# Dashboard_2_1.net
KiCad netlist of a schematic drawn in EAGLE
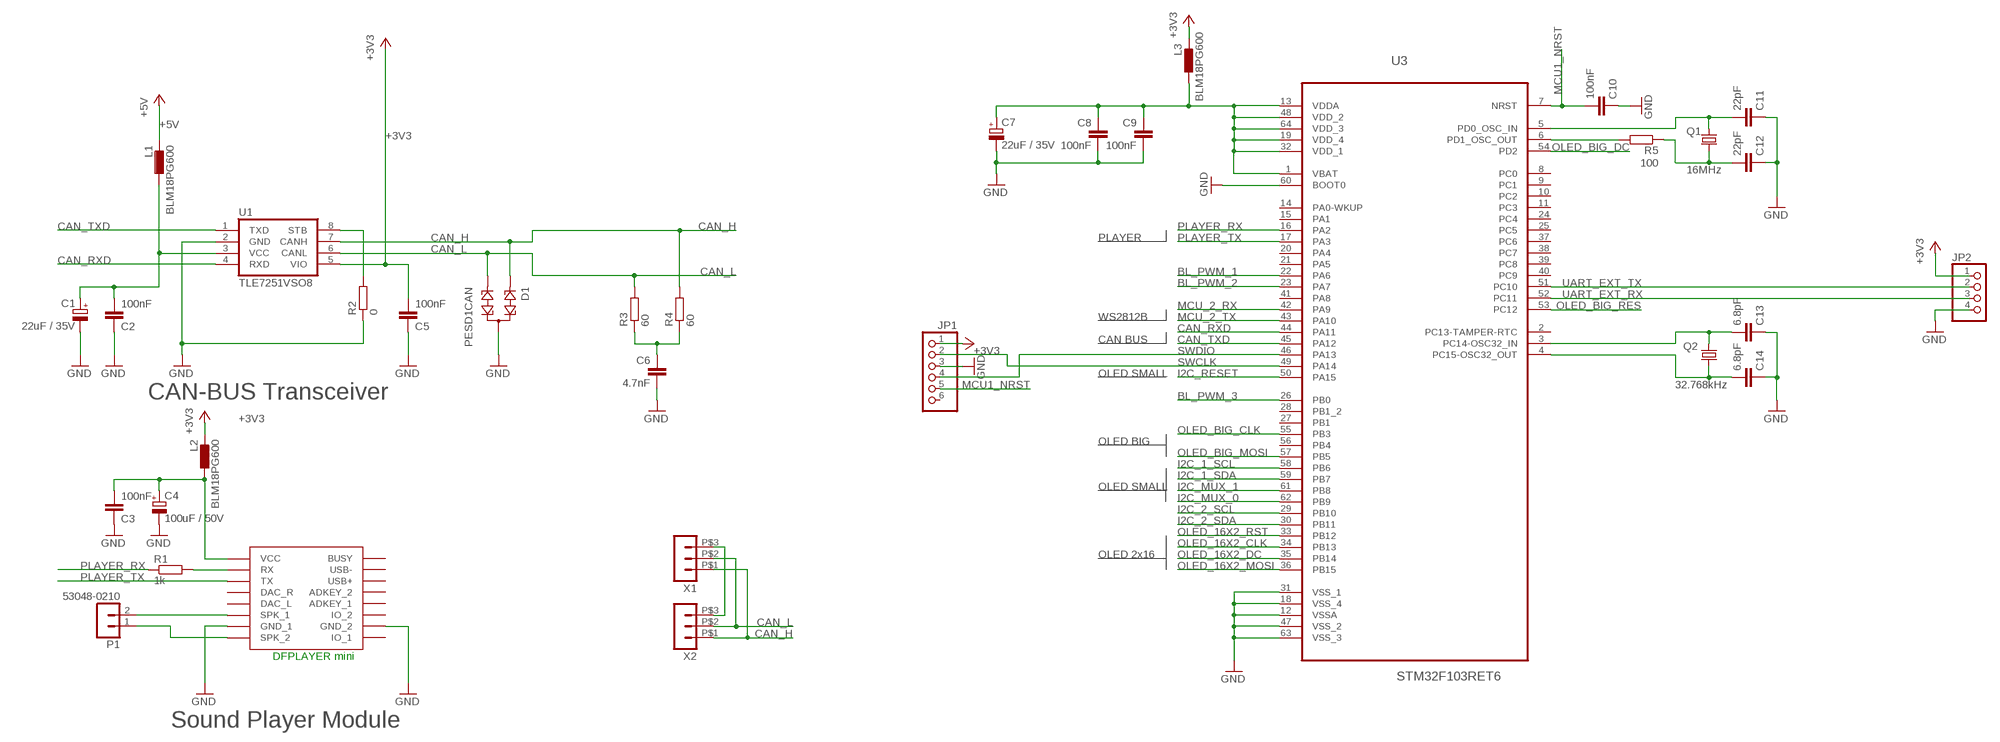
[diagram p0: schematic, sheet 1]
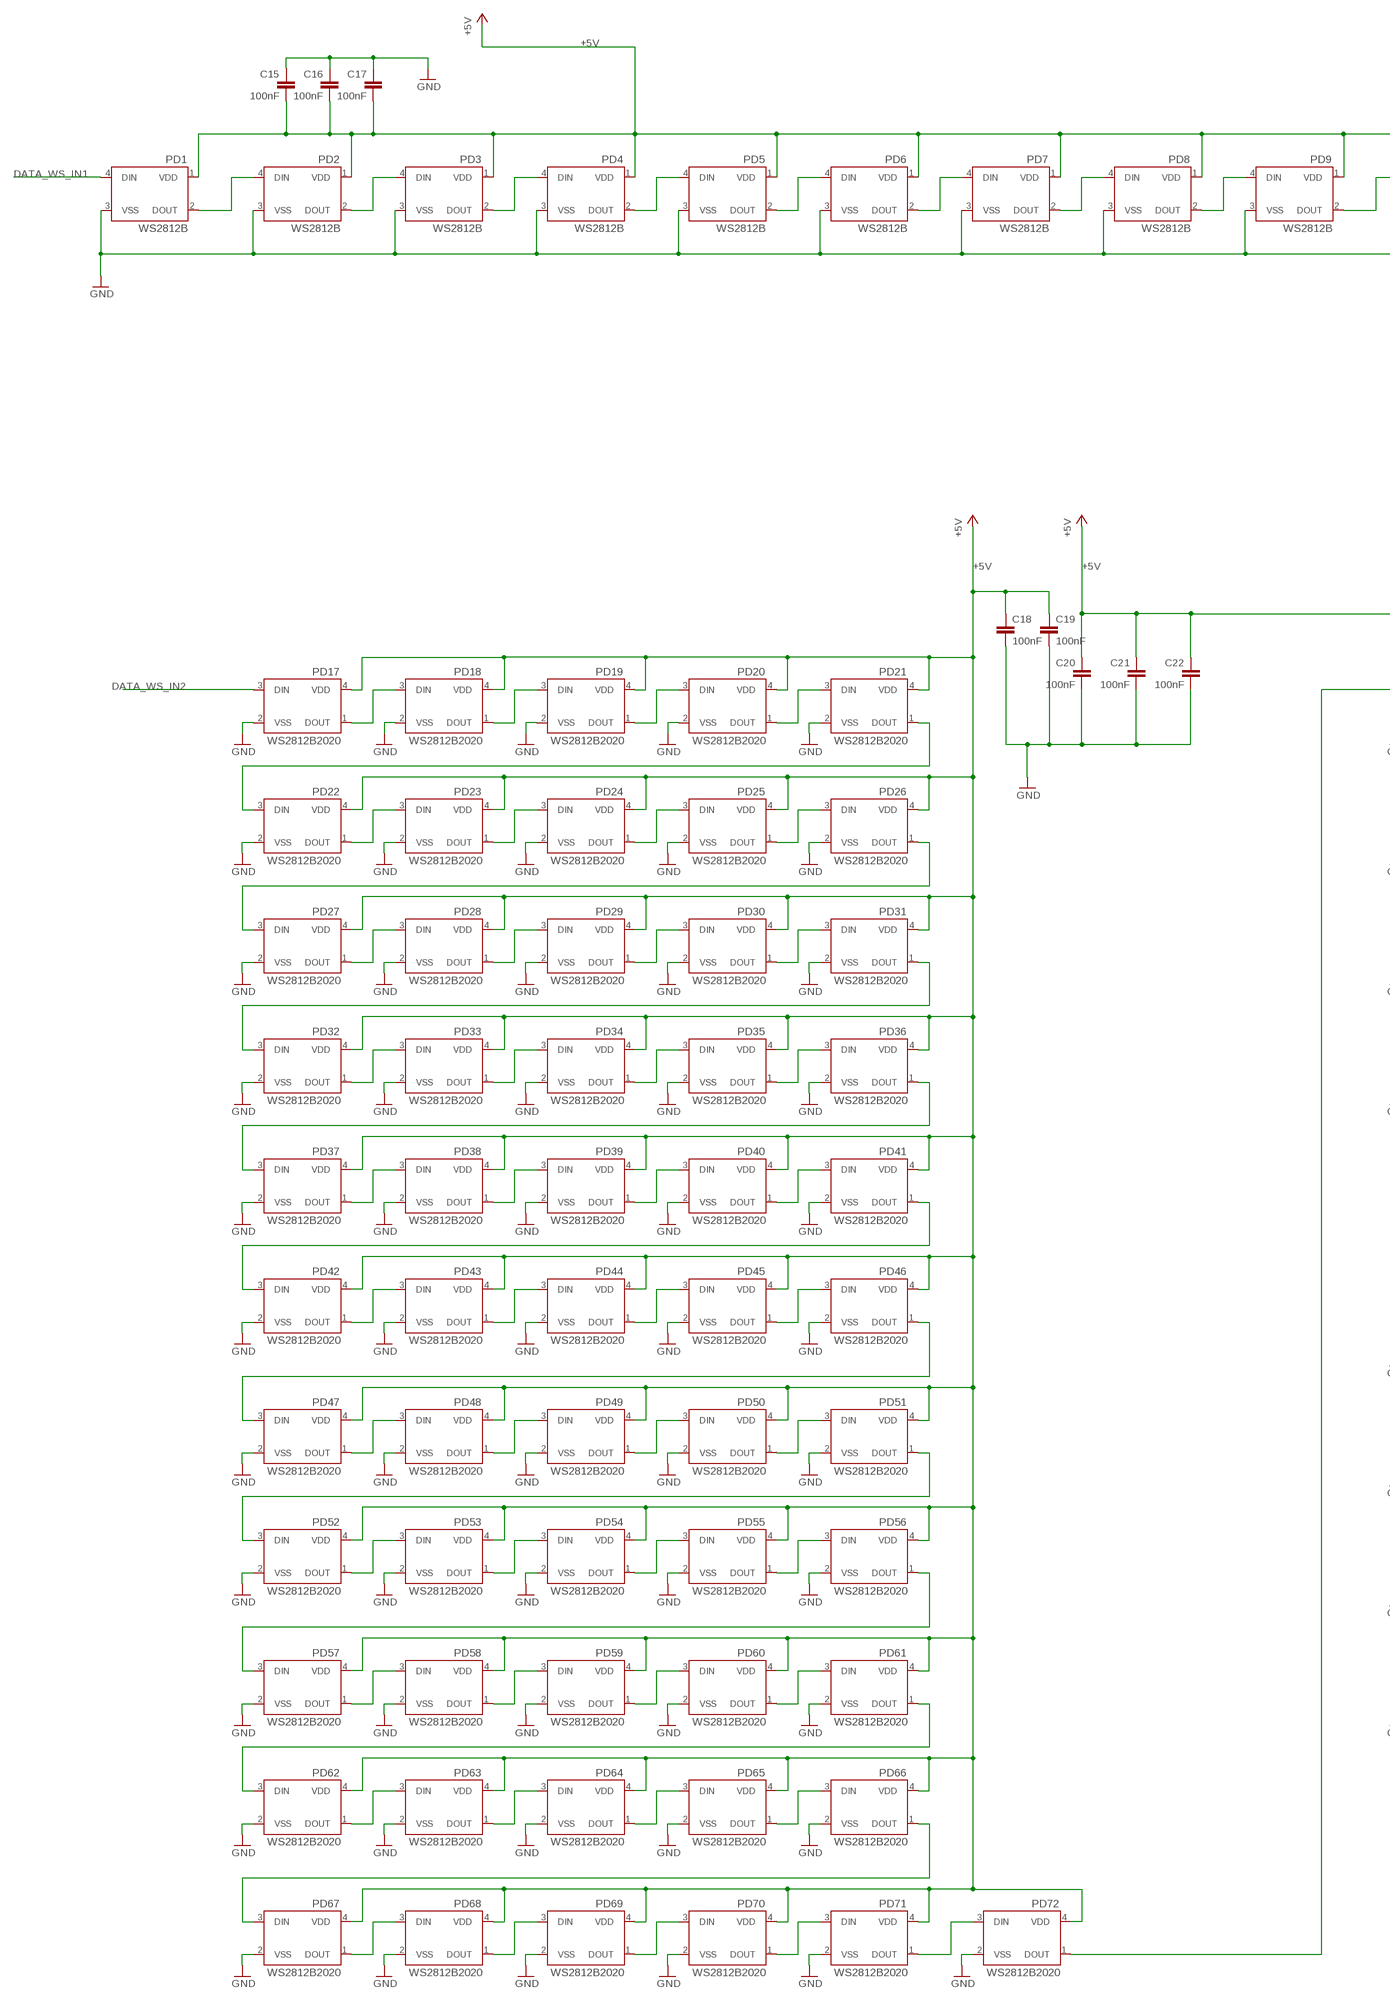
[diagram p1: schematic, sheet 2, part 1 of 2]
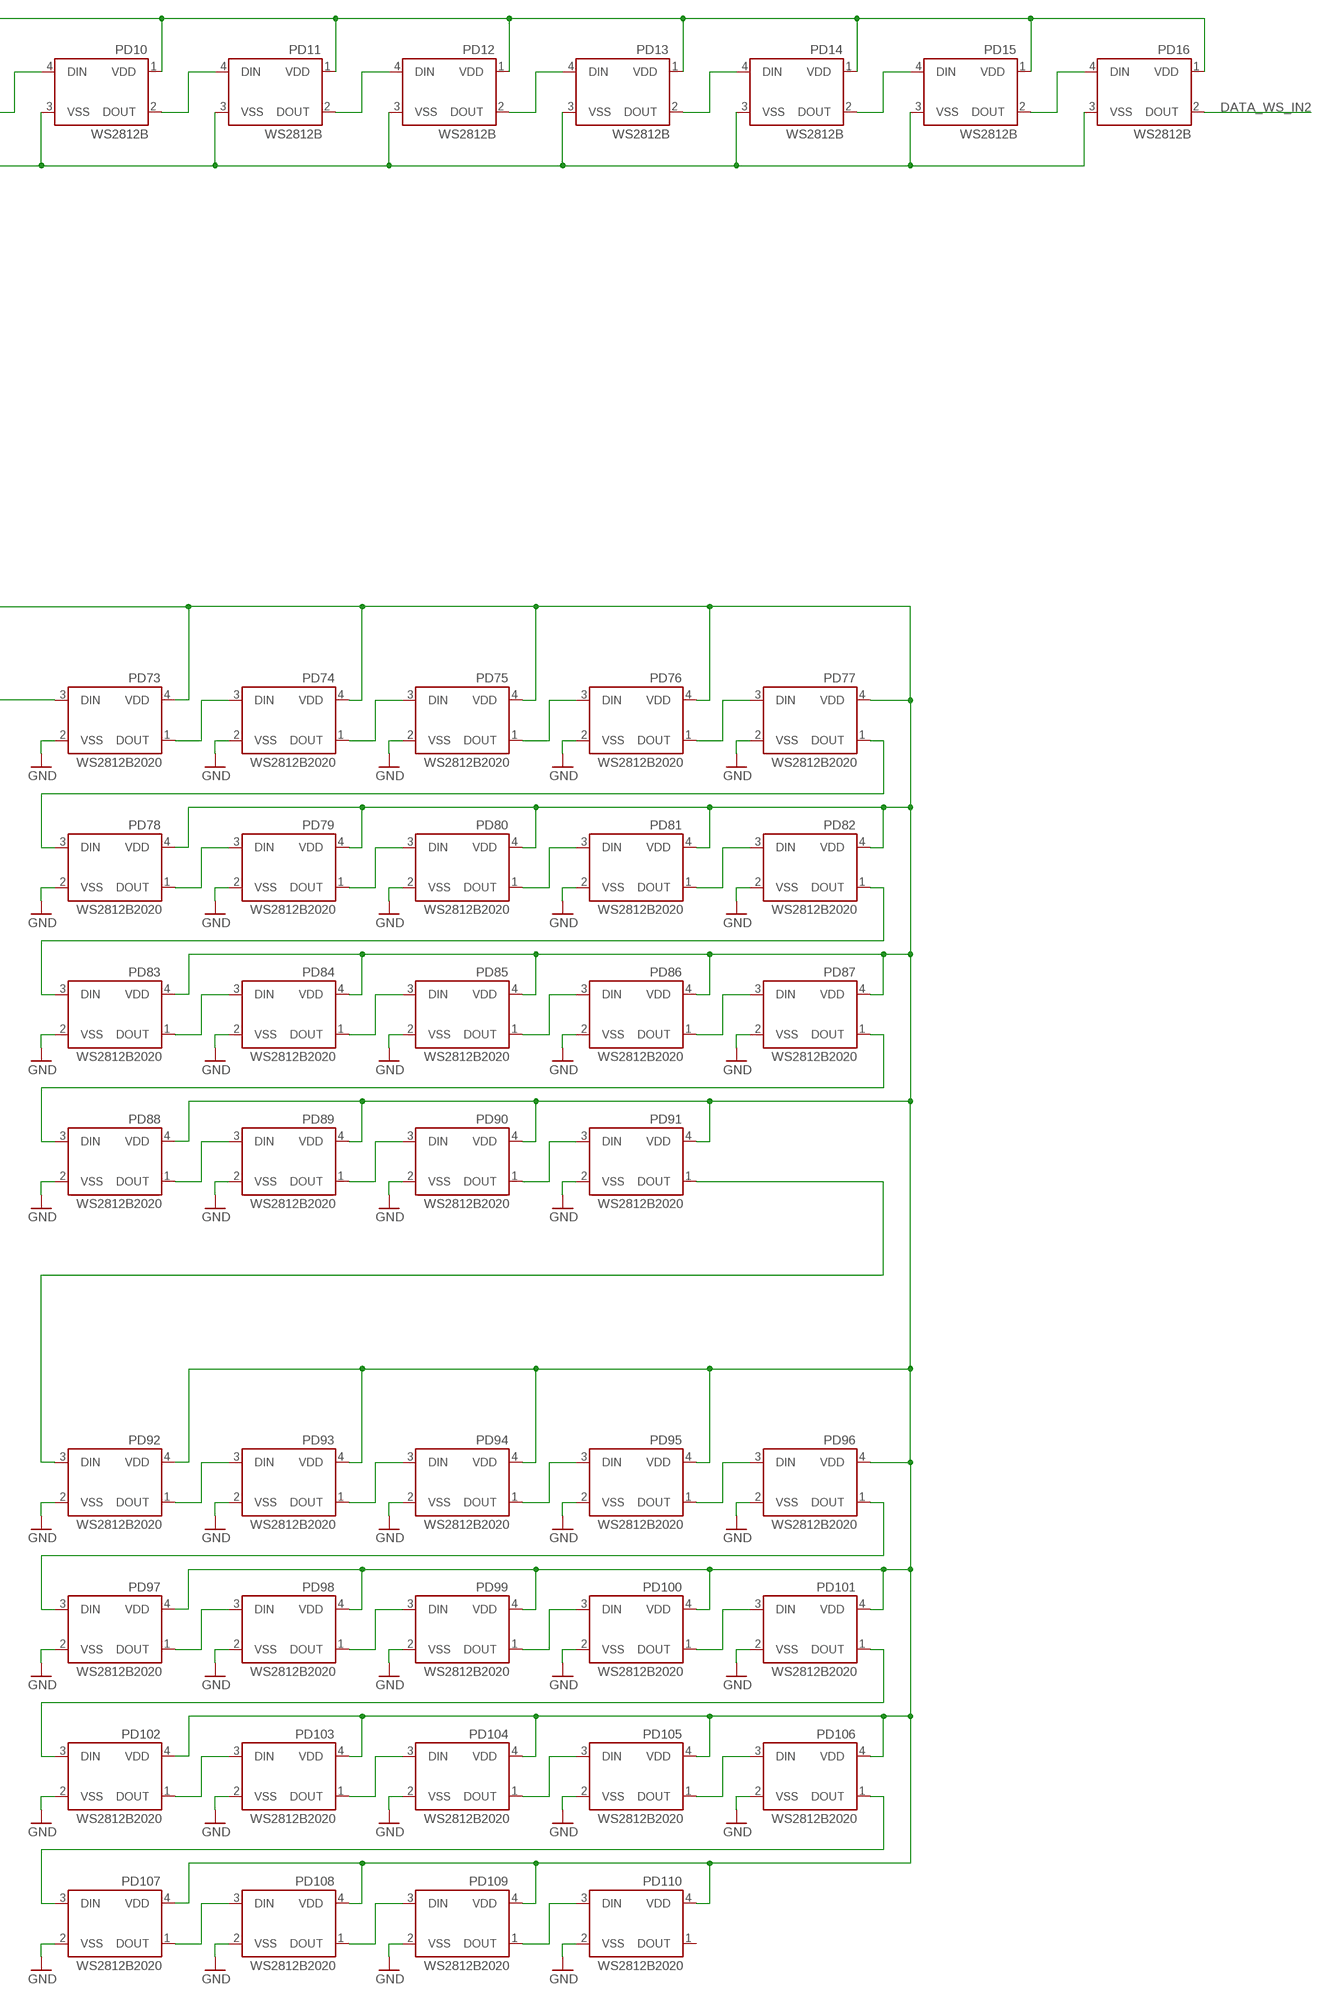
[diagram p2: schematic, sheet 2, part 2 of 2]
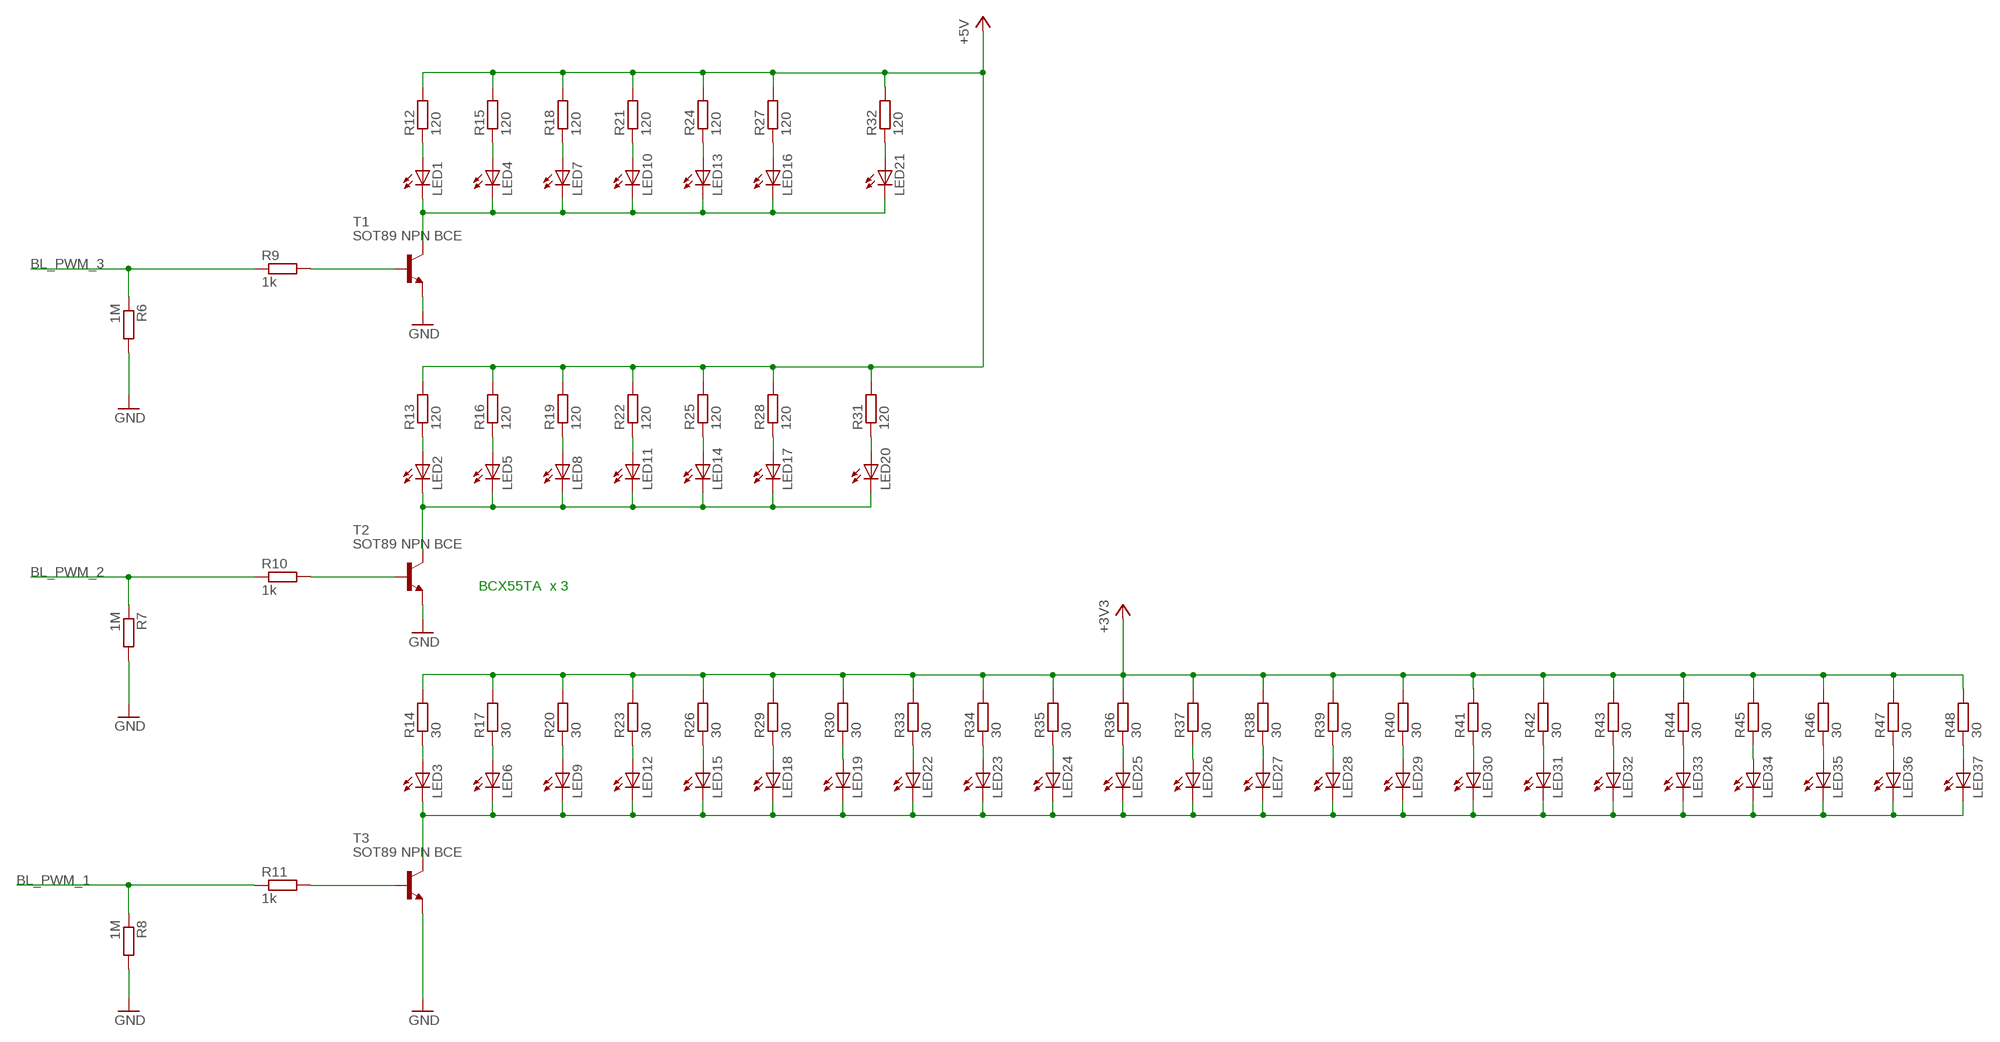
[diagram p3: schematic, sheet 3]
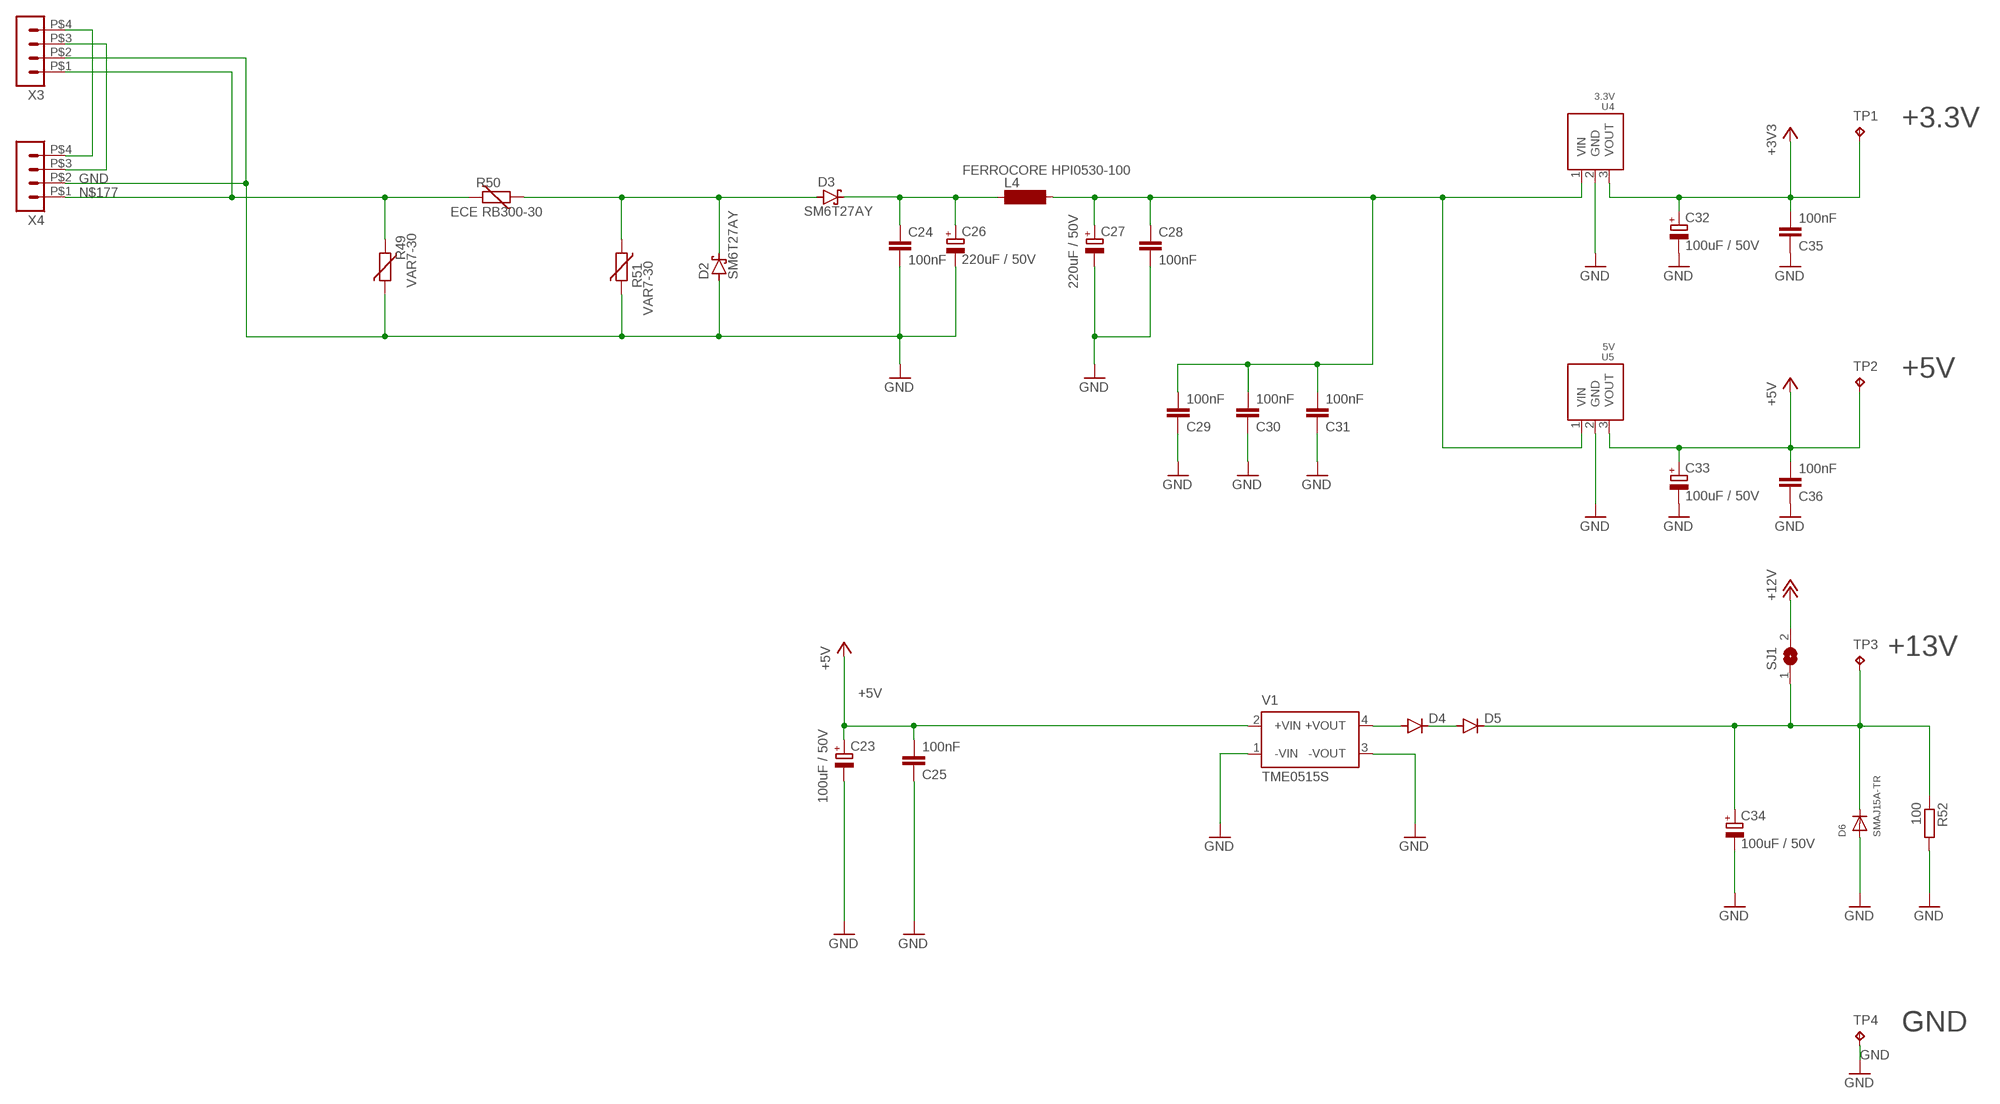
[diagram p4: schematic, sheet 4]
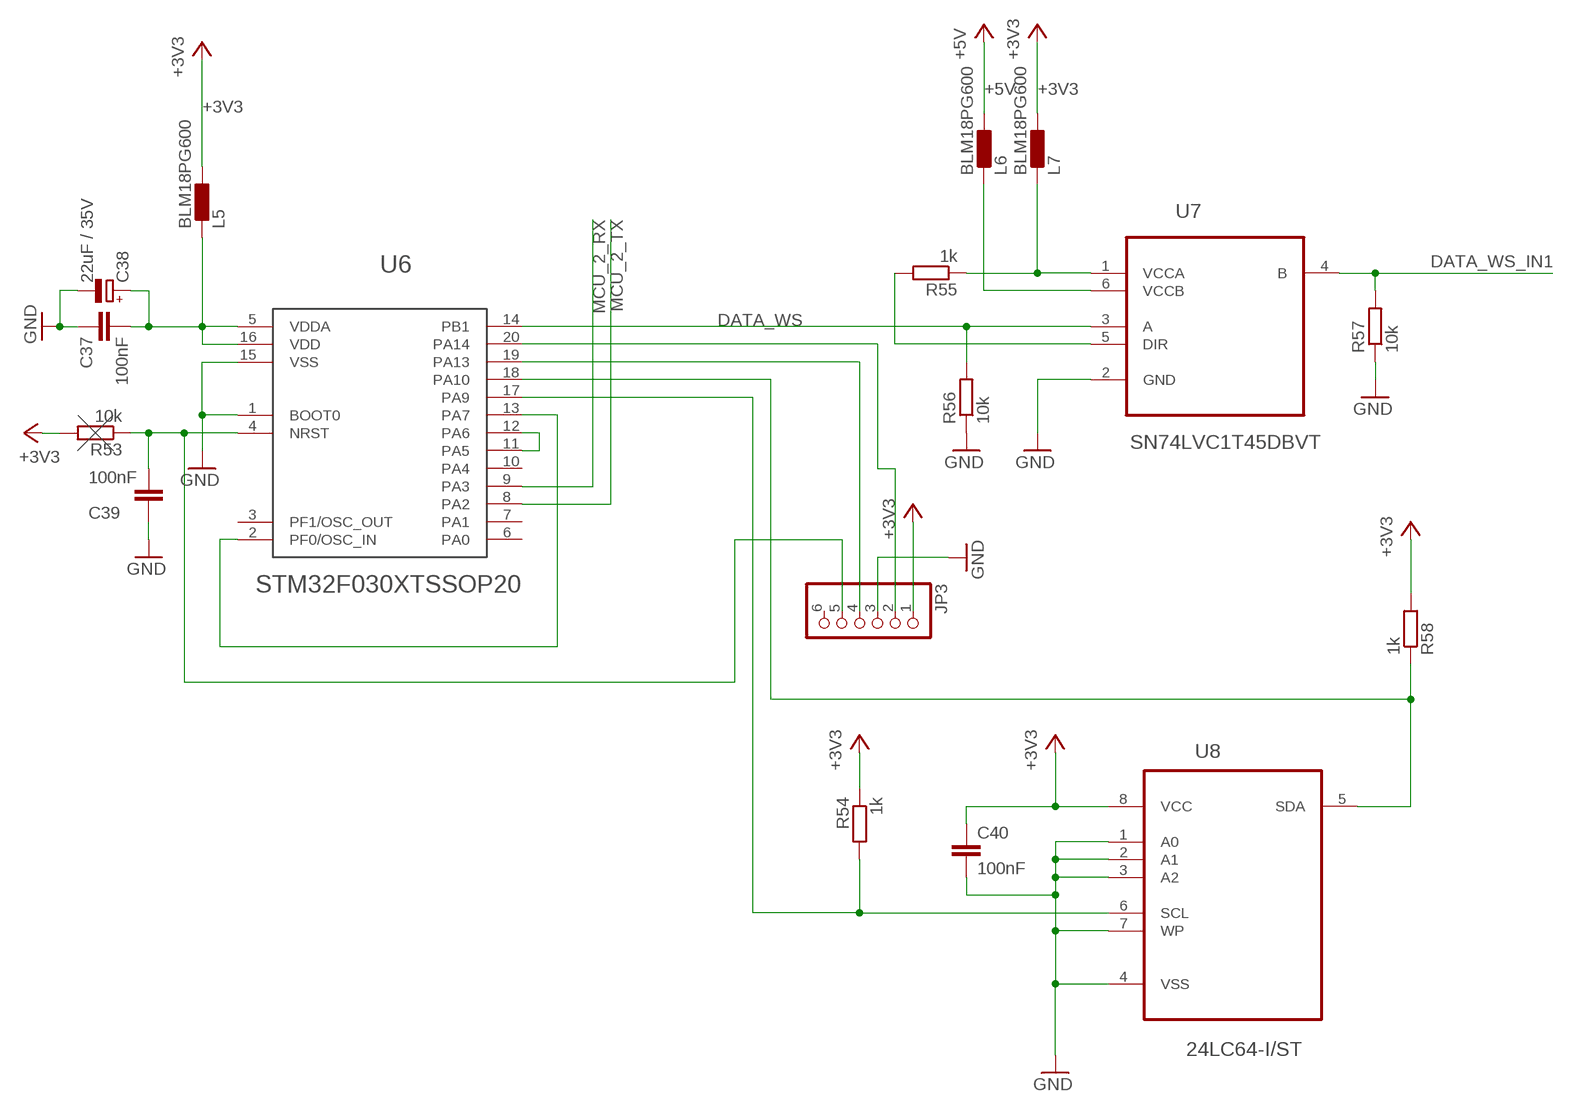
[diagram p5: schematic, sheet 5]
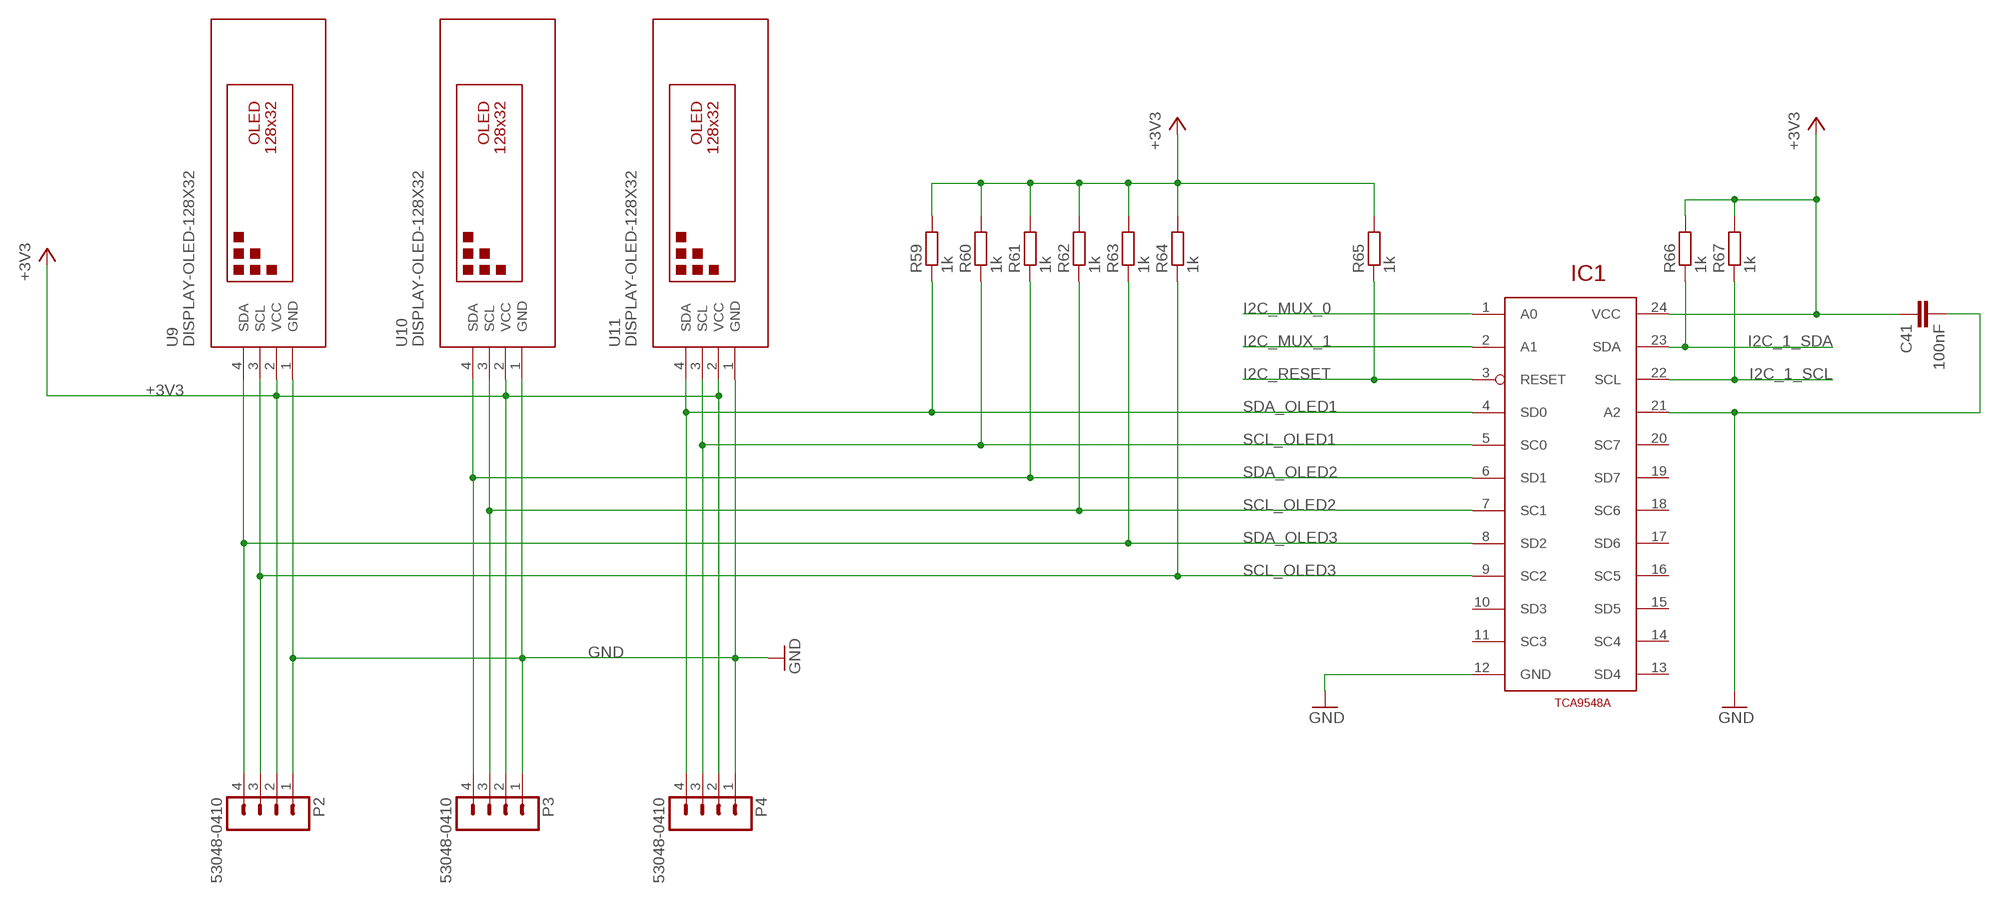
[diagram p6: schematic, sheet 6]
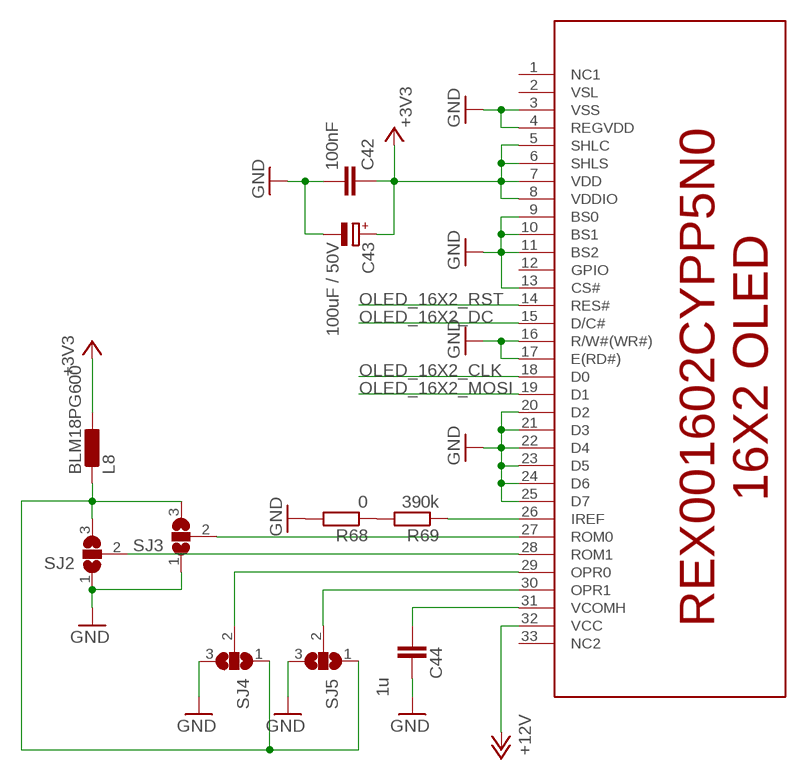
[diagram p7: schematic, sheet 7]
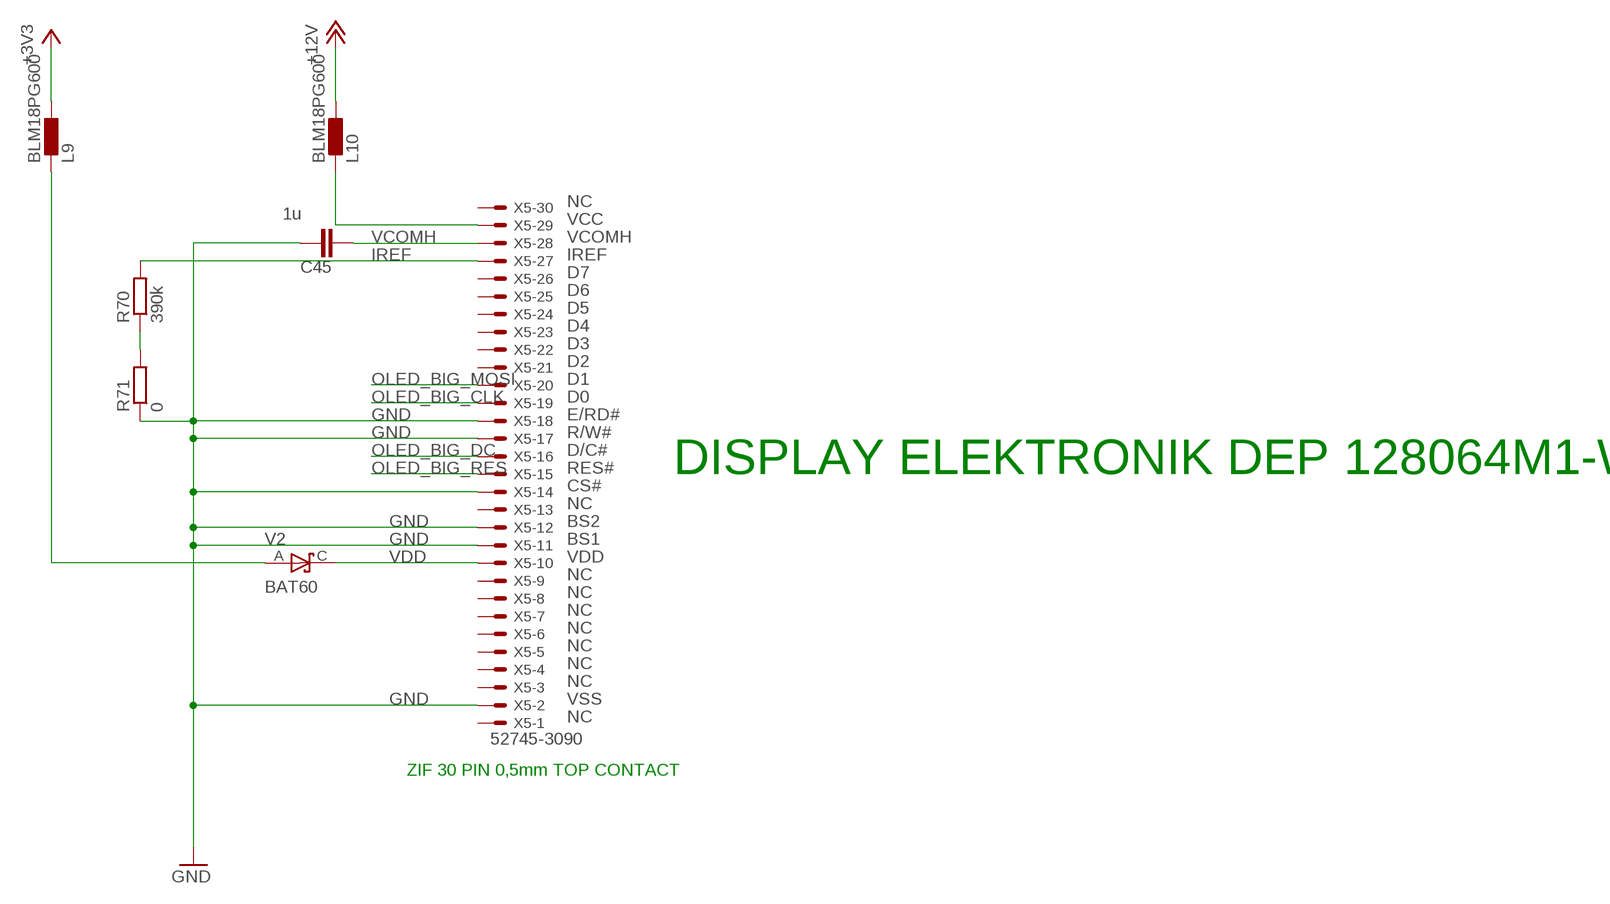
[diagram p8: schematic, sheet 8]

(export (version "E")
  (design (tool "Eeschema 10.0.6"))
  (components
    (comp (ref "C23")
      (value "100uF / 50V")
      (footprint "eagle-import:PANASONIC_F")
      (libsource (lib "eagle-import") (part "CPOL-EUF"))
    )
    (comp (ref "C24")
      (value "100nF")
      (footprint "eagle-import:C1206K")
      (libsource (lib "eagle-import") (part "rcl_334_C-EUC1206K"))
    )
    (comp (ref "C25")
      (value "100nF")
      (footprint "eagle-import:C0805K")
      (libsource (lib "eagle-import") (part "rcl_334_C-EUC0805K"))
    )
    (comp (ref "C26")
      (value "220uF / 50V")
      (footprint "eagle-import:PANASONIC_G")
      (libsource (lib "eagle-import") (part "CPOL-EUG"))
    )
    (comp (ref "C27")
      (value "220uF / 50V")
      (footprint "eagle-import:PANASONIC_G")
      (libsource (lib "eagle-import") (part "CPOL-EUG"))
    )
    (comp (ref "C28")
      (value "100nF")
      (footprint "eagle-import:C1206K")
      (libsource (lib "eagle-import") (part "rcl_334_C-EUC1206K"))
    )
    (comp (ref "C29")
      (value "100nF")
      (footprint "eagle-import:C0805K")
      (libsource (lib "eagle-import") (part "rcl_334_C-EUC0805K"))
    )
    (comp (ref "C30")
      (value "100nF")
      (footprint "eagle-import:C0805K")
      (libsource (lib "eagle-import") (part "rcl_334_C-EUC0805K"))
    )
    (comp (ref "C31")
      (value "100nF")
      (footprint "eagle-import:C0805K")
      (libsource (lib "eagle-import") (part "rcl_334_C-EUC0805K"))
    )
    (comp (ref "C32")
      (value "100uF / 50V")
      (footprint "eagle-import:PANASONIC_F")
      (libsource (lib "eagle-import") (part "CPOL-EUF"))
    )
    (comp (ref "C33")
      (value "100uF / 50V")
      (footprint "eagle-import:PANASONIC_F")
      (libsource (lib "eagle-import") (part "CPOL-EUF"))
    )
    (comp (ref "C34")
      (value "100uF / 50V")
      (footprint "eagle-import:PANASONIC_F")
      (libsource (lib "eagle-import") (part "CPOL-EUF"))
    )
    (comp (ref "C35")
      (value "100nF")
      (footprint "eagle-import:C0805K")
      (libsource (lib "eagle-import") (part "rcl_334_C-EUC0805K"))
    )
    (comp (ref "C36")
      (value "100nF")
      (footprint "eagle-import:C0805K")
      (libsource (lib "eagle-import") (part "rcl_334_C-EUC0805K"))
    )
    (comp (ref "D2")
      (value "SM6T27AY")
      (footprint "eagle-import:SMB")
      (libsource (lib "eagle-import") (part "SCHOTTKY-DIODESMD"))
    )
    (comp (ref "D3")
      (value "SM6T27AY")
      (footprint "eagle-import:SMB")
      (libsource (lib "eagle-import") (part "SCHOTTKY-DIODESMD"))
    )
    (comp (ref "D4")
      (value "DIODE-SOD123")
      (footprint "eagle-import:SOD123")
      (libsource (lib "eagle-import") (part "DIODE-SOD123"))
    )
    (comp (ref "D5")
      (value "DIODE-SOD123")
      (footprint "eagle-import:SOD123")
      (libsource (lib "eagle-import") (part "DIODE-SOD123"))
    )
    (comp (ref "D6")
      (value "SMAJ15A-TR")
      (footprint "eagle-import:SMADIODE")
      (libsource (lib "eagle-import") (part "DIODESMA"))
    )
    (comp (ref "L4")
      (value "FERROCORE HPI0530-100")
      (footprint "eagle-import:MS85")
      (libsource (lib "eagle-import") (part "MS85"))
    )
    (comp (ref "R49")
      (value "VAR7-30")
      (footprint "eagle-import:S07K11")
      (libsource (lib "eagle-import") (part "VARISTORS07K11"))
    )
    (comp (ref "R50")
      (value "ECE RB300-30")
      (footprint "eagle-import:S07K11")
      (libsource (lib "eagle-import") (part "VARISTORS07K11"))
    )
    (comp (ref "R51")
      (value "VAR7-30")
      (footprint "eagle-import:S07K11")
      (libsource (lib "eagle-import") (part "VARISTORS07K11"))
    )
    (comp (ref "R52")
      (value "100")
      (footprint "eagle-import:R0805")
      (libsource (lib "eagle-import") (part "R-EU_R0805"))
    )
    (comp (ref "SJ1") (value "SJ") (footprint "eagle-import:SJ") (libsource (lib "eagle-import") (part "SJ")))
    (comp (ref "TP1")
      (value "3V3")
      (footprint "eagle-import:TP18SQ")
      (libsource (lib "eagle-import") (part "TPTP18SQ"))
    )
    (comp (ref "TP2")
      (value "5V")
      (footprint "eagle-import:TP18SQ")
      (libsource (lib "eagle-import") (part "TPTP18SQ"))
    )
    (comp (ref "TP3")
      (value "12V")
      (footprint "eagle-import:TP18SQ")
      (libsource (lib "eagle-import") (part "TPTP18SQ"))
    )
    (comp (ref "TP4")
      (value "GND")
      (footprint "eagle-import:TP18SQ")
      (libsource (lib "eagle-import") (part "TPTP18SQ"))
    )
    (comp (ref "U4")
      (value "3.3V")
      (footprint "eagle-import:FDSM-173XXXX42")
      (libsource (lib "eagle-import") (part "FDSM_SIP-3_173010542"))
    )
    (comp (ref "U5")
      (value "5V")
      (footprint "eagle-import:FDSM-173XXXX42")
      (libsource (lib "eagle-import") (part "FDSM_SIP-3_173010542"))
    )
    (comp (ref "V1")
      (value "TME0515S")
      (footprint "eagle-import:TME")
      (fields (field (name "MPN") "TME 0515S"))
      (libsource (lib "eagle-import") (part "TME?0515S"))
    )
    (comp (ref "X3")
      (value "HEADER_POS4_43045-0412")
      (footprint "eagle-import:43045-0412")
      (libsource (lib "eagle-import") (part "HEADER_POS4_?43045-0412"))
    )
    (comp (ref "X4")
      (value "HEADER_POS4_43045-0412")
      (footprint "eagle-import:43045-0412")
      (libsource (lib "eagle-import") (part "HEADER_POS4_?43045-0412"))
    )
    (comp (ref "C37")
      (value "100nF")
      (footprint "eagle-import:C0805K")
      (libsource (lib "eagle-import") (part "rcl_334_C-EUC0805K"))
    )
    (comp (ref "C38")
      (value "22uF / 35V")
      (footprint "eagle-import:SMC_D")
      (libsource (lib "eagle-import") (part "CPOL-EUSMCD"))
    )
    (comp (ref "C39")
      (value "100nF")
      (footprint "eagle-import:C0805K")
      (libsource (lib "eagle-import") (part "rcl_334_C-EUC0805K"))
    )
    (comp (ref "C40")
      (value "100nF")
      (footprint "eagle-import:C0805K")
      (libsource (lib "eagle-import") (part "rcl_334_C-EUC0805K"))
    )
    (comp (ref "JP3")
      (value "PINHD-1X6")
      (footprint "eagle-import:1X06")
      (libsource (lib "eagle-import") (part "PINHD-1X6"))
    )
    (comp (ref "L5")
      (value "BLM18PG600")
      (footprint "eagle-import:L1608")
      (libsource (lib "eagle-import") (part "L_EU_L0603"))
    )
    (comp (ref "L6")
      (value "BLM18PG600")
      (footprint "eagle-import:L1608")
      (libsource (lib "eagle-import") (part "L_EU_L0603"))
    )
    (comp (ref "L7")
      (value "BLM18PG600")
      (footprint "eagle-import:L1608")
      (libsource (lib "eagle-import") (part "L_EU_L0603"))
    )
    (comp (ref "R53")
      (value "10k")
      (footprint "eagle-import:R0805")
      (libsource (lib "eagle-import") (part "R-EU_R0805"))
    )
    (comp (ref "R54")
      (value "1k")
      (footprint "eagle-import:R0805")
      (libsource (lib "eagle-import") (part "R-EU_R0805"))
    )
    (comp (ref "R55")
      (value "1k")
      (footprint "eagle-import:R0805")
      (libsource (lib "eagle-import") (part "R-EU_R0805"))
    )
    (comp (ref "R56")
      (value "10k")
      (footprint "eagle-import:R0805")
      (libsource (lib "eagle-import") (part "R-EU_R0805"))
    )
    (comp (ref "R57")
      (value "10k")
      (footprint "eagle-import:R0805")
      (libsource (lib "eagle-import") (part "R-EU_R0805"))
    )
    (comp (ref "R58")
      (value "1k")
      (footprint "eagle-import:R0805")
      (libsource (lib "eagle-import") (part "R-EU_R0805"))
    )
    (comp (ref "U6")
      (value "STM32F030XTSSOP20")
      (footprint "eagle-import:TSSOP-20")
      (libsource (lib "eagle-import") (part "STM32F030XTSSOP20"))
    )
    (comp (ref "U7")
      (value "SN74LVC1T45DBVT")
      (footprint "eagle-import:SOT95P280X145-6N")
      (fields (field (name "MF") "Texas Instruments"))
      (libsource (lib "eagle-import") (part "SN74LVC1T45DBVT"))
    )
    (comp (ref "U8")
      (value "24LC64-I/ST")
      (footprint "eagle-import:SOP65P638X110-8N")
      (fields (field (name "MF") "Microchip"))
      (libsource (lib "eagle-import") (part "24LC64-I/ST"))
    )
    (comp (ref "C1")
      (value "22uF / 35V")
      (footprint "eagle-import:SMC_D")
      (libsource (lib "eagle-import") (part "CPOL-EUSMCD"))
    )
    (comp (ref "C2")
      (value "100nF")
      (footprint "eagle-import:C0805K")
      (libsource (lib "eagle-import") (part "rcl_334_C-EUC0805K"))
    )
    (comp (ref "C3")
      (value "100nF")
      (footprint "eagle-import:C0805K")
      (libsource (lib "eagle-import") (part "rcl_334_C-EUC0805K"))
    )
    (comp (ref "C4")
      (value "100uF / 50V")
      (footprint "eagle-import:PANASONIC_F")
      (libsource (lib "eagle-import") (part "CPOL-EUF"))
    )
    (comp (ref "C5")
      (value "100nF")
      (footprint "eagle-import:C0805K")
      (libsource (lib "eagle-import") (part "rcl_334_C-EUC0805K"))
    )
    (comp (ref "C6")
      (value "4.7nF")
      (footprint "eagle-import:C0805K")
      (libsource (lib "eagle-import") (part "rcl_334_C-EUC0805K"))
    )
    (comp (ref "C7")
      (value "22uF / 35V")
      (footprint "eagle-import:SMC_D")
      (libsource (lib "eagle-import") (part "CPOL-EUSMCD"))
    )
    (comp (ref "C8")
      (value "100nF")
      (footprint "eagle-import:C0805K")
      (libsource (lib "eagle-import") (part "rcl_334_C-EUC0805K"))
    )
    (comp (ref "C9")
      (value "100nF")
      (footprint "eagle-import:C0805K")
      (libsource (lib "eagle-import") (part "rcl_334_C-EUC0805K"))
    )
    (comp (ref "C10")
      (value "100nF")
      (footprint "eagle-import:C0805K")
      (libsource (lib "eagle-import") (part "rcl_334_C-EUC0805K"))
    )
    (comp (ref "C11")
      (value "22pF")
      (footprint "eagle-import:C0805K")
      (libsource (lib "eagle-import") (part "rcl_334_C-EUC0805K"))
    )
    (comp (ref "C12")
      (value "22pF")
      (footprint "eagle-import:C0805K")
      (libsource (lib "eagle-import") (part "rcl_334_C-EUC0805K"))
    )
    (comp (ref "C13")
      (value "6.8pF")
      (footprint "eagle-import:C0805K")
      (libsource (lib "eagle-import") (part "rcl_334_C-EUC0805K"))
    )
    (comp (ref "C14")
      (value "6.8pF")
      (footprint "eagle-import:C0805K")
      (libsource (lib "eagle-import") (part "rcl_334_C-EUC0805K"))
    )
    (comp (ref "D1")
      (value "PESD1CAN")
      (footprint "eagle-import:SOT23")
      (libsource (lib "eagle-import") (part "PESD1CAN"))
    )
    (comp (ref "JP1")
      (value "PINHD-1X6")
      (footprint "eagle-import:1X06")
      (libsource (lib "eagle-import") (part "PINHD-1X6"))
    )
    (comp (ref "JP2")
      (value "PINHD-1X4")
      (footprint "eagle-import:1X04")
      (libsource (lib "eagle-import") (part "PINHD-1X4"))
    )
    (comp (ref "L1")
      (value "BLM18PG600")
      (footprint "eagle-import:L1608")
      (libsource (lib "eagle-import") (part "L_EU_L0603"))
    )
    (comp (ref "L2")
      (value "BLM18PG600")
      (footprint "eagle-import:L1608")
      (libsource (lib "eagle-import") (part "L_EU_L0603"))
    )
    (comp (ref "L3")
      (value "BLM18PG600")
      (footprint "eagle-import:L1608")
      (libsource (lib "eagle-import") (part "L_EU_L0603"))
    )
    (comp (ref "P1")
      (value "53048-0210")
      (footprint "eagle-import:53048-0210")
      (libsource (lib "eagle-import") (part "53048-0210"))
    )
    (comp (ref "Q1")
      (value "16MHz")
      (footprint "eagle-import:SM49")
      (libsource (lib "eagle-import") (part "CRYSTALSM49"))
    )
    (comp (ref "Q2")
      (value "32.768kHz")
      (footprint "eagle-import:SMD4_270")
      (libsource (lib "eagle-import") (part "MC-306"))
    )
    (comp (ref "R1")
      (value "1k")
      (footprint "eagle-import:R0805")
      (libsource (lib "eagle-import") (part "R-EU_R0805"))
    )
    (comp (ref "R2")
      (value "0")
      (footprint "eagle-import:R0805")
      (libsource (lib "eagle-import") (part "R-EU_R0805"))
    )
    (comp (ref "R3")
      (value "60")
      (footprint "eagle-import:R0805")
      (libsource (lib "eagle-import") (part "R-EU_R0805"))
    )
    (comp (ref "R4")
      (value "60")
      (footprint "eagle-import:R0805")
      (libsource (lib "eagle-import") (part "R-EU_R0805"))
    )
    (comp (ref "R5")
      (value "100")
      (footprint "eagle-import:R0805")
      (libsource (lib "eagle-import") (part "R-EU_R0805"))
    )
    (comp (ref "U1")
      (value "TLE7251VSO8")
      (footprint "eagle-import:SO8")
      (libsource (lib "eagle-import") (part "TLE7251VSO8"))
    )
    (comp (ref "U2")
      (value "DFPLAYER")
      (footprint "eagle-import:DFPLAYER")
      (libsource (lib "eagle-import") (part "DFPLAYER"))
    )
    (comp (ref "U3")
      (value "STM32F103RET6")
      (footprint "eagle-import:QFP50P1200X1200X160-64N")
      (libsource (lib "eagle-import") (part "STM32F103RET6"))
    )
    (comp (ref "X1")
      (value "HEADER_POS3_43650-0315")
      (footprint "eagle-import:43650-0315")
      (libsource (lib "eagle-import") (part "HEADER_POS3_?43650-0315"))
    )
    (comp (ref "X2")
      (value "HEADER_POS3_43650-0315")
      (footprint "eagle-import:43650-0315")
      (libsource (lib "eagle-import") (part "HEADER_POS3_?43650-0315"))
    )
    (comp (ref "C41")
      (value "100nF")
      (footprint "eagle-import:C0805K")
      (libsource (lib "eagle-import") (part "rcl_334_C-EUC0805K"))
    )
    (comp (ref "IC1")
      (value "TCA9548A")
      (footprint "eagle-import:TSSOP24")
      (libsource (lib "eagle-import") (part "TCA9548A"))
    )
    (comp (ref "P2")
      (value "53048-0410")
      (footprint "eagle-import:53048-0410")
      (libsource (lib "eagle-import") (part "53048-0410"))
    )
    (comp (ref "P3")
      (value "53048-0410")
      (footprint "eagle-import:53048-0410")
      (libsource (lib "eagle-import") (part "53048-0410"))
    )
    (comp (ref "P4")
      (value "53048-0410")
      (footprint "eagle-import:53048-0410")
      (libsource (lib "eagle-import") (part "53048-0410"))
    )
    (comp (ref "R59")
      (value "1k")
      (footprint "eagle-import:R0805")
      (libsource (lib "eagle-import") (part "R-EU_R0805"))
    )
    (comp (ref "R60")
      (value "1k")
      (footprint "eagle-import:R0805")
      (libsource (lib "eagle-import") (part "R-EU_R0805"))
    )
    (comp (ref "R61")
      (value "1k")
      (footprint "eagle-import:R0805")
      (libsource (lib "eagle-import") (part "R-EU_R0805"))
    )
    (comp (ref "R62")
      (value "1k")
      (footprint "eagle-import:R0805")
      (libsource (lib "eagle-import") (part "R-EU_R0805"))
    )
    (comp (ref "R63")
      (value "1k")
      (footprint "eagle-import:R0805")
      (libsource (lib "eagle-import") (part "R-EU_R0805"))
    )
    (comp (ref "R64")
      (value "1k")
      (footprint "eagle-import:R0805")
      (libsource (lib "eagle-import") (part "R-EU_R0805"))
    )
    (comp (ref "R65")
      (value "1k")
      (footprint "eagle-import:R0805")
      (libsource (lib "eagle-import") (part "R-EU_R0805"))
    )
    (comp (ref "R66")
      (value "1k")
      (footprint "eagle-import:R0805")
      (libsource (lib "eagle-import") (part "R-EU_R0805"))
    )
    (comp (ref "R67")
      (value "1k")
      (footprint "eagle-import:R0805")
      (libsource (lib "eagle-import") (part "R-EU_R0805"))
    )
    (comp (ref "U9")
      (value "DISPLAY-OLED-128X32")
      (footprint "eagle-import:DISPLAY-OLED-128X32")
      (libsource (lib "eagle-import") (part "DISPLAY-OLED-128X32"))
    )
    (comp (ref "U10")
      (value "DISPLAY-OLED-128X32")
      (footprint "eagle-import:DISPLAY-OLED-128X32")
      (libsource (lib "eagle-import") (part "DISPLAY-OLED-128X32"))
    )
    (comp (ref "U11")
      (value "DISPLAY-OLED-128X32")
      (footprint "eagle-import:DISPLAY-OLED-128X32")
      (libsource (lib "eagle-import") (part "DISPLAY-OLED-128X32"))
    )
    (comp (ref "C15")
      (value "100nF")
      (footprint "eagle-import:C0805K")
      (libsource (lib "eagle-import") (part "rcl_334_C-EUC0805K"))
    )
    (comp (ref "C16")
      (value "100nF")
      (footprint "eagle-import:C0805K")
      (libsource (lib "eagle-import") (part "rcl_334_C-EUC0805K"))
    )
    (comp (ref "C17")
      (value "100nF")
      (footprint "eagle-import:C0805K")
      (libsource (lib "eagle-import") (part "rcl_334_C-EUC0805K"))
    )
    (comp (ref "C18")
      (value "100nF")
      (footprint "eagle-import:C0805K")
      (libsource (lib "eagle-import") (part "rcl_334_C-EUC0805K"))
    )
    (comp (ref "C19")
      (value "100nF")
      (footprint "eagle-import:C0805K")
      (libsource (lib "eagle-import") (part "rcl_334_C-EUC0805K"))
    )
    (comp (ref "C20")
      (value "100nF")
      (footprint "eagle-import:C0805K")
      (libsource (lib "eagle-import") (part "rcl_334_C-EUC0805K"))
    )
    (comp (ref "C21")
      (value "100nF")
      (footprint "eagle-import:C0805K")
      (libsource (lib "eagle-import") (part "rcl_334_C-EUC0805K"))
    )
    (comp (ref "C22")
      (value "100nF")
      (footprint "eagle-import:C0805K")
      (libsource (lib "eagle-import") (part "rcl_334_C-EUC0805K"))
    )
    (comp (ref "PD1")
      (value "WS2812B")
      (footprint "eagle-import:5050")
      (fields (field (name "MF") "Adafruit Industries"))
      (libsource (lib "eagle-import") (part "WS2812B"))
    )
    (comp (ref "PD2")
      (value "WS2812B")
      (footprint "eagle-import:5050")
      (fields (field (name "MF") "Adafruit Industries"))
      (libsource (lib "eagle-import") (part "WS2812B"))
    )
    (comp (ref "PD3")
      (value "WS2812B")
      (footprint "eagle-import:5050")
      (fields (field (name "MF") "Adafruit Industries"))
      (libsource (lib "eagle-import") (part "WS2812B"))
    )
    (comp (ref "PD4")
      (value "WS2812B")
      (footprint "eagle-import:5050")
      (fields (field (name "MF") "Adafruit Industries"))
      (libsource (lib "eagle-import") (part "WS2812B"))
    )
    (comp (ref "PD5")
      (value "WS2812B")
      (footprint "eagle-import:5050")
      (fields (field (name "MF") "Adafruit Industries"))
      (libsource (lib "eagle-import") (part "WS2812B"))
    )
    (comp (ref "PD6")
      (value "WS2812B")
      (footprint "eagle-import:5050")
      (fields (field (name "MF") "Adafruit Industries"))
      (libsource (lib "eagle-import") (part "WS2812B"))
    )
    (comp (ref "PD7")
      (value "WS2812B")
      (footprint "eagle-import:5050")
      (fields (field (name "MF") "Adafruit Industries"))
      (libsource (lib "eagle-import") (part "WS2812B"))
    )
    (comp (ref "PD8")
      (value "WS2812B")
      (footprint "eagle-import:5050")
      (fields (field (name "MF") "Adafruit Industries"))
      (libsource (lib "eagle-import") (part "WS2812B"))
    )
    (comp (ref "PD9")
      (value "WS2812B")
      (footprint "eagle-import:5050")
      (fields (field (name "MF") "Adafruit Industries"))
      (libsource (lib "eagle-import") (part "WS2812B"))
    )
    (comp (ref "PD10")
      (value "WS2812B")
      (footprint "eagle-import:5050")
      (fields (field (name "MF") "Adafruit Industries"))
      (libsource (lib "eagle-import") (part "WS2812B"))
    )
    (comp (ref "PD11")
      (value "WS2812B")
      (footprint "eagle-import:5050")
      (fields (field (name "MF") "Adafruit Industries"))
      (libsource (lib "eagle-import") (part "WS2812B"))
    )
    (comp (ref "PD12")
      (value "WS2812B")
      (footprint "eagle-import:5050")
      (fields (field (name "MF") "Adafruit Industries"))
      (libsource (lib "eagle-import") (part "WS2812B"))
    )
    (comp (ref "PD13")
      (value "WS2812B")
      (footprint "eagle-import:5050")
      (fields (field (name "MF") "Adafruit Industries"))
      (libsource (lib "eagle-import") (part "WS2812B"))
    )
    (comp (ref "PD14")
      (value "WS2812B")
      (footprint "eagle-import:5050")
      (fields (field (name "MF") "Adafruit Industries"))
      (libsource (lib "eagle-import") (part "WS2812B"))
    )
    (comp (ref "PD15")
      (value "WS2812B")
      (footprint "eagle-import:5050")
      (fields (field (name "MF") "Adafruit Industries"))
      (libsource (lib "eagle-import") (part "WS2812B"))
    )
    (comp (ref "PD16")
      (value "WS2812B")
      (footprint "eagle-import:5050")
      (fields (field (name "MF") "Adafruit Industries"))
      (libsource (lib "eagle-import") (part "WS2812B"))
    )
    (comp (ref "PD17")
      (value "WS2812B2020")
      (footprint "eagle-import:LED_WS2812-2020")
      (libsource (lib "eagle-import") (part "WS2812B2020"))
    )
    (comp (ref "PD18")
      (value "WS2812B2020")
      (footprint "eagle-import:LED_WS2812-2020")
      (libsource (lib "eagle-import") (part "WS2812B2020"))
    )
    (comp (ref "PD19")
      (value "WS2812B2020")
      (footprint "eagle-import:LED_WS2812-2020")
      (libsource (lib "eagle-import") (part "WS2812B2020"))
    )
    (comp (ref "PD20")
      (value "WS2812B2020")
      (footprint "eagle-import:LED_WS2812-2020")
      (libsource (lib "eagle-import") (part "WS2812B2020"))
    )
    (comp (ref "PD21")
      (value "WS2812B2020")
      (footprint "eagle-import:LED_WS2812-2020")
      (libsource (lib "eagle-import") (part "WS2812B2020"))
    )
    (comp (ref "PD22")
      (value "WS2812B2020")
      (footprint "eagle-import:LED_WS2812-2020")
      (libsource (lib "eagle-import") (part "WS2812B2020"))
    )
    (comp (ref "PD23")
      (value "WS2812B2020")
      (footprint "eagle-import:LED_WS2812-2020")
      (libsource (lib "eagle-import") (part "WS2812B2020"))
    )
    (comp (ref "PD24")
      (value "WS2812B2020")
      (footprint "eagle-import:LED_WS2812-2020")
      (libsource (lib "eagle-import") (part "WS2812B2020"))
    )
    (comp (ref "PD25")
      (value "WS2812B2020")
      (footprint "eagle-import:LED_WS2812-2020")
      (libsource (lib "eagle-import") (part "WS2812B2020"))
    )
    (comp (ref "PD26")
      (value "WS2812B2020")
      (footprint "eagle-import:LED_WS2812-2020")
      (libsource (lib "eagle-import") (part "WS2812B2020"))
    )
    (comp (ref "PD27")
      (value "WS2812B2020")
      (footprint "eagle-import:LED_WS2812-2020")
      (libsource (lib "eagle-import") (part "WS2812B2020"))
    )
    (comp (ref "PD28")
      (value "WS2812B2020")
      (footprint "eagle-import:LED_WS2812-2020")
      (libsource (lib "eagle-import") (part "WS2812B2020"))
    )
    (comp (ref "PD29")
      (value "WS2812B2020")
      (footprint "eagle-import:LED_WS2812-2020")
      (libsource (lib "eagle-import") (part "WS2812B2020"))
    )
    (comp (ref "PD30")
      (value "WS2812B2020")
      (footprint "eagle-import:LED_WS2812-2020")
      (libsource (lib "eagle-import") (part "WS2812B2020"))
    )
    (comp (ref "PD31")
      (value "WS2812B2020")
      (footprint "eagle-import:LED_WS2812-2020")
      (libsource (lib "eagle-import") (part "WS2812B2020"))
    )
    (comp (ref "PD32")
      (value "WS2812B2020")
      (footprint "eagle-import:LED_WS2812-2020")
      (libsource (lib "eagle-import") (part "WS2812B2020"))
    )
    (comp (ref "PD33")
      (value "WS2812B2020")
      (footprint "eagle-import:LED_WS2812-2020")
      (libsource (lib "eagle-import") (part "WS2812B2020"))
    )
    (comp (ref "PD34")
      (value "WS2812B2020")
      (footprint "eagle-import:LED_WS2812-2020")
      (libsource (lib "eagle-import") (part "WS2812B2020"))
    )
    (comp (ref "PD35")
      (value "WS2812B2020")
      (footprint "eagle-import:LED_WS2812-2020")
      (libsource (lib "eagle-import") (part "WS2812B2020"))
    )
    (comp (ref "PD36")
      (value "WS2812B2020")
      (footprint "eagle-import:LED_WS2812-2020")
      (libsource (lib "eagle-import") (part "WS2812B2020"))
    )
    (comp (ref "PD37")
      (value "WS2812B2020")
      (footprint "eagle-import:LED_WS2812-2020")
      (libsource (lib "eagle-import") (part "WS2812B2020"))
    )
    (comp (ref "PD38")
      (value "WS2812B2020")
      (footprint "eagle-import:LED_WS2812-2020")
      (libsource (lib "eagle-import") (part "WS2812B2020"))
    )
    (comp (ref "PD39")
      (value "WS2812B2020")
      (footprint "eagle-import:LED_WS2812-2020")
      (libsource (lib "eagle-import") (part "WS2812B2020"))
    )
    (comp (ref "PD40")
      (value "WS2812B2020")
      (footprint "eagle-import:LED_WS2812-2020")
      (libsource (lib "eagle-import") (part "WS2812B2020"))
    )
    (comp (ref "PD41")
      (value "WS2812B2020")
      (footprint "eagle-import:LED_WS2812-2020")
      (libsource (lib "eagle-import") (part "WS2812B2020"))
    )
    (comp (ref "PD42")
      (value "WS2812B2020")
      (footprint "eagle-import:LED_WS2812-2020")
      (libsource (lib "eagle-import") (part "WS2812B2020"))
    )
    (comp (ref "PD43")
      (value "WS2812B2020")
      (footprint "eagle-import:LED_WS2812-2020")
      (libsource (lib "eagle-import") (part "WS2812B2020"))
    )
    (comp (ref "PD44")
      (value "WS2812B2020")
      (footprint "eagle-import:LED_WS2812-2020")
      (libsource (lib "eagle-import") (part "WS2812B2020"))
    )
    (comp (ref "PD45")
      (value "WS2812B2020")
      (footprint "eagle-import:LED_WS2812-2020")
      (libsource (lib "eagle-import") (part "WS2812B2020"))
    )
    (comp (ref "PD46")
      (value "WS2812B2020")
      (footprint "eagle-import:LED_WS2812-2020")
      (libsource (lib "eagle-import") (part "WS2812B2020"))
    )
    (comp (ref "PD47")
      (value "WS2812B2020")
      (footprint "eagle-import:LED_WS2812-2020")
      (libsource (lib "eagle-import") (part "WS2812B2020"))
    )
    (comp (ref "PD48")
      (value "WS2812B2020")
      (footprint "eagle-import:LED_WS2812-2020")
      (libsource (lib "eagle-import") (part "WS2812B2020"))
    )
    (comp (ref "PD49")
      (value "WS2812B2020")
      (footprint "eagle-import:LED_WS2812-2020")
      (libsource (lib "eagle-import") (part "WS2812B2020"))
    )
    (comp (ref "PD50")
      (value "WS2812B2020")
      (footprint "eagle-import:LED_WS2812-2020")
      (libsource (lib "eagle-import") (part "WS2812B2020"))
    )
    (comp (ref "PD51")
      (value "WS2812B2020")
      (footprint "eagle-import:LED_WS2812-2020")
      (libsource (lib "eagle-import") (part "WS2812B2020"))
    )
    (comp (ref "PD52")
      (value "WS2812B2020")
      (footprint "eagle-import:LED_WS2812-2020")
      (libsource (lib "eagle-import") (part "WS2812B2020"))
    )
    (comp (ref "PD53")
      (value "WS2812B2020")
      (footprint "eagle-import:LED_WS2812-2020")
      (libsource (lib "eagle-import") (part "WS2812B2020"))
    )
    (comp (ref "PD54")
      (value "WS2812B2020")
      (footprint "eagle-import:LED_WS2812-2020")
      (libsource (lib "eagle-import") (part "WS2812B2020"))
    )
    (comp (ref "PD55")
      (value "WS2812B2020")
      (footprint "eagle-import:LED_WS2812-2020")
      (libsource (lib "eagle-import") (part "WS2812B2020"))
    )
    (comp (ref "PD56")
      (value "WS2812B2020")
      (footprint "eagle-import:LED_WS2812-2020")
      (libsource (lib "eagle-import") (part "WS2812B2020"))
    )
    (comp (ref "PD57")
      (value "WS2812B2020")
      (footprint "eagle-import:LED_WS2812-2020")
      (libsource (lib "eagle-import") (part "WS2812B2020"))
    )
    (comp (ref "PD58")
      (value "WS2812B2020")
      (footprint "eagle-import:LED_WS2812-2020")
      (libsource (lib "eagle-import") (part "WS2812B2020"))
    )
    (comp (ref "PD59")
      (value "WS2812B2020")
      (footprint "eagle-import:LED_WS2812-2020")
      (libsource (lib "eagle-import") (part "WS2812B2020"))
    )
    (comp (ref "PD60")
      (value "WS2812B2020")
      (footprint "eagle-import:LED_WS2812-2020")
      (libsource (lib "eagle-import") (part "WS2812B2020"))
    )
    (comp (ref "PD61")
      (value "WS2812B2020")
      (footprint "eagle-import:LED_WS2812-2020")
      (libsource (lib "eagle-import") (part "WS2812B2020"))
    )
    (comp (ref "PD62")
      (value "WS2812B2020")
      (footprint "eagle-import:LED_WS2812-2020")
      (libsource (lib "eagle-import") (part "WS2812B2020"))
    )
    (comp (ref "PD63")
      (value "WS2812B2020")
      (footprint "eagle-import:LED_WS2812-2020")
      (libsource (lib "eagle-import") (part "WS2812B2020"))
    )
    (comp (ref "PD64")
      (value "WS2812B2020")
      (footprint "eagle-import:LED_WS2812-2020")
      (libsource (lib "eagle-import") (part "WS2812B2020"))
    )
    (comp (ref "PD65")
      (value "WS2812B2020")
      (footprint "eagle-import:LED_WS2812-2020")
      (libsource (lib "eagle-import") (part "WS2812B2020"))
    )
    (comp (ref "PD66")
      (value "WS2812B2020")
      (footprint "eagle-import:LED_WS2812-2020")
      (libsource (lib "eagle-import") (part "WS2812B2020"))
    )
    (comp (ref "PD67")
      (value "WS2812B2020")
      (footprint "eagle-import:LED_WS2812-2020")
      (libsource (lib "eagle-import") (part "WS2812B2020"))
    )
    (comp (ref "PD68")
      (value "WS2812B2020")
      (footprint "eagle-import:LED_WS2812-2020")
      (libsource (lib "eagle-import") (part "WS2812B2020"))
    )
    (comp (ref "PD69")
      (value "WS2812B2020")
      (footprint "eagle-import:LED_WS2812-2020")
      (libsource (lib "eagle-import") (part "WS2812B2020"))
    )
    (comp (ref "PD70")
      (value "WS2812B2020")
      (footprint "eagle-import:LED_WS2812-2020")
      (libsource (lib "eagle-import") (part "WS2812B2020"))
    )
    (comp (ref "PD71")
      (value "WS2812B2020")
      (footprint "eagle-import:LED_WS2812-2020")
      (libsource (lib "eagle-import") (part "WS2812B2020"))
    )
    (comp (ref "PD72")
      (value "WS2812B2020")
      (footprint "eagle-import:LED_WS2812-2020")
      (libsource (lib "eagle-import") (part "WS2812B2020"))
    )
    (comp (ref "PD73")
      (value "WS2812B2020")
      (footprint "eagle-import:LED_WS2812-2020")
      (libsource (lib "eagle-import") (part "WS2812B2020"))
    )
    (comp (ref "PD74")
      (value "WS2812B2020")
      (footprint "eagle-import:LED_WS2812-2020")
      (libsource (lib "eagle-import") (part "WS2812B2020"))
    )
    (comp (ref "PD75")
      (value "WS2812B2020")
      (footprint "eagle-import:LED_WS2812-2020")
      (libsource (lib "eagle-import") (part "WS2812B2020"))
    )
    (comp (ref "PD76")
      (value "WS2812B2020")
      (footprint "eagle-import:LED_WS2812-2020")
      (libsource (lib "eagle-import") (part "WS2812B2020"))
    )
    (comp (ref "PD77")
      (value "WS2812B2020")
      (footprint "eagle-import:LED_WS2812-2020")
      (libsource (lib "eagle-import") (part "WS2812B2020"))
    )
    (comp (ref "PD78")
      (value "WS2812B2020")
      (footprint "eagle-import:LED_WS2812-2020")
      (libsource (lib "eagle-import") (part "WS2812B2020"))
    )
    (comp (ref "PD79")
      (value "WS2812B2020")
      (footprint "eagle-import:LED_WS2812-2020")
      (libsource (lib "eagle-import") (part "WS2812B2020"))
    )
    (comp (ref "PD80")
      (value "WS2812B2020")
      (footprint "eagle-import:LED_WS2812-2020")
      (libsource (lib "eagle-import") (part "WS2812B2020"))
    )
    (comp (ref "PD81")
      (value "WS2812B2020")
      (footprint "eagle-import:LED_WS2812-2020")
      (libsource (lib "eagle-import") (part "WS2812B2020"))
    )
    (comp (ref "PD82")
      (value "WS2812B2020")
      (footprint "eagle-import:LED_WS2812-2020")
      (libsource (lib "eagle-import") (part "WS2812B2020"))
    )
    (comp (ref "PD83")
      (value "WS2812B2020")
      (footprint "eagle-import:LED_WS2812-2020")
      (libsource (lib "eagle-import") (part "WS2812B2020"))
    )
    (comp (ref "PD84")
      (value "WS2812B2020")
      (footprint "eagle-import:LED_WS2812-2020")
      (libsource (lib "eagle-import") (part "WS2812B2020"))
    )
    (comp (ref "PD85")
      (value "WS2812B2020")
      (footprint "eagle-import:LED_WS2812-2020")
      (libsource (lib "eagle-import") (part "WS2812B2020"))
    )
    (comp (ref "PD86")
      (value "WS2812B2020")
      (footprint "eagle-import:LED_WS2812-2020")
      (libsource (lib "eagle-import") (part "WS2812B2020"))
    )
    (comp (ref "PD87")
      (value "WS2812B2020")
      (footprint "eagle-import:LED_WS2812-2020")
      (libsource (lib "eagle-import") (part "WS2812B2020"))
    )
    (comp (ref "PD88")
      (value "WS2812B2020")
      (footprint "eagle-import:LED_WS2812-2020")
      (libsource (lib "eagle-import") (part "WS2812B2020"))
    )
    (comp (ref "PD89")
      (value "WS2812B2020")
      (footprint "eagle-import:LED_WS2812-2020")
      (libsource (lib "eagle-import") (part "WS2812B2020"))
    )
    (comp (ref "PD90")
      (value "WS2812B2020")
      (footprint "eagle-import:LED_WS2812-2020")
      (libsource (lib "eagle-import") (part "WS2812B2020"))
    )
    (comp (ref "PD91")
      (value "WS2812B2020")
      (footprint "eagle-import:LED_WS2812-2020")
      (libsource (lib "eagle-import") (part "WS2812B2020"))
    )
    (comp (ref "PD92")
      (value "WS2812B2020")
      (footprint "eagle-import:LED_WS2812-2020")
      (libsource (lib "eagle-import") (part "WS2812B2020"))
    )
    (comp (ref "PD93")
      (value "WS2812B2020")
      (footprint "eagle-import:LED_WS2812-2020")
      (libsource (lib "eagle-import") (part "WS2812B2020"))
    )
    (comp (ref "PD94")
      (value "WS2812B2020")
      (footprint "eagle-import:LED_WS2812-2020")
      (libsource (lib "eagle-import") (part "WS2812B2020"))
    )
    (comp (ref "PD95")
      (value "WS2812B2020")
      (footprint "eagle-import:LED_WS2812-2020")
      (libsource (lib "eagle-import") (part "WS2812B2020"))
    )
    (comp (ref "PD96")
      (value "WS2812B2020")
      (footprint "eagle-import:LED_WS2812-2020")
      (libsource (lib "eagle-import") (part "WS2812B2020"))
    )
    (comp (ref "PD97")
      (value "WS2812B2020")
      (footprint "eagle-import:LED_WS2812-2020")
      (libsource (lib "eagle-import") (part "WS2812B2020"))
    )
    (comp (ref "PD98")
      (value "WS2812B2020")
      (footprint "eagle-import:LED_WS2812-2020")
      (libsource (lib "eagle-import") (part "WS2812B2020"))
    )
    (comp (ref "PD99")
      (value "WS2812B2020")
      (footprint "eagle-import:LED_WS2812-2020")
      (libsource (lib "eagle-import") (part "WS2812B2020"))
    )
    (comp (ref "PD100")
      (value "WS2812B2020")
      (footprint "eagle-import:LED_WS2812-2020")
      (libsource (lib "eagle-import") (part "WS2812B2020"))
    )
    (comp (ref "PD101")
      (value "WS2812B2020")
      (footprint "eagle-import:LED_WS2812-2020")
      (libsource (lib "eagle-import") (part "WS2812B2020"))
    )
    (comp (ref "PD102")
      (value "WS2812B2020")
      (footprint "eagle-import:LED_WS2812-2020")
      (libsource (lib "eagle-import") (part "WS2812B2020"))
    )
    (comp (ref "PD103")
      (value "WS2812B2020")
      (footprint "eagle-import:LED_WS2812-2020")
      (libsource (lib "eagle-import") (part "WS2812B2020"))
    )
    (comp (ref "PD104")
      (value "WS2812B2020")
      (footprint "eagle-import:LED_WS2812-2020")
      (libsource (lib "eagle-import") (part "WS2812B2020"))
    )
    (comp (ref "PD105")
      (value "WS2812B2020")
      (footprint "eagle-import:LED_WS2812-2020")
      (libsource (lib "eagle-import") (part "WS2812B2020"))
    )
    (comp (ref "PD106")
      (value "WS2812B2020")
      (footprint "eagle-import:LED_WS2812-2020")
      (libsource (lib "eagle-import") (part "WS2812B2020"))
    )
    (comp (ref "PD107")
      (value "WS2812B2020")
      (footprint "eagle-import:LED_WS2812-2020")
      (libsource (lib "eagle-import") (part "WS2812B2020"))
    )
    (comp (ref "PD108")
      (value "WS2812B2020")
      (footprint "eagle-import:LED_WS2812-2020")
      (libsource (lib "eagle-import") (part "WS2812B2020"))
    )
    (comp (ref "PD109")
      (value "WS2812B2020")
      (footprint "eagle-import:LED_WS2812-2020")
      (libsource (lib "eagle-import") (part "WS2812B2020"))
    )
    (comp (ref "PD110")
      (value "WS2812B2020")
      (footprint "eagle-import:LED_WS2812-2020")
      (libsource (lib "eagle-import") (part "WS2812B2020"))
    )
    (comp (ref "C45")
      (value "1u")
      (footprint "eagle-import:C0805K")
      (libsource (lib "eagle-import") (part "C-EUC0805K"))
    )
    (comp (ref "L9")
      (value "BLM18PG600")
      (footprint "eagle-import:L1608")
      (libsource (lib "eagle-import") (part "L_EU_L0603"))
    )
    (comp (ref "L10")
      (value "BLM18PG600")
      (footprint "eagle-import:L1608")
      (libsource (lib "eagle-import") (part "L_EU_L0603"))
    )
    (comp (ref "R70")
      (value "390k")
      (footprint "eagle-import:R0805")
      (libsource (lib "eagle-import") (part "R-EU_R0805"))
    )
    (comp (ref "R71")
      (value "0")
      (footprint "eagle-import:R0805")
      (libsource (lib "eagle-import") (part "R-EU_R0805"))
    )
    (comp (ref "V2")
      (value "BAT60")
      (footprint "eagle-import:SOD323-R")
      (libsource (lib "eagle-import") (part "BAT60"))
    )
    (comp (ref "X5")
      (value "52745-3090")
      (footprint "eagle-import:52745-3090")
      (fields (field (name "MF") "MOLEX"))
      (libsource (lib "eagle-import") (part "52745-3090"))
    )
    (comp (ref "C42")
      (value "100nF")
      (footprint "eagle-import:C0805K")
      (libsource (lib "eagle-import") (part "rcl_334_C-EUC0805K"))
    )
    (comp (ref "C43")
      (value "100uF / 50V")
      (footprint "eagle-import:PANASONIC_F")
      (libsource (lib "eagle-import") (part "CPOL-EUF"))
    )
    (comp (ref "C44")
      (value "1u")
      (footprint "eagle-import:C0805K")
      (libsource (lib "eagle-import") (part "C-EUC0805K"))
    )
    (comp (ref "DISPLAY1")
      (value "REX001602CYPP5N0")
      (footprint "eagle-import:33PIN_LCD16X2")
      (libsource (lib "eagle-import") (part "REX001602CYPP5N0"))
    )
    (comp (ref "L8")
      (value "BLM18PG600")
      (footprint "eagle-import:L1608")
      (libsource (lib "eagle-import") (part "L_EU_L0603"))
    )
    (comp (ref "R68")
      (value "0")
      (footprint "eagle-import:R0805")
      (libsource (lib "eagle-import") (part "R-EU_R0805"))
    )
    (comp (ref "R69")
      (value "390k")
      (footprint "eagle-import:R0805")
      (libsource (lib "eagle-import") (part "R-EU_R0805"))
    )
    (comp (ref "SJ2")
      (value "SJ2W")
      (footprint "eagle-import:SJ_2")
      (libsource (lib "eagle-import") (part "SJ2W"))
    )
    (comp (ref "SJ3")
      (value "SJ2W")
      (footprint "eagle-import:SJ_2")
      (libsource (lib "eagle-import") (part "SJ2W"))
    )
    (comp (ref "SJ4")
      (value "SJ2W")
      (footprint "eagle-import:SJ_2")
      (libsource (lib "eagle-import") (part "SJ2W"))
    )
    (comp (ref "SJ5")
      (value "SJ2W")
      (footprint "eagle-import:SJ_2")
      (libsource (lib "eagle-import") (part "SJ2W"))
    )
    (comp (ref "LED1")
      (value "LEDCHIPLED_0603")
      (footprint "eagle-import:CHIPLED_0603")
      (libsource (lib "eagle-import") (part "LEDCHIPLED_0603"))
    )
    (comp (ref "LED2")
      (value "LEDCHIPLED_0603")
      (footprint "eagle-import:CHIPLED_0603")
      (libsource (lib "eagle-import") (part "LEDCHIPLED_0603"))
    )
    (comp (ref "LED3")
      (value "LEDCHIPLED_0603")
      (footprint "eagle-import:CHIPLED_0603")
      (libsource (lib "eagle-import") (part "LEDCHIPLED_0603"))
    )
    (comp (ref "LED4")
      (value "LEDCHIPLED_0603")
      (footprint "eagle-import:CHIPLED_0603")
      (libsource (lib "eagle-import") (part "LEDCHIPLED_0603"))
    )
    (comp (ref "LED5")
      (value "LEDCHIPLED_0603")
      (footprint "eagle-import:CHIPLED_0603")
      (libsource (lib "eagle-import") (part "LEDCHIPLED_0603"))
    )
    (comp (ref "LED6")
      (value "LEDCHIPLED_0603")
      (footprint "eagle-import:CHIPLED_0603")
      (libsource (lib "eagle-import") (part "LEDCHIPLED_0603"))
    )
    (comp (ref "LED7")
      (value "LEDCHIPLED_0603")
      (footprint "eagle-import:CHIPLED_0603")
      (libsource (lib "eagle-import") (part "LEDCHIPLED_0603"))
    )
    (comp (ref "LED8")
      (value "LEDCHIPLED_0603")
      (footprint "eagle-import:CHIPLED_0603")
      (libsource (lib "eagle-import") (part "LEDCHIPLED_0603"))
    )
    (comp (ref "LED9")
      (value "LEDCHIPLED_0603")
      (footprint "eagle-import:CHIPLED_0603")
      (libsource (lib "eagle-import") (part "LEDCHIPLED_0603"))
    )
    (comp (ref "LED10")
      (value "LEDCHIPLED_0603")
      (footprint "eagle-import:CHIPLED_0603")
      (libsource (lib "eagle-import") (part "LEDCHIPLED_0603"))
    )
    (comp (ref "LED11")
      (value "LEDCHIPLED_0603")
      (footprint "eagle-import:CHIPLED_0603")
      (libsource (lib "eagle-import") (part "LEDCHIPLED_0603"))
    )
    (comp (ref "LED12")
      (value "LEDCHIPLED_0603")
      (footprint "eagle-import:CHIPLED_0603")
      (libsource (lib "eagle-import") (part "LEDCHIPLED_0603"))
    )
    (comp (ref "LED13")
      (value "LEDCHIPLED_0603")
      (footprint "eagle-import:CHIPLED_0603")
      (libsource (lib "eagle-import") (part "LEDCHIPLED_0603"))
    )
    (comp (ref "LED14")
      (value "LEDCHIPLED_0603")
      (footprint "eagle-import:CHIPLED_0603")
      (libsource (lib "eagle-import") (part "LEDCHIPLED_0603"))
    )
    (comp (ref "LED15")
      (value "LEDCHIPLED_0603")
      (footprint "eagle-import:CHIPLED_0603")
      (libsource (lib "eagle-import") (part "LEDCHIPLED_0603"))
    )
    (comp (ref "LED16")
      (value "LEDCHIPLED_0603")
      (footprint "eagle-import:CHIPLED_0603")
      (libsource (lib "eagle-import") (part "LEDCHIPLED_0603"))
    )
    (comp (ref "LED17")
      (value "LEDCHIPLED_0603")
      (footprint "eagle-import:CHIPLED_0603")
      (libsource (lib "eagle-import") (part "LEDCHIPLED_0603"))
    )
    (comp (ref "LED18")
      (value "LEDCHIPLED_0603")
      (footprint "eagle-import:CHIPLED_0603")
      (libsource (lib "eagle-import") (part "LEDCHIPLED_0603"))
    )
    (comp (ref "LED19")
      (value "LEDCHIPLED_0603")
      (footprint "eagle-import:CHIPLED_0603")
      (libsource (lib "eagle-import") (part "LEDCHIPLED_0603"))
    )
    (comp (ref "LED20")
      (value "LEDCHIPLED_0603")
      (footprint "eagle-import:CHIPLED_0603")
      (libsource (lib "eagle-import") (part "LEDCHIPLED_0603"))
    )
    (comp (ref "LED21")
      (value "LEDCHIPLED_0603")
      (footprint "eagle-import:CHIPLED_0603")
      (libsource (lib "eagle-import") (part "LEDCHIPLED_0603"))
    )
    (comp (ref "LED22")
      (value "LEDCHIPLED_0603")
      (footprint "eagle-import:CHIPLED_0603")
      (libsource (lib "eagle-import") (part "LEDCHIPLED_0603"))
    )
    (comp (ref "LED23")
      (value "LEDCHIPLED_0603")
      (footprint "eagle-import:CHIPLED_0603")
      (libsource (lib "eagle-import") (part "LEDCHIPLED_0603"))
    )
    (comp (ref "LED24")
      (value "LEDCHIPLED_0603")
      (footprint "eagle-import:CHIPLED_0603")
      (libsource (lib "eagle-import") (part "LEDCHIPLED_0603"))
    )
    (comp (ref "LED25")
      (value "LEDCHIPLED_0603")
      (footprint "eagle-import:CHIPLED_0603")
      (libsource (lib "eagle-import") (part "LEDCHIPLED_0603"))
    )
    (comp (ref "LED26")
      (value "LEDCHIPLED_0603")
      (footprint "eagle-import:CHIPLED_0603")
      (libsource (lib "eagle-import") (part "LEDCHIPLED_0603"))
    )
    (comp (ref "LED27")
      (value "LEDCHIPLED_0603")
      (footprint "eagle-import:CHIPLED_0603")
      (libsource (lib "eagle-import") (part "LEDCHIPLED_0603"))
    )
    (comp (ref "LED28")
      (value "LEDCHIPLED_0603")
      (footprint "eagle-import:CHIPLED_0603")
      (libsource (lib "eagle-import") (part "LEDCHIPLED_0603"))
    )
    (comp (ref "LED29")
      (value "LEDCHIPLED_0603")
      (footprint "eagle-import:CHIPLED_0603")
      (libsource (lib "eagle-import") (part "LEDCHIPLED_0603"))
    )
    (comp (ref "LED30")
      (value "LEDCHIPLED_0603")
      (footprint "eagle-import:CHIPLED_0603")
      (libsource (lib "eagle-import") (part "LEDCHIPLED_0603"))
    )
    (comp (ref "LED31")
      (value "LEDCHIPLED_0603")
      (footprint "eagle-import:CHIPLED_0603")
      (libsource (lib "eagle-import") (part "LEDCHIPLED_0603"))
    )
    (comp (ref "LED32")
      (value "LEDCHIPLED_0603")
      (footprint "eagle-import:CHIPLED_0603")
      (libsource (lib "eagle-import") (part "LEDCHIPLED_0603"))
    )
    (comp (ref "LED33")
      (value "LEDCHIPLED_0603")
      (footprint "eagle-import:CHIPLED_0603")
      (libsource (lib "eagle-import") (part "LEDCHIPLED_0603"))
    )
    (comp (ref "LED34")
      (value "LEDCHIPLED_0603")
      (footprint "eagle-import:CHIPLED_0603")
      (libsource (lib "eagle-import") (part "LEDCHIPLED_0603"))
    )
    (comp (ref "LED35")
      (value "LEDCHIPLED_0603")
      (footprint "eagle-import:CHIPLED_0603")
      (libsource (lib "eagle-import") (part "LEDCHIPLED_0603"))
    )
    (comp (ref "LED36")
      (value "LEDCHIPLED_0603")
      (footprint "eagle-import:CHIPLED_0603")
      (libsource (lib "eagle-import") (part "LEDCHIPLED_0603"))
    )
    (comp (ref "LED37")
      (value "LEDCHIPLED_0603")
      (footprint "eagle-import:CHIPLED_0603")
      (libsource (lib "eagle-import") (part "LEDCHIPLED_0603"))
    )
    (comp (ref "R6")
      (value "1M")
      (footprint "eagle-import:R0805")
      (libsource (lib "eagle-import") (part "R-EU_R0805"))
    )
    (comp (ref "R7")
      (value "1M")
      (footprint "eagle-import:R0805")
      (libsource (lib "eagle-import") (part "R-EU_R0805"))
    )
    (comp (ref "R8")
      (value "1M")
      (footprint "eagle-import:R0805")
      (libsource (lib "eagle-import") (part "R-EU_R0805"))
    )
    (comp (ref "R9")
      (value "1k")
      (footprint "eagle-import:R0805")
      (libsource (lib "eagle-import") (part "R-EU_R0805"))
    )
    (comp (ref "R10")
      (value "1k")
      (footprint "eagle-import:R0805")
      (libsource (lib "eagle-import") (part "R-EU_R0805"))
    )
    (comp (ref "R11")
      (value "1k")
      (footprint "eagle-import:R0805")
      (libsource (lib "eagle-import") (part "R-EU_R0805"))
    )
    (comp (ref "R12")
      (value "120")
      (footprint "eagle-import:R0805")
      (libsource (lib "eagle-import") (part "R-EU_R0805"))
    )
    (comp (ref "R13")
      (value "120")
      (footprint "eagle-import:R0805")
      (libsource (lib "eagle-import") (part "R-EU_R0805"))
    )
    (comp (ref "R14")
      (value "30")
      (footprint "eagle-import:R0805")
      (libsource (lib "eagle-import") (part "R-EU_R0805"))
    )
    (comp (ref "R15")
      (value "120")
      (footprint "eagle-import:R0805")
      (libsource (lib "eagle-import") (part "R-EU_R0805"))
    )
    (comp (ref "R16")
      (value "120")
      (footprint "eagle-import:R0805")
      (libsource (lib "eagle-import") (part "R-EU_R0805"))
    )
    (comp (ref "R17")
      (value "30")
      (footprint "eagle-import:R0805")
      (libsource (lib "eagle-import") (part "R-EU_R0805"))
    )
    (comp (ref "R18")
      (value "120")
      (footprint "eagle-import:R0805")
      (libsource (lib "eagle-import") (part "R-EU_R0805"))
    )
    (comp (ref "R19")
      (value "120")
      (footprint "eagle-import:R0805")
      (libsource (lib "eagle-import") (part "R-EU_R0805"))
    )
    (comp (ref "R20")
      (value "30")
      (footprint "eagle-import:R0805")
      (libsource (lib "eagle-import") (part "R-EU_R0805"))
    )
    (comp (ref "R21")
      (value "120")
      (footprint "eagle-import:R0805")
      (libsource (lib "eagle-import") (part "R-EU_R0805"))
    )
    (comp (ref "R22")
      (value "120")
      (footprint "eagle-import:R0805")
      (libsource (lib "eagle-import") (part "R-EU_R0805"))
    )
    (comp (ref "R23")
      (value "30")
      (footprint "eagle-import:R0805")
      (libsource (lib "eagle-import") (part "R-EU_R0805"))
    )
    (comp (ref "R24")
      (value "120")
      (footprint "eagle-import:R0805")
      (libsource (lib "eagle-import") (part "R-EU_R0805"))
    )
    (comp (ref "R25")
      (value "120")
      (footprint "eagle-import:R0805")
      (libsource (lib "eagle-import") (part "R-EU_R0805"))
    )
    (comp (ref "R26")
      (value "30")
      (footprint "eagle-import:R0805")
      (libsource (lib "eagle-import") (part "R-EU_R0805"))
    )
    (comp (ref "R27")
      (value "120")
      (footprint "eagle-import:R0805")
      (libsource (lib "eagle-import") (part "R-EU_R0805"))
    )
    (comp (ref "R28")
      (value "120")
      (footprint "eagle-import:R0805")
      (libsource (lib "eagle-import") (part "R-EU_R0805"))
    )
    (comp (ref "R29")
      (value "30")
      (footprint "eagle-import:R0805")
      (libsource (lib "eagle-import") (part "R-EU_R0805"))
    )
    (comp (ref "R30")
      (value "30")
      (footprint "eagle-import:R0805")
      (libsource (lib "eagle-import") (part "R-EU_R0805"))
    )
    (comp (ref "R31")
      (value "120")
      (footprint "eagle-import:R0805")
      (libsource (lib "eagle-import") (part "R-EU_R0805"))
    )
    (comp (ref "R32")
      (value "120")
      (footprint "eagle-import:R0805")
      (libsource (lib "eagle-import") (part "R-EU_R0805"))
    )
    (comp (ref "R33")
      (value "30")
      (footprint "eagle-import:R0805")
      (libsource (lib "eagle-import") (part "R-EU_R0805"))
    )
    (comp (ref "R34")
      (value "30")
      (footprint "eagle-import:R0805")
      (libsource (lib "eagle-import") (part "R-EU_R0805"))
    )
    (comp (ref "R35")
      (value "30")
      (footprint "eagle-import:R0805")
      (libsource (lib "eagle-import") (part "R-EU_R0805"))
    )
    (comp (ref "R36")
      (value "30")
      (footprint "eagle-import:R0805")
      (libsource (lib "eagle-import") (part "R-EU_R0805"))
    )
    (comp (ref "R37")
      (value "30")
      (footprint "eagle-import:R0805")
      (libsource (lib "eagle-import") (part "R-EU_R0805"))
    )
    (comp (ref "R38")
      (value "30")
      (footprint "eagle-import:R0805")
      (libsource (lib "eagle-import") (part "R-EU_R0805"))
    )
    (comp (ref "R39")
      (value "30")
      (footprint "eagle-import:R0805")
      (libsource (lib "eagle-import") (part "R-EU_R0805"))
    )
    (comp (ref "R40")
      (value "30")
      (footprint "eagle-import:R0805")
      (libsource (lib "eagle-import") (part "R-EU_R0805"))
    )
    (comp (ref "R41")
      (value "30")
      (footprint "eagle-import:R0805")
      (libsource (lib "eagle-import") (part "R-EU_R0805"))
    )
    (comp (ref "R42")
      (value "30")
      (footprint "eagle-import:R0805")
      (libsource (lib "eagle-import") (part "R-EU_R0805"))
    )
    (comp (ref "R43")
      (value "30")
      (footprint "eagle-import:R0805")
      (libsource (lib "eagle-import") (part "R-EU_R0805"))
    )
    (comp (ref "R44")
      (value "30")
      (footprint "eagle-import:R0805")
      (libsource (lib "eagle-import") (part "R-EU_R0805"))
    )
    (comp (ref "R45")
      (value "30")
      (footprint "eagle-import:R0805")
      (libsource (lib "eagle-import") (part "R-EU_R0805"))
    )
    (comp (ref "R46")
      (value "30")
      (footprint "eagle-import:R0805")
      (libsource (lib "eagle-import") (part "R-EU_R0805"))
    )
    (comp (ref "R47")
      (value "30")
      (footprint "eagle-import:R0805")
      (libsource (lib "eagle-import") (part "R-EU_R0805"))
    )
    (comp (ref "R48")
      (value "30")
      (footprint "eagle-import:R0805")
      (libsource (lib "eagle-import") (part "R-EU_R0805"))
    )
    (comp (ref "T1")
      (value "SOT89 NPN BCE")
      (footprint "eagle-import:SOT89-BCE")
      (libsource (lib "eagle-import") (part "-NPN-SOT89-BCE"))
    )
    (comp (ref "T2")
      (value "SOT89 NPN BCE")
      (footprint "eagle-import:SOT89-BCE")
      (libsource (lib "eagle-import") (part "-NPN-SOT89-BCE"))
    )
    (comp (ref "T3")
      (value "SOT89 NPN BCE")
      (footprint "eagle-import:SOT89-BCE")
      (libsource (lib "eagle-import") (part "-NPN-SOT89-BCE"))
    )
  )
  (nets
    (net (code "1") (name "+3V3") (class "Default")
      (node (ref "C32") (pin "+") (pinfunction "+_+") (pintype "passive"))
      (node (ref "C35") (pin "2") (pinfunction "2_2") (pintype "passive"))
      (node (ref "C40") (pin "1") (pinfunction "1_1") (pintype "passive"))
      (node (ref "C41") (pin "1") (pinfunction "1_1") (pintype "passive"))
      (node (ref "C42") (pin "1") (pinfunction "1_1") (pintype "passive"))
      (node (ref "C43") (pin "+") (pinfunction "+_+") (pintype "passive"))
      (node (ref "C5") (pin "2") (pinfunction "2_2") (pintype "passive"))
      (node (ref "DISPLAY1") (pin "5") (pinfunction "SHLC_5") (pintype "bidirectional"))
      (node (ref "DISPLAY1") (pin "6") (pinfunction "SHLS_6") (pintype "bidirectional"))
      (node (ref "DISPLAY1") (pin "7") (pinfunction "VDD_7") (pintype "bidirectional"))
      (node (ref "DISPLAY1") (pin "8") (pinfunction "VDDIO_8") (pintype "bidirectional"))
      (node (ref "IC1") (pin "24") (pinfunction "VCC_24") (pintype "bidirectional"))
      (node (ref "JP1") (pin "1") (pinfunction "1_1") (pintype "passive"))
      (node (ref "JP2") (pin "1") (pinfunction "1_1") (pintype "passive"))
      (node (ref "JP3") (pin "1") (pinfunction "1_1") (pintype "passive"))
      (node (ref "L2") (pin "2") (pinfunction "2_2") (pintype "passive"))
      (node (ref "L3") (pin "2") (pinfunction "2_2") (pintype "passive"))
      (node (ref "L5") (pin "1") (pinfunction "1_1") (pintype "passive"))
      (node (ref "L7") (pin "1") (pinfunction "1_1") (pintype "passive"))
      (node (ref "L8") (pin "1") (pinfunction "1_1") (pintype "passive"))
      (node (ref "L9") (pin "1") (pinfunction "1_1") (pintype "passive"))
      (node (ref "P2") (pin "2") (pinfunction "2_2") (pintype "passive"))
      (node (ref "P3") (pin "2") (pinfunction "2_2") (pintype "passive"))
      (node (ref "P4") (pin "2") (pinfunction "2_2") (pintype "passive"))
      (node (ref "R14") (pin "2") (pinfunction "2_2") (pintype "passive"))
      (node (ref "R17") (pin "2") (pinfunction "2_2") (pintype "passive"))
      (node (ref "R20") (pin "2") (pinfunction "2_2") (pintype "passive"))
      (node (ref "R23") (pin "2") (pinfunction "2_2") (pintype "passive"))
      (node (ref "R26") (pin "2") (pinfunction "2_2") (pintype "passive"))
      (node (ref "R29") (pin "2") (pinfunction "2_2") (pintype "passive"))
      (node (ref "R30") (pin "2") (pinfunction "2_2") (pintype "passive"))
      (node (ref "R33") (pin "2") (pinfunction "2_2") (pintype "passive"))
      (node (ref "R34") (pin "2") (pinfunction "2_2") (pintype "passive"))
      (node (ref "R35") (pin "2") (pinfunction "2_2") (pintype "passive"))
      (node (ref "R36") (pin "2") (pinfunction "2_2") (pintype "passive"))
      (node (ref "R37") (pin "2") (pinfunction "2_2") (pintype "passive"))
      (node (ref "R38") (pin "2") (pinfunction "2_2") (pintype "passive"))
      (node (ref "R39") (pin "2") (pinfunction "2_2") (pintype "passive"))
      (node (ref "R40") (pin "2") (pinfunction "2_2") (pintype "passive"))
      (node (ref "R41") (pin "2") (pinfunction "2_2") (pintype "passive"))
      (node (ref "R42") (pin "2") (pinfunction "2_2") (pintype "passive"))
      (node (ref "R43") (pin "2") (pinfunction "2_2") (pintype "passive"))
      (node (ref "R44") (pin "2") (pinfunction "2_2") (pintype "passive"))
      (node (ref "R45") (pin "2") (pinfunction "2_2") (pintype "passive"))
      (node (ref "R46") (pin "2") (pinfunction "2_2") (pintype "passive"))
      (node (ref "R47") (pin "2") (pinfunction "2_2") (pintype "passive"))
      (node (ref "R48") (pin "2") (pinfunction "2_2") (pintype "passive"))
      (node (ref "R53") (pin "2") (pinfunction "2_2") (pintype "passive"))
      (node (ref "R54") (pin "1") (pinfunction "1_1") (pintype "passive"))
      (node (ref "R58") (pin "2") (pinfunction "2_2") (pintype "passive"))
      (node (ref "R59") (pin "2") (pinfunction "2_2") (pintype "passive"))
      (node (ref "R60") (pin "2") (pinfunction "2_2") (pintype "passive"))
      (node (ref "R61") (pin "2") (pinfunction "2_2") (pintype "passive"))
      (node (ref "R62") (pin "2") (pinfunction "2_2") (pintype "passive"))
      (node (ref "R63") (pin "2") (pinfunction "2_2") (pintype "passive"))
      (node (ref "R64") (pin "2") (pinfunction "2_2") (pintype "passive"))
      (node (ref "R65") (pin "2") (pinfunction "2_2") (pintype "passive"))
      (node (ref "R66") (pin "2") (pinfunction "2_2") (pintype "passive"))
      (node (ref "R67") (pin "2") (pinfunction "2_2") (pintype "passive"))
      (node (ref "TP1") (pin "TP") (pinfunction "TP_TP") (pintype "input"))
      (node (ref "U1") (pin "5") (pinfunction "VIO_5") (pintype "bidirectional"))
      (node (ref "U10") (pin "2") (pinfunction "VCC_2") (pintype "power_in"))
      (node (ref "U11") (pin "2") (pinfunction "VCC_2") (pintype "power_in"))
      (node (ref "U4") (pin "3") (pinfunction "VOUT_3") (pintype "output"))
      (node (ref "U8") (pin "8") (pinfunction "VCC_8") (pintype "power_in"))
      (node (ref "U9") (pin "2") (pinfunction "VCC_2") (pintype "power_in"))
    )
    (net (code "2") (name "+5V") (class "Default")
      (node (ref "C15") (pin "2") (pinfunction "2_2") (pintype "passive"))
      (node (ref "C16") (pin "2") (pinfunction "2_2") (pintype "passive"))
      (node (ref "C17") (pin "2") (pinfunction "2_2") (pintype "passive"))
      (node (ref "C18") (pin "1") (pinfunction "1_1") (pintype "passive"))
      (node (ref "C19") (pin "1") (pinfunction "1_1") (pintype "passive"))
      (node (ref "C20") (pin "1") (pinfunction "1_1") (pintype "passive"))
      (node (ref "C21") (pin "1") (pinfunction "1_1") (pintype "passive"))
      (node (ref "C22") (pin "1") (pinfunction "1_1") (pintype "passive"))
      (node (ref "C23") (pin "+") (pinfunction "+_+") (pintype "passive"))
      (node (ref "C25") (pin "2") (pinfunction "2_2") (pintype "passive"))
      (node (ref "C33") (pin "+") (pinfunction "+_+") (pintype "passive"))
      (node (ref "C36") (pin "2") (pinfunction "2_2") (pintype "passive"))
      (node (ref "L1") (pin "2") (pinfunction "2_2") (pintype "passive"))
      (node (ref "L6") (pin "1") (pinfunction "1_1") (pintype "passive"))
      (node (ref "PD1") (pin "1") (pinfunction "VDD_1") (pintype "power_in"))
      (node (ref "PD10") (pin "1") (pinfunction "VDD_1") (pintype "power_in"))
      (node (ref "PD100") (pin "4") (pinfunction "VDD_4") (pintype "power_in"))
      (node (ref "PD101") (pin "4") (pinfunction "VDD_4") (pintype "power_in"))
      (node (ref "PD102") (pin "4") (pinfunction "VDD_4") (pintype "power_in"))
      (node (ref "PD103") (pin "4") (pinfunction "VDD_4") (pintype "power_in"))
      (node (ref "PD104") (pin "4") (pinfunction "VDD_4") (pintype "power_in"))
      (node (ref "PD105") (pin "4") (pinfunction "VDD_4") (pintype "power_in"))
      (node (ref "PD106") (pin "4") (pinfunction "VDD_4") (pintype "power_in"))
      (node (ref "PD107") (pin "4") (pinfunction "VDD_4") (pintype "power_in"))
      (node (ref "PD108") (pin "4") (pinfunction "VDD_4") (pintype "power_in"))
      (node (ref "PD109") (pin "4") (pinfunction "VDD_4") (pintype "power_in"))
      (node (ref "PD11") (pin "1") (pinfunction "VDD_1") (pintype "power_in"))
      (node (ref "PD110") (pin "4") (pinfunction "VDD_4") (pintype "power_in"))
      (node (ref "PD12") (pin "1") (pinfunction "VDD_1") (pintype "power_in"))
      (node (ref "PD13") (pin "1") (pinfunction "VDD_1") (pintype "power_in"))
      (node (ref "PD14") (pin "1") (pinfunction "VDD_1") (pintype "power_in"))
      (node (ref "PD15") (pin "1") (pinfunction "VDD_1") (pintype "power_in"))
      (node (ref "PD16") (pin "1") (pinfunction "VDD_1") (pintype "power_in"))
      (node (ref "PD17") (pin "4") (pinfunction "VDD_4") (pintype "power_in"))
      (node (ref "PD18") (pin "4") (pinfunction "VDD_4") (pintype "power_in"))
      (node (ref "PD19") (pin "4") (pinfunction "VDD_4") (pintype "power_in"))
      (node (ref "PD2") (pin "1") (pinfunction "VDD_1") (pintype "power_in"))
      (node (ref "PD20") (pin "4") (pinfunction "VDD_4") (pintype "power_in"))
      (node (ref "PD21") (pin "4") (pinfunction "VDD_4") (pintype "power_in"))
      (node (ref "PD22") (pin "4") (pinfunction "VDD_4") (pintype "power_in"))
      (node (ref "PD23") (pin "4") (pinfunction "VDD_4") (pintype "power_in"))
      (node (ref "PD24") (pin "4") (pinfunction "VDD_4") (pintype "power_in"))
      (node (ref "PD25") (pin "4") (pinfunction "VDD_4") (pintype "power_in"))
      (node (ref "PD26") (pin "4") (pinfunction "VDD_4") (pintype "power_in"))
      (node (ref "PD27") (pin "4") (pinfunction "VDD_4") (pintype "power_in"))
      (node (ref "PD28") (pin "4") (pinfunction "VDD_4") (pintype "power_in"))
      (node (ref "PD29") (pin "4") (pinfunction "VDD_4") (pintype "power_in"))
      (node (ref "PD3") (pin "1") (pinfunction "VDD_1") (pintype "power_in"))
      (node (ref "PD30") (pin "4") (pinfunction "VDD_4") (pintype "power_in"))
      (node (ref "PD31") (pin "4") (pinfunction "VDD_4") (pintype "power_in"))
      (node (ref "PD32") (pin "4") (pinfunction "VDD_4") (pintype "power_in"))
      (node (ref "PD33") (pin "4") (pinfunction "VDD_4") (pintype "power_in"))
      (node (ref "PD34") (pin "4") (pinfunction "VDD_4") (pintype "power_in"))
      (node (ref "PD35") (pin "4") (pinfunction "VDD_4") (pintype "power_in"))
      (node (ref "PD36") (pin "4") (pinfunction "VDD_4") (pintype "power_in"))
      (node (ref "PD37") (pin "4") (pinfunction "VDD_4") (pintype "power_in"))
      (node (ref "PD38") (pin "4") (pinfunction "VDD_4") (pintype "power_in"))
      (node (ref "PD39") (pin "4") (pinfunction "VDD_4") (pintype "power_in"))
      (node (ref "PD4") (pin "1") (pinfunction "VDD_1") (pintype "power_in"))
      (node (ref "PD40") (pin "4") (pinfunction "VDD_4") (pintype "power_in"))
      (node (ref "PD41") (pin "4") (pinfunction "VDD_4") (pintype "power_in"))
      (node (ref "PD42") (pin "4") (pinfunction "VDD_4") (pintype "power_in"))
      (node (ref "PD43") (pin "4") (pinfunction "VDD_4") (pintype "power_in"))
      (node (ref "PD44") (pin "4") (pinfunction "VDD_4") (pintype "power_in"))
      (node (ref "PD45") (pin "4") (pinfunction "VDD_4") (pintype "power_in"))
      (node (ref "PD46") (pin "4") (pinfunction "VDD_4") (pintype "power_in"))
      (node (ref "PD47") (pin "4") (pinfunction "VDD_4") (pintype "power_in"))
      (node (ref "PD48") (pin "4") (pinfunction "VDD_4") (pintype "power_in"))
      (node (ref "PD49") (pin "4") (pinfunction "VDD_4") (pintype "power_in"))
      (node (ref "PD5") (pin "1") (pinfunction "VDD_1") (pintype "power_in"))
      (node (ref "PD50") (pin "4") (pinfunction "VDD_4") (pintype "power_in"))
      (node (ref "PD51") (pin "4") (pinfunction "VDD_4") (pintype "power_in"))
      (node (ref "PD52") (pin "4") (pinfunction "VDD_4") (pintype "power_in"))
      (node (ref "PD53") (pin "4") (pinfunction "VDD_4") (pintype "power_in"))
      (node (ref "PD54") (pin "4") (pinfunction "VDD_4") (pintype "power_in"))
      (node (ref "PD55") (pin "4") (pinfunction "VDD_4") (pintype "power_in"))
      (node (ref "PD56") (pin "4") (pinfunction "VDD_4") (pintype "power_in"))
      (node (ref "PD57") (pin "4") (pinfunction "VDD_4") (pintype "power_in"))
      (node (ref "PD58") (pin "4") (pinfunction "VDD_4") (pintype "power_in"))
      (node (ref "PD59") (pin "4") (pinfunction "VDD_4") (pintype "power_in"))
      (node (ref "PD6") (pin "1") (pinfunction "VDD_1") (pintype "power_in"))
      (node (ref "PD60") (pin "4") (pinfunction "VDD_4") (pintype "power_in"))
      (node (ref "PD61") (pin "4") (pinfunction "VDD_4") (pintype "power_in"))
      (node (ref "PD62") (pin "4") (pinfunction "VDD_4") (pintype "power_in"))
      (node (ref "PD63") (pin "4") (pinfunction "VDD_4") (pintype "power_in"))
      (node (ref "PD64") (pin "4") (pinfunction "VDD_4") (pintype "power_in"))
      (node (ref "PD65") (pin "4") (pinfunction "VDD_4") (pintype "power_in"))
      (node (ref "PD66") (pin "4") (pinfunction "VDD_4") (pintype "power_in"))
      (node (ref "PD67") (pin "4") (pinfunction "VDD_4") (pintype "power_in"))
      (node (ref "PD68") (pin "4") (pinfunction "VDD_4") (pintype "power_in"))
      (node (ref "PD69") (pin "4") (pinfunction "VDD_4") (pintype "power_in"))
      (node (ref "PD7") (pin "1") (pinfunction "VDD_1") (pintype "power_in"))
      (node (ref "PD70") (pin "4") (pinfunction "VDD_4") (pintype "power_in"))
      (node (ref "PD71") (pin "4") (pinfunction "VDD_4") (pintype "power_in"))
      (node (ref "PD72") (pin "4") (pinfunction "VDD_4") (pintype "power_in"))
      (node (ref "PD73") (pin "4") (pinfunction "VDD_4") (pintype "power_in"))
      (node (ref "PD74") (pin "4") (pinfunction "VDD_4") (pintype "power_in"))
      (node (ref "PD75") (pin "4") (pinfunction "VDD_4") (pintype "power_in"))
      (node (ref "PD76") (pin "4") (pinfunction "VDD_4") (pintype "power_in"))
      (node (ref "PD77") (pin "4") (pinfunction "VDD_4") (pintype "power_in"))
      (node (ref "PD78") (pin "4") (pinfunction "VDD_4") (pintype "power_in"))
      (node (ref "PD79") (pin "4") (pinfunction "VDD_4") (pintype "power_in"))
      (node (ref "PD8") (pin "1") (pinfunction "VDD_1") (pintype "power_in"))
      (node (ref "PD80") (pin "4") (pinfunction "VDD_4") (pintype "power_in"))
      (node (ref "PD81") (pin "4") (pinfunction "VDD_4") (pintype "power_in"))
      (node (ref "PD82") (pin "4") (pinfunction "VDD_4") (pintype "power_in"))
      (node (ref "PD83") (pin "4") (pinfunction "VDD_4") (pintype "power_in"))
      (node (ref "PD84") (pin "4") (pinfunction "VDD_4") (pintype "power_in"))
      (node (ref "PD85") (pin "4") (pinfunction "VDD_4") (pintype "power_in"))
      (node (ref "PD86") (pin "4") (pinfunction "VDD_4") (pintype "power_in"))
      (node (ref "PD87") (pin "4") (pinfunction "VDD_4") (pintype "power_in"))
      (node (ref "PD88") (pin "4") (pinfunction "VDD_4") (pintype "power_in"))
      (node (ref "PD89") (pin "4") (pinfunction "VDD_4") (pintype "power_in"))
      (node (ref "PD9") (pin "1") (pinfunction "VDD_1") (pintype "power_in"))
      (node (ref "PD90") (pin "4") (pinfunction "VDD_4") (pintype "power_in"))
      (node (ref "PD91") (pin "4") (pinfunction "VDD_4") (pintype "power_in"))
      (node (ref "PD92") (pin "4") (pinfunction "VDD_4") (pintype "power_in"))
      (node (ref "PD93") (pin "4") (pinfunction "VDD_4") (pintype "power_in"))
      (node (ref "PD94") (pin "4") (pinfunction "VDD_4") (pintype "power_in"))
      (node (ref "PD95") (pin "4") (pinfunction "VDD_4") (pintype "power_in"))
      (node (ref "PD96") (pin "4") (pinfunction "VDD_4") (pintype "power_in"))
      (node (ref "PD97") (pin "4") (pinfunction "VDD_4") (pintype "power_in"))
      (node (ref "PD98") (pin "4") (pinfunction "VDD_4") (pintype "power_in"))
      (node (ref "PD99") (pin "4") (pinfunction "VDD_4") (pintype "power_in"))
      (node (ref "R12") (pin "2") (pinfunction "2_2") (pintype "passive"))
      (node (ref "R13") (pin "2") (pinfunction "2_2") (pintype "passive"))
      (node (ref "R15") (pin "2") (pinfunction "2_2") (pintype "passive"))
      (node (ref "R16") (pin "2") (pinfunction "2_2") (pintype "passive"))
      (node (ref "R18") (pin "2") (pinfunction "2_2") (pintype "passive"))
      (node (ref "R19") (pin "2") (pinfunction "2_2") (pintype "passive"))
      (node (ref "R21") (pin "2") (pinfunction "2_2") (pintype "passive"))
      (node (ref "R22") (pin "2") (pinfunction "2_2") (pintype "passive"))
      (node (ref "R24") (pin "2") (pinfunction "2_2") (pintype "passive"))
      (node (ref "R25") (pin "2") (pinfunction "2_2") (pintype "passive"))
      (node (ref "R27") (pin "2") (pinfunction "2_2") (pintype "passive"))
      (node (ref "R28") (pin "2") (pinfunction "2_2") (pintype "passive"))
      (node (ref "R31") (pin "2") (pinfunction "2_2") (pintype "passive"))
      (node (ref "R32") (pin "2") (pinfunction "2_2") (pintype "passive"))
      (node (ref "TP2") (pin "TP") (pinfunction "TP_TP") (pintype "input"))
      (node (ref "U5") (pin "3") (pinfunction "VOUT_3") (pintype "output"))
      (node (ref "V1") (pin "2") (pinfunction "+VIN_2") (pintype "passive"))
    )
    (net (code "3") (name "+12V") (class "Default")
      (node (ref "DISPLAY1") (pin "32") (pinfunction "VCC_32") (pintype "bidirectional"))
      (node (ref "L10") (pin "1") (pinfunction "1_1") (pintype "passive"))
      (node (ref "SJ1") (pin "2") (pinfunction "2_2") (pintype "passive"))
    )
    (net (code "4") (name "BL_PWM_1") (class "Default")
      (node (ref "R11") (pin "1") (pinfunction "1_1") (pintype "passive"))
      (node (ref "R8") (pin "1") (pinfunction "1_1") (pintype "passive"))
      (node (ref "U3") (pin "22") (pinfunction "PA6_22") (pintype "bidirectional"))
    )
    (net (code "5") (name "BL_PWM_2") (class "Default")
      (node (ref "R10") (pin "1") (pinfunction "1_1") (pintype "passive"))
      (node (ref "R7") (pin "1") (pinfunction "1_1") (pintype "passive"))
      (node (ref "U3") (pin "23") (pinfunction "PA7_23") (pintype "power_in"))
    )
    (net (code "6") (name "BL_PWM_3") (class "Default")
      (node (ref "R6") (pin "1") (pinfunction "1_1") (pintype "passive"))
      (node (ref "R9") (pin "1") (pinfunction "1_1") (pintype "passive"))
      (node (ref "U3") (pin "26") (pinfunction "PB0_26") (pintype "bidirectional"))
    )
    (net (code "7") (name "CAN_H") (class "Default")
      (node (ref "D1") (pin "1") (pinfunction "1_1") (pintype "passive"))
      (node (ref "R4") (pin "2") (pinfunction "2_2") (pintype "passive"))
      (node (ref "U1") (pin "7") (pinfunction "CANH_7") (pintype "bidirectional"))
      (node (ref "X1") (pin "P$1") (pinfunction "1_P$1") (pintype "passive"))
      (node (ref "X2") (pin "P$1") (pinfunction "1_P$1") (pintype "passive"))
    )
    (net (code "8") (name "CAN_L") (class "Default")
      (node (ref "D1") (pin "2") (pinfunction "2_2") (pintype "passive"))
      (node (ref "R3") (pin "2") (pinfunction "2_2") (pintype "passive"))
      (node (ref "U1") (pin "6") (pinfunction "CANL_6") (pintype "bidirectional"))
      (node (ref "X1") (pin "P$2") (pinfunction "2_P$2") (pintype "passive"))
      (node (ref "X2") (pin "P$2") (pinfunction "2_P$2") (pintype "passive"))
    )
    (net (code "9") (name "CAN_RXD") (class "Default")
      (node (ref "U1") (pin "4") (pinfunction "RXD_4") (pintype "bidirectional"))
      (node (ref "U3") (pin "44") (pinfunction "PA11_44") (pintype "bidirectional"))
    )
    (net (code "10") (name "CAN_TXD") (class "Default")
      (node (ref "U1") (pin "1") (pinfunction "TXD_1") (pintype "bidirectional"))
      (node (ref "U3") (pin "45") (pinfunction "PA12_45") (pintype "bidirectional"))
    )
    (net (code "11") (name "DATA_WS") (class "Default")
      (node (ref "R56") (pin "2") (pinfunction "2_2") (pintype "passive"))
      (node (ref "U6") (pin "14") (pinfunction "PB1_14") (pintype "bidirectional"))
      (node (ref "U7") (pin "3") (pinfunction "A_3") (pintype "input"))
    )
    (net (code "12") (name "DATA_WS_IN1") (class "Default")
      (node (ref "PD1") (pin "4") (pinfunction "DIN_4") (pintype "input"))
      (node (ref "R57") (pin "2") (pinfunction "2_2") (pintype "passive"))
      (node (ref "U7") (pin "4") (pinfunction "B_4") (pintype "output"))
    )
    (net (code "13") (name "DATA_WS_IN2") (class "Default")
      (node (ref "PD16") (pin "2") (pinfunction "DOUT_2") (pintype "output"))
      (node (ref "PD17") (pin "3") (pinfunction "DIN_3") (pintype "input"))
    )
    (net (code "14") (name "GND") (class "Default")
      (node (ref "C1") (pin "-") (pinfunction "-_-") (pintype "passive"))
      (node (ref "C10") (pin "1") (pinfunction "1_1") (pintype "passive"))
      (node (ref "C11") (pin "1") (pinfunction "1_1") (pintype "passive"))
      (node (ref "C12") (pin "1") (pinfunction "1_1") (pintype "passive"))
      (node (ref "C13") (pin "1") (pinfunction "1_1") (pintype "passive"))
      (node (ref "C14") (pin "1") (pinfunction "1_1") (pintype "passive"))
      (node (ref "C15") (pin "1") (pinfunction "1_1") (pintype "passive"))
      (node (ref "C16") (pin "1") (pinfunction "1_1") (pintype "passive"))
      (node (ref "C17") (pin "1") (pinfunction "1_1") (pintype "passive"))
      (node (ref "C18") (pin "2") (pinfunction "2_2") (pintype "passive"))
      (node (ref "C19") (pin "2") (pinfunction "2_2") (pintype "passive"))
      (node (ref "C2") (pin "1") (pinfunction "1_1") (pintype "passive"))
      (node (ref "C20") (pin "2") (pinfunction "2_2") (pintype "passive"))
      (node (ref "C21") (pin "2") (pinfunction "2_2") (pintype "passive"))
      (node (ref "C22") (pin "2") (pinfunction "2_2") (pintype "passive"))
      (node (ref "C23") (pin "-") (pinfunction "-_-") (pintype "passive"))
      (node (ref "C24") (pin "2") (pinfunction "2_2") (pintype "passive"))
      (node (ref "C25") (pin "1") (pinfunction "1_1") (pintype "passive"))
      (node (ref "C26") (pin "-") (pinfunction "-_-") (pintype "passive"))
      (node (ref "C27") (pin "-") (pinfunction "-_-") (pintype "passive"))
      (node (ref "C28") (pin "2") (pinfunction "2_2") (pintype "passive"))
      (node (ref "C29") (pin "1") (pinfunction "1_1") (pintype "passive"))
      (node (ref "C3") (pin "1") (pinfunction "1_1") (pintype "passive"))
      (node (ref "C30") (pin "1") (pinfunction "1_1") (pintype "passive"))
      (node (ref "C31") (pin "1") (pinfunction "1_1") (pintype "passive"))
      (node (ref "C32") (pin "-") (pinfunction "-_-") (pintype "passive"))
      (node (ref "C33") (pin "-") (pinfunction "-_-") (pintype "passive"))
      (node (ref "C34") (pin "-") (pinfunction "-_-") (pintype "passive"))
      (node (ref "C35") (pin "1") (pinfunction "1_1") (pintype "passive"))
      (node (ref "C36") (pin "1") (pinfunction "1_1") (pintype "passive"))
      (node (ref "C37") (pin "1") (pinfunction "1_1") (pintype "passive"))
      (node (ref "C38") (pin "-") (pinfunction "-_-") (pintype "passive"))
      (node (ref "C39") (pin "1") (pinfunction "1_1") (pintype "passive"))
      (node (ref "C4") (pin "-") (pinfunction "-_-") (pintype "passive"))
      (node (ref "C40") (pin "2") (pinfunction "2_2") (pintype "passive"))
      (node (ref "C41") (pin "2") (pinfunction "2_2") (pintype "passive"))
      (node (ref "C42") (pin "2") (pinfunction "2_2") (pintype "passive"))
      (node (ref "C43") (pin "-") (pinfunction "-_-") (pintype "passive"))
      (node (ref "C44") (pin "1") (pinfunction "1_1") (pintype "passive"))
      (node (ref "C45") (pin "1") (pinfunction "1_1") (pintype "passive"))
      (node (ref "C5") (pin "1") (pinfunction "1_1") (pintype "passive"))
      (node (ref "C6") (pin "2") (pinfunction "2_2") (pintype "passive"))
      (node (ref "C7") (pin "-") (pinfunction "-_-") (pintype "passive"))
      (node (ref "C8") (pin "2") (pinfunction "2_2") (pintype "passive"))
      (node (ref "C9") (pin "2") (pinfunction "2_2") (pintype "passive"))
      (node (ref "D1") (pin "3") (pinfunction "3_3") (pintype "passive"))
      (node (ref "D2") (pin "A") (pinfunction "A_A") (pintype "passive"))
      (node (ref "D6") (pin "A") (pinfunction "A_A") (pintype "passive"))
      (node (ref "DISPLAY1") (pin "10") (pinfunction "BS1_10") (pintype "bidirectional"))
      (node (ref "DISPLAY1") (pin "11") (pinfunction "BS2_11") (pintype "bidirectional"))
      (node (ref "DISPLAY1") (pin "13") (pinfunction "CS#_13") (pintype "bidirectional"))
      (node (ref "DISPLAY1") (pin "16") (pinfunction "R/W#(WR#)_16") (pintype "bidirectional"))
      (node (ref "DISPLAY1") (pin "17") (pinfunction "E(RD#)_17") (pintype "bidirectional"))
      (node (ref "DISPLAY1") (pin "20") (pinfunction "D2_20") (pintype "bidirectional"))
      (node (ref "DISPLAY1") (pin "21") (pinfunction "D3_21") (pintype "bidirectional"))
      (node (ref "DISPLAY1") (pin "22") (pinfunction "D4_22") (pintype "bidirectional"))
      (node (ref "DISPLAY1") (pin "23") (pinfunction "D5_23") (pintype "bidirectional"))
      (node (ref "DISPLAY1") (pin "24") (pinfunction "D6_24") (pintype "bidirectional"))
      (node (ref "DISPLAY1") (pin "25") (pinfunction "D7_25") (pintype "bidirectional"))
      (node (ref "DISPLAY1") (pin "3") (pinfunction "VSS_3") (pintype "bidirectional"))
      (node (ref "DISPLAY1") (pin "4") (pinfunction "REGVDD_4") (pintype "bidirectional"))
      (node (ref "DISPLAY1") (pin "9") (pinfunction "BS0_9") (pintype "bidirectional"))
      (node (ref "IC1") (pin "12") (pinfunction "GND_12") (pintype "bidirectional"))
      (node (ref "IC1") (pin "21") (pinfunction "A2_21") (pintype "bidirectional"))
      (node (ref "JP1") (pin "3") (pinfunction "3_3") (pintype "passive"))
      (node (ref "JP2") (pin "4") (pinfunction "4_4") (pintype "passive"))
      (node (ref "JP3") (pin "3") (pinfunction "3_3") (pintype "passive"))
      (node (ref "P2") (pin "1") (pinfunction "1_1") (pintype "passive"))
      (node (ref "P3") (pin "1") (pinfunction "1_1") (pintype "passive"))
      (node (ref "P4") (pin "1") (pinfunction "1_1") (pintype "passive"))
      (node (ref "PD1") (pin "3") (pinfunction "VSS_3") (pintype "power_in"))
      (node (ref "PD10") (pin "3") (pinfunction "VSS_3") (pintype "power_in"))
      (node (ref "PD100") (pin "2") (pinfunction "VSS_2") (pintype "power_in"))
      (node (ref "PD101") (pin "2") (pinfunction "VSS_2") (pintype "power_in"))
      (node (ref "PD102") (pin "2") (pinfunction "VSS_2") (pintype "power_in"))
      (node (ref "PD103") (pin "2") (pinfunction "VSS_2") (pintype "power_in"))
      (node (ref "PD104") (pin "2") (pinfunction "VSS_2") (pintype "power_in"))
      (node (ref "PD105") (pin "2") (pinfunction "VSS_2") (pintype "power_in"))
      (node (ref "PD106") (pin "2") (pinfunction "VSS_2") (pintype "power_in"))
      (node (ref "PD107") (pin "2") (pinfunction "VSS_2") (pintype "power_in"))
      (node (ref "PD108") (pin "2") (pinfunction "VSS_2") (pintype "power_in"))
      (node (ref "PD109") (pin "2") (pinfunction "VSS_2") (pintype "power_in"))
      (node (ref "PD11") (pin "3") (pinfunction "VSS_3") (pintype "power_in"))
      (node (ref "PD110") (pin "2") (pinfunction "VSS_2") (pintype "power_in"))
      (node (ref "PD12") (pin "3") (pinfunction "VSS_3") (pintype "power_in"))
      (node (ref "PD13") (pin "3") (pinfunction "VSS_3") (pintype "power_in"))
      (node (ref "PD14") (pin "3") (pinfunction "VSS_3") (pintype "power_in"))
      (node (ref "PD15") (pin "3") (pinfunction "VSS_3") (pintype "power_in"))
      (node (ref "PD16") (pin "3") (pinfunction "VSS_3") (pintype "power_in"))
      (node (ref "PD17") (pin "2") (pinfunction "VSS_2") (pintype "power_in"))
      (node (ref "PD18") (pin "2") (pinfunction "VSS_2") (pintype "power_in"))
      (node (ref "PD19") (pin "2") (pinfunction "VSS_2") (pintype "power_in"))
      (node (ref "PD2") (pin "3") (pinfunction "VSS_3") (pintype "power_in"))
      (node (ref "PD20") (pin "2") (pinfunction "VSS_2") (pintype "power_in"))
      (node (ref "PD21") (pin "2") (pinfunction "VSS_2") (pintype "power_in"))
      (node (ref "PD22") (pin "2") (pinfunction "VSS_2") (pintype "power_in"))
      (node (ref "PD23") (pin "2") (pinfunction "VSS_2") (pintype "power_in"))
      (node (ref "PD24") (pin "2") (pinfunction "VSS_2") (pintype "power_in"))
      (node (ref "PD25") (pin "2") (pinfunction "VSS_2") (pintype "power_in"))
      (node (ref "PD26") (pin "2") (pinfunction "VSS_2") (pintype "power_in"))
      (node (ref "PD27") (pin "2") (pinfunction "VSS_2") (pintype "power_in"))
      (node (ref "PD28") (pin "2") (pinfunction "VSS_2") (pintype "power_in"))
      (node (ref "PD29") (pin "2") (pinfunction "VSS_2") (pintype "power_in"))
      (node (ref "PD3") (pin "3") (pinfunction "VSS_3") (pintype "power_in"))
      (node (ref "PD30") (pin "2") (pinfunction "VSS_2") (pintype "power_in"))
      (node (ref "PD31") (pin "2") (pinfunction "VSS_2") (pintype "power_in"))
      (node (ref "PD32") (pin "2") (pinfunction "VSS_2") (pintype "power_in"))
      (node (ref "PD33") (pin "2") (pinfunction "VSS_2") (pintype "power_in"))
      (node (ref "PD34") (pin "2") (pinfunction "VSS_2") (pintype "power_in"))
      (node (ref "PD35") (pin "2") (pinfunction "VSS_2") (pintype "power_in"))
      (node (ref "PD36") (pin "2") (pinfunction "VSS_2") (pintype "power_in"))
      (node (ref "PD37") (pin "2") (pinfunction "VSS_2") (pintype "power_in"))
      (node (ref "PD38") (pin "2") (pinfunction "VSS_2") (pintype "power_in"))
      (node (ref "PD39") (pin "2") (pinfunction "VSS_2") (pintype "power_in"))
      (node (ref "PD4") (pin "3") (pinfunction "VSS_3") (pintype "power_in"))
      (node (ref "PD40") (pin "2") (pinfunction "VSS_2") (pintype "power_in"))
      (node (ref "PD41") (pin "2") (pinfunction "VSS_2") (pintype "power_in"))
      (node (ref "PD42") (pin "2") (pinfunction "VSS_2") (pintype "power_in"))
      (node (ref "PD43") (pin "2") (pinfunction "VSS_2") (pintype "power_in"))
      (node (ref "PD44") (pin "2") (pinfunction "VSS_2") (pintype "power_in"))
      (node (ref "PD45") (pin "2") (pinfunction "VSS_2") (pintype "power_in"))
      (node (ref "PD46") (pin "2") (pinfunction "VSS_2") (pintype "power_in"))
      (node (ref "PD47") (pin "2") (pinfunction "VSS_2") (pintype "power_in"))
      (node (ref "PD48") (pin "2") (pinfunction "VSS_2") (pintype "power_in"))
      (node (ref "PD49") (pin "2") (pinfunction "VSS_2") (pintype "power_in"))
      (node (ref "PD5") (pin "3") (pinfunction "VSS_3") (pintype "power_in"))
      (node (ref "PD50") (pin "2") (pinfunction "VSS_2") (pintype "power_in"))
      (node (ref "PD51") (pin "2") (pinfunction "VSS_2") (pintype "power_in"))
      (node (ref "PD52") (pin "2") (pinfunction "VSS_2") (pintype "power_in"))
      (node (ref "PD53") (pin "2") (pinfunction "VSS_2") (pintype "power_in"))
      (node (ref "PD54") (pin "2") (pinfunction "VSS_2") (pintype "power_in"))
      (node (ref "PD55") (pin "2") (pinfunction "VSS_2") (pintype "power_in"))
      (node (ref "PD56") (pin "2") (pinfunction "VSS_2") (pintype "power_in"))
      (node (ref "PD57") (pin "2") (pinfunction "VSS_2") (pintype "power_in"))
      (node (ref "PD58") (pin "2") (pinfunction "VSS_2") (pintype "power_in"))
      (node (ref "PD59") (pin "2") (pinfunction "VSS_2") (pintype "power_in"))
      (node (ref "PD6") (pin "3") (pinfunction "VSS_3") (pintype "power_in"))
      (node (ref "PD60") (pin "2") (pinfunction "VSS_2") (pintype "power_in"))
      (node (ref "PD61") (pin "2") (pinfunction "VSS_2") (pintype "power_in"))
      (node (ref "PD62") (pin "2") (pinfunction "VSS_2") (pintype "power_in"))
      (node (ref "PD63") (pin "2") (pinfunction "VSS_2") (pintype "power_in"))
      (node (ref "PD64") (pin "2") (pinfunction "VSS_2") (pintype "power_in"))
      (node (ref "PD65") (pin "2") (pinfunction "VSS_2") (pintype "power_in"))
      (node (ref "PD66") (pin "2") (pinfunction "VSS_2") (pintype "power_in"))
      (node (ref "PD67") (pin "2") (pinfunction "VSS_2") (pintype "power_in"))
      (node (ref "PD68") (pin "2") (pinfunction "VSS_2") (pintype "power_in"))
      (node (ref "PD69") (pin "2") (pinfunction "VSS_2") (pintype "power_in"))
      (node (ref "PD7") (pin "3") (pinfunction "VSS_3") (pintype "power_in"))
      (node (ref "PD70") (pin "2") (pinfunction "VSS_2") (pintype "power_in"))
      (node (ref "PD71") (pin "2") (pinfunction "VSS_2") (pintype "power_in"))
      (node (ref "PD72") (pin "2") (pinfunction "VSS_2") (pintype "power_in"))
      (node (ref "PD73") (pin "2") (pinfunction "VSS_2") (pintype "power_in"))
      (node (ref "PD74") (pin "2") (pinfunction "VSS_2") (pintype "power_in"))
      (node (ref "PD75") (pin "2") (pinfunction "VSS_2") (pintype "power_in"))
      (node (ref "PD76") (pin "2") (pinfunction "VSS_2") (pintype "power_in"))
      (node (ref "PD77") (pin "2") (pinfunction "VSS_2") (pintype "power_in"))
      (node (ref "PD78") (pin "2") (pinfunction "VSS_2") (pintype "power_in"))
      (node (ref "PD79") (pin "2") (pinfunction "VSS_2") (pintype "power_in"))
      (node (ref "PD8") (pin "3") (pinfunction "VSS_3") (pintype "power_in"))
      (node (ref "PD80") (pin "2") (pinfunction "VSS_2") (pintype "power_in"))
      (node (ref "PD81") (pin "2") (pinfunction "VSS_2") (pintype "power_in"))
      (node (ref "PD82") (pin "2") (pinfunction "VSS_2") (pintype "power_in"))
      (node (ref "PD83") (pin "2") (pinfunction "VSS_2") (pintype "power_in"))
      (node (ref "PD84") (pin "2") (pinfunction "VSS_2") (pintype "power_in"))
      (node (ref "PD85") (pin "2") (pinfunction "VSS_2") (pintype "power_in"))
      (node (ref "PD86") (pin "2") (pinfunction "VSS_2") (pintype "power_in"))
      (node (ref "PD87") (pin "2") (pinfunction "VSS_2") (pintype "power_in"))
      (node (ref "PD88") (pin "2") (pinfunction "VSS_2") (pintype "power_in"))
      (node (ref "PD89") (pin "2") (pinfunction "VSS_2") (pintype "power_in"))
      (node (ref "PD9") (pin "3") (pinfunction "VSS_3") (pintype "power_in"))
      (node (ref "PD90") (pin "2") (pinfunction "VSS_2") (pintype "power_in"))
      (node (ref "PD91") (pin "2") (pinfunction "VSS_2") (pintype "power_in"))
      (node (ref "PD92") (pin "2") (pinfunction "VSS_2") (pintype "power_in"))
      (node (ref "PD93") (pin "2") (pinfunction "VSS_2") (pintype "power_in"))
      (node (ref "PD94") (pin "2") (pinfunction "VSS_2") (pintype "power_in"))
      (node (ref "PD95") (pin "2") (pinfunction "VSS_2") (pintype "power_in"))
      (node (ref "PD96") (pin "2") (pinfunction "VSS_2") (pintype "power_in"))
      (node (ref "PD97") (pin "2") (pinfunction "VSS_2") (pintype "power_in"))
      (node (ref "PD98") (pin "2") (pinfunction "VSS_2") (pintype "power_in"))
      (node (ref "PD99") (pin "2") (pinfunction "VSS_2") (pintype "power_in"))
      (node (ref "R2") (pin "1") (pinfunction "1_1") (pintype "passive"))
      (node (ref "R49") (pin "2") (pinfunction "2_2") (pintype "passive"))
      (node (ref "R51") (pin "2") (pinfunction "2_2") (pintype "passive"))
      (node (ref "R52") (pin "2") (pinfunction "2_2") (pintype "passive"))
      (node (ref "R56") (pin "1") (pinfunction "1_1") (pintype "passive"))
      (node (ref "R57") (pin "1") (pinfunction "1_1") (pintype "passive"))
      (node (ref "R6") (pin "2") (pinfunction "2_2") (pintype "passive"))
      (node (ref "R68") (pin "2") (pinfunction "2_2") (pintype "passive"))
      (node (ref "R7") (pin "2") (pinfunction "2_2") (pintype "passive"))
      (node (ref "R71") (pin "1") (pinfunction "1_1") (pintype "passive"))
      (node (ref "R8") (pin "2") (pinfunction "2_2") (pintype "passive"))
      (node (ref "SJ2") (pin "1") (pinfunction "1_1") (pintype "passive"))
      (node (ref "SJ3") (pin "1") (pinfunction "1_1") (pintype "passive"))
      (node (ref "SJ4") (pin "3") (pinfunction "3_3") (pintype "passive"))
      (node (ref "SJ5") (pin "3") (pinfunction "3_3") (pintype "passive"))
      (node (ref "T1") (pin "E") (pinfunction "E_E") (pintype "passive"))
      (node (ref "T2") (pin "E") (pinfunction "E_E") (pintype "passive"))
      (node (ref "T3") (pin "E") (pinfunction "E_E") (pintype "passive"))
      (node (ref "TP4") (pin "TP") (pinfunction "TP_TP") (pintype "input"))
      (node (ref "U1") (pin "2") (pinfunction "GND_2") (pintype "bidirectional"))
      (node (ref "U10") (pin "1") (pinfunction "GND_1") (pintype "power_in"))
      (node (ref "U11") (pin "1") (pinfunction "GND_1") (pintype "power_in"))
      (node (ref "U2") (pin "GND_1") (pinfunction "GND_1_GND_1") (pintype "bidirectional"))
      (node (ref "U2") (pin "GND_2") (pinfunction "GND_2_GND_2") (pintype "bidirectional"))
      (node (ref "U3") (pin "12") (pinfunction "VSSA_12") (pintype "passive"))
      (node (ref "U3") (pin "18") (pinfunction "VSS_4_18") (pintype "passive"))
      (node (ref "U3") (pin "31") (pinfunction "VSS_1_31") (pintype "passive"))
      (node (ref "U3") (pin "47") (pinfunction "VSS_2_47") (pintype "passive"))
      (node (ref "U3") (pin "60") (pinfunction "BOOT0_60") (pintype "passive"))
      (node (ref "U3") (pin "63") (pinfunction "VSS_3_63") (pintype "passive"))
      (node (ref "U4") (pin "2") (pinfunction "GND_2") (pintype "power_in"))
      (node (ref "U5") (pin "2") (pinfunction "GND_2") (pintype "power_in"))
      (node (ref "U6") (pin "1") (pinfunction "BOOT0_1") (pintype "bidirectional"))
      (node (ref "U6") (pin "15") (pinfunction "VSS_15") (pintype "bidirectional"))
      (node (ref "U7") (pin "2") (pinfunction "GND_2") (pintype "passive"))
      (node (ref "U8") (pin "1") (pinfunction "A0_1") (pintype "input"))
      (node (ref "U8") (pin "2") (pinfunction "A1_2") (pintype "input"))
      (node (ref "U8") (pin "3") (pinfunction "A2_3") (pintype "input"))
      (node (ref "U8") (pin "4") (pinfunction "VSS_4") (pintype "passive"))
      (node (ref "U8") (pin "7") (pinfunction "WP_7") (pintype "input"))
      (node (ref "U9") (pin "1") (pinfunction "GND_1") (pintype "power_in"))
      (node (ref "V1") (pin "1") (pinfunction "-VIN_1") (pintype "passive"))
      (node (ref "V1") (pin "3") (pinfunction "-VOUT_3") (pintype "passive"))
      (node (ref "X3") (pin "P$2") (pinfunction "2_P$2") (pintype "passive"))
      (node (ref "X4") (pin "P$2") (pinfunction "2_P$2") (pintype "passive"))
      (node (ref "X5") (pin "11") (pinfunction "S_11") (pintype "passive"))
      (node (ref "X5") (pin "12") (pinfunction "S_12") (pintype "passive"))
      (node (ref "X5") (pin "14") (pinfunction "S_14") (pintype "passive"))
      (node (ref "X5") (pin "17") (pinfunction "S_17") (pintype "passive"))
      (node (ref "X5") (pin "18") (pinfunction "S_18") (pintype "passive"))
      (node (ref "X5") (pin "2") (pinfunction "S_2") (pintype "passive"))
    )
    (net (code "15") (name "I2C_1_SCL") (class "Default")
      (node (ref "IC1") (pin "22") (pinfunction "SCL_22") (pintype "bidirectional"))
      (node (ref "R67") (pin "1") (pinfunction "1_1") (pintype "passive"))
      (node (ref "U3") (pin "58") (pinfunction "PB6_58") (pintype "bidirectional"))
    )
    (net (code "16") (name "I2C_1_SDA") (class "Default")
      (node (ref "IC1") (pin "23") (pinfunction "SDA_23") (pintype "bidirectional"))
      (node (ref "R66") (pin "1") (pinfunction "1_1") (pintype "passive"))
      (node (ref "U3") (pin "59") (pinfunction "PB7_59") (pintype "power_in"))
    )
    (net (code "17") (name "I2C_2_SCL") (class "Default")
      (node (ref "U3") (pin "29") (pinfunction "PB10_29") (pintype "bidirectional"))
    )
    (net (code "18") (name "I2C_2_SDA") (class "Default")
      (node (ref "U3") (pin "30") (pinfunction "PB11_30") (pintype "bidirectional"))
    )
    (net (code "19") (name "I2C_MUX_0") (class "Default")
      (node (ref "IC1") (pin "1") (pinfunction "A0_1") (pintype "bidirectional"))
      (node (ref "U3") (pin "62") (pinfunction "PB9_62") (pintype "bidirectional"))
    )
    (net (code "20") (name "I2C_MUX_1") (class "Default")
      (node (ref "IC1") (pin "2") (pinfunction "A1_2") (pintype "bidirectional"))
      (node (ref "U3") (pin "61") (pinfunction "PB8_61") (pintype "bidirectional"))
    )
    (net (code "21") (name "I2C_RESET") (class "Default")
      (node (ref "IC1") (pin "3") (pinfunction "RESET_3") (pintype "bidirectional"))
      (node (ref "R65") (pin "1") (pinfunction "1_1") (pintype "passive"))
      (node (ref "U3") (pin "50") (pinfunction "PA15_50") (pintype "bidirectional"))
    )
    (net (code "22") (name "IREF") (class "Default")
      (node (ref "R70") (pin "2") (pinfunction "2_2") (pintype "passive"))
      (node (ref "X5") (pin "27") (pinfunction "S_27") (pintype "passive"))
    )
    (net (code "23") (name "MCU1_NRST") (class "Default")
      (node (ref "C10") (pin "2") (pinfunction "2_2") (pintype "passive"))
      (node (ref "JP1") (pin "5") (pinfunction "5_5") (pintype "passive"))
      (node (ref "U3") (pin "7") (pinfunction "NRST_7") (pintype "output"))
    )
    (net (code "24") (name "MCU_2_RX") (class "Default")
      (node (ref "U3") (pin "42") (pinfunction "PA9_42") (pintype "bidirectional"))
      (node (ref "U6") (pin "9") (pinfunction "PA3_9") (pintype "bidirectional"))
    )
    (net (code "25") (name "MCU_2_TX") (class "Default")
      (node (ref "U3") (pin "43") (pinfunction "PA10_43") (pintype "bidirectional"))
      (node (ref "U6") (pin "8") (pinfunction "PA2_8") (pintype "bidirectional"))
    )
    (net (code "26") (name "N$177") (class "Default")
      (node (ref "R49") (pin "1") (pinfunction "1_1") (pintype "passive"))
      (node (ref "R50") (pin "2") (pinfunction "2_2") (pintype "passive"))
      (node (ref "X3") (pin "P$1") (pinfunction "1_P$1") (pintype "passive"))
      (node (ref "X4") (pin "P$1") (pinfunction "1_P$1") (pintype "passive"))
    )
    (net (code "27") (name "Net-(C3-Pad2)") (class "Default")
      (node (ref "C3") (pin "2") (pinfunction "2_2") (pintype "passive"))
      (node (ref "C4") (pin "+") (pinfunction "+_+") (pintype "passive"))
      (node (ref "L2") (pin "1") (pinfunction "1_1") (pintype "passive"))
      (node (ref "U2") (pin "VCC") (pinfunction "VCC_VCC") (pintype "bidirectional"))
    )
    (net (code "28") (name "Net-(C6-Pad1)") (class "Default")
      (node (ref "C6") (pin "1") (pinfunction "1_1") (pintype "passive"))
      (node (ref "R3") (pin "1") (pinfunction "1_1") (pintype "passive"))
      (node (ref "R4") (pin "1") (pinfunction "1_1") (pintype "passive"))
    )
    (net (code "29") (name "Net-(C12-Pad2)") (class "Default")
      (node (ref "C12") (pin "2") (pinfunction "2_2") (pintype "passive"))
      (node (ref "Q1") (pin "2") (pinfunction "2_2") (pintype "passive"))
      (node (ref "R5") (pin "1") (pinfunction "1_1") (pintype "passive"))
    )
    (net (code "30") (name "Net-(C24-Pad1)") (class "Default")
      (node (ref "C24") (pin "1") (pinfunction "1_1") (pintype "passive"))
      (node (ref "C26") (pin "+") (pinfunction "+_+") (pintype "passive"))
      (node (ref "D3") (pin "C") (pinfunction "C_C") (pintype "passive"))
      (node (ref "L4") (pin "1") (pinfunction "1_1") (pintype "passive"))
    )
    (net (code "31") (name "Net-(C34-Pad+)") (class "Default")
      (node (ref "C34") (pin "+") (pinfunction "+_+") (pintype "passive"))
      (node (ref "D5") (pin "C") (pinfunction "C_C") (pintype "passive"))
      (node (ref "D6") (pin "C") (pinfunction "C_C") (pintype "passive"))
      (node (ref "R52") (pin "1") (pinfunction "1_1") (pintype "passive"))
      (node (ref "SJ1") (pin "1") (pinfunction "1_1") (pintype "passive"))
      (node (ref "TP3") (pin "TP") (pinfunction "TP_TP") (pintype "input"))
    )
    (net (code "32") (name "Net-(D2-PadC)") (class "Default")
      (node (ref "D2") (pin "C") (pinfunction "C_C") (pintype "passive"))
      (node (ref "D3") (pin "A") (pinfunction "A_A") (pintype "passive"))
      (node (ref "R50") (pin "1") (pinfunction "1_1") (pintype "passive"))
      (node (ref "R51") (pin "1") (pinfunction "1_1") (pintype "passive"))
    )
    (net (code "33") (name "Net-(D4-PadC)") (class "Default")
      (node (ref "D4") (pin "C") (pinfunction "C_C") (pintype "passive"))
      (node (ref "D5") (pin "A") (pinfunction "A_A") (pintype "passive"))
    )
    (net (code "34") (name "Net-(DISPLAY1-IREF)") (class "Default")
      (node (ref "DISPLAY1") (pin "26") (pinfunction "IREF_26") (pintype "bidirectional"))
      (node (ref "R69") (pin "1") (pinfunction "1_1") (pintype "passive"))
    )
    (net (code "35") (name "Net-(DISPLAY1-OPR0)") (class "Default")
      (node (ref "DISPLAY1") (pin "29") (pinfunction "OPR0_29") (pintype "bidirectional"))
      (node (ref "SJ4") (pin "2") (pinfunction "2_2") (pintype "passive"))
    )
    (net (code "36") (name "Net-(DISPLAY1-OPR1)") (class "Default")
      (node (ref "DISPLAY1") (pin "30") (pinfunction "OPR1_30") (pintype "bidirectional"))
      (node (ref "SJ5") (pin "2") (pinfunction "2_2") (pintype "passive"))
    )
    (net (code "37") (name "Net-(DISPLAY1-ROM0)") (class "Default")
      (node (ref "DISPLAY1") (pin "27") (pinfunction "ROM0_27") (pintype "bidirectional"))
      (node (ref "SJ3") (pin "2") (pinfunction "2_2") (pintype "passive"))
    )
    (net (code "38") (name "Net-(DISPLAY1-ROM1)") (class "Default")
      (node (ref "DISPLAY1") (pin "28") (pinfunction "ROM1_28") (pintype "bidirectional"))
      (node (ref "SJ2") (pin "2") (pinfunction "2_2") (pintype "passive"))
    )
    (net (code "39") (name "Net-(DISPLAY1-VCOMH)") (class "Default")
      (node (ref "C44") (pin "2") (pinfunction "2_2") (pintype "passive"))
      (node (ref "DISPLAY1") (pin "31") (pinfunction "VCOMH_31") (pintype "bidirectional"))
    )
    (net (code "40") (name "Net-(L8-Pad2)") (class "Default")
      (node (ref "L8") (pin "2") (pinfunction "2_2") (pintype "passive"))
      (node (ref "SJ2") (pin "3") (pinfunction "3_3") (pintype "passive"))
      (node (ref "SJ3") (pin "3") (pinfunction "3_3") (pintype "passive"))
      (node (ref "SJ4") (pin "1") (pinfunction "1_1") (pintype "passive"))
      (node (ref "SJ5") (pin "1") (pinfunction "1_1") (pintype "passive"))
    )
    (net (code "41") (name "Net-(L9-Pad2)") (class "Default")
      (node (ref "L9") (pin "2") (pinfunction "2_2") (pintype "passive"))
      (node (ref "V2") (pin "A") (pinfunction "A_A") (pintype "passive"))
    )
    (net (code "42") (name "Net-(LED1-PadA)") (class "Default")
      (node (ref "LED1") (pin "A") (pinfunction "A_A") (pintype "passive"))
      (node (ref "R12") (pin "1") (pinfunction "1_1") (pintype "passive"))
    )
    (net (code "43") (name "Net-(LED1-PadC)") (class "Default")
      (node (ref "LED1") (pin "C") (pinfunction "C_C") (pintype "passive"))
      (node (ref "LED10") (pin "C") (pinfunction "C_C") (pintype "passive"))
      (node (ref "LED13") (pin "C") (pinfunction "C_C") (pintype "passive"))
      (node (ref "LED16") (pin "C") (pinfunction "C_C") (pintype "passive"))
      (node (ref "LED21") (pin "C") (pinfunction "C_C") (pintype "passive"))
      (node (ref "LED4") (pin "C") (pinfunction "C_C") (pintype "passive"))
      (node (ref "LED7") (pin "C") (pinfunction "C_C") (pintype "passive"))
      (node (ref "T1") (pin "C") (pinfunction "C_C") (pintype "passive"))
    )
    (net (code "44") (name "Net-(LED2-PadA)") (class "Default")
      (node (ref "LED2") (pin "A") (pinfunction "A_A") (pintype "passive"))
      (node (ref "R13") (pin "1") (pinfunction "1_1") (pintype "passive"))
    )
    (net (code "45") (name "Net-(LED3-PadA)") (class "Default")
      (node (ref "LED3") (pin "A") (pinfunction "A_A") (pintype "passive"))
      (node (ref "R14") (pin "1") (pinfunction "1_1") (pintype "passive"))
    )
    (net (code "46") (name "Net-(LED4-PadA)") (class "Default")
      (node (ref "LED4") (pin "A") (pinfunction "A_A") (pintype "passive"))
      (node (ref "R15") (pin "1") (pinfunction "1_1") (pintype "passive"))
    )
    (net (code "47") (name "Net-(LED5-PadA)") (class "Default")
      (node (ref "LED5") (pin "A") (pinfunction "A_A") (pintype "passive"))
      (node (ref "R16") (pin "1") (pinfunction "1_1") (pintype "passive"))
    )
    (net (code "48") (name "Net-(LED6-PadA)") (class "Default")
      (node (ref "LED6") (pin "A") (pinfunction "A_A") (pintype "passive"))
      (node (ref "R17") (pin "1") (pinfunction "1_1") (pintype "passive"))
    )
    (net (code "49") (name "Net-(LED7-PadA)") (class "Default")
      (node (ref "LED7") (pin "A") (pinfunction "A_A") (pintype "passive"))
      (node (ref "R18") (pin "1") (pinfunction "1_1") (pintype "passive"))
    )
    (net (code "50") (name "Net-(LED8-PadA)") (class "Default")
      (node (ref "LED8") (pin "A") (pinfunction "A_A") (pintype "passive"))
      (node (ref "R19") (pin "1") (pinfunction "1_1") (pintype "passive"))
    )
    (net (code "51") (name "Net-(LED9-PadA)") (class "Default")
      (node (ref "LED9") (pin "A") (pinfunction "A_A") (pintype "passive"))
      (node (ref "R20") (pin "1") (pinfunction "1_1") (pintype "passive"))
    )
    (net (code "52") (name "Net-(LED10-PadA)") (class "Default")
      (node (ref "LED10") (pin "A") (pinfunction "A_A") (pintype "passive"))
      (node (ref "R21") (pin "1") (pinfunction "1_1") (pintype "passive"))
    )
    (net (code "53") (name "Net-(LED11-PadA)") (class "Default")
      (node (ref "LED11") (pin "A") (pinfunction "A_A") (pintype "passive"))
      (node (ref "R22") (pin "1") (pinfunction "1_1") (pintype "passive"))
    )
    (net (code "54") (name "Net-(LED11-PadC)") (class "Default")
      (node (ref "LED11") (pin "C") (pinfunction "C_C") (pintype "passive"))
      (node (ref "LED14") (pin "C") (pinfunction "C_C") (pintype "passive"))
      (node (ref "LED17") (pin "C") (pinfunction "C_C") (pintype "passive"))
      (node (ref "LED2") (pin "C") (pinfunction "C_C") (pintype "passive"))
      (node (ref "LED20") (pin "C") (pinfunction "C_C") (pintype "passive"))
      (node (ref "LED5") (pin "C") (pinfunction "C_C") (pintype "passive"))
      (node (ref "LED8") (pin "C") (pinfunction "C_C") (pintype "passive"))
      (node (ref "T2") (pin "C") (pinfunction "C_C") (pintype "passive"))
    )
    (net (code "55") (name "Net-(LED12-PadA)") (class "Default")
      (node (ref "LED12") (pin "A") (pinfunction "A_A") (pintype "passive"))
      (node (ref "R23") (pin "1") (pinfunction "1_1") (pintype "passive"))
    )
    (net (code "56") (name "Net-(LED12-PadC)") (class "Default")
      (node (ref "LED12") (pin "C") (pinfunction "C_C") (pintype "passive"))
      (node (ref "LED15") (pin "C") (pinfunction "C_C") (pintype "passive"))
      (node (ref "LED18") (pin "C") (pinfunction "C_C") (pintype "passive"))
      (node (ref "LED19") (pin "C") (pinfunction "C_C") (pintype "passive"))
      (node (ref "LED22") (pin "C") (pinfunction "C_C") (pintype "passive"))
      (node (ref "LED23") (pin "C") (pinfunction "C_C") (pintype "passive"))
      (node (ref "LED24") (pin "C") (pinfunction "C_C") (pintype "passive"))
      (node (ref "LED25") (pin "C") (pinfunction "C_C") (pintype "passive"))
      (node (ref "LED26") (pin "C") (pinfunction "C_C") (pintype "passive"))
      (node (ref "LED27") (pin "C") (pinfunction "C_C") (pintype "passive"))
      (node (ref "LED28") (pin "C") (pinfunction "C_C") (pintype "passive"))
      (node (ref "LED29") (pin "C") (pinfunction "C_C") (pintype "passive"))
      (node (ref "LED3") (pin "C") (pinfunction "C_C") (pintype "passive"))
      (node (ref "LED30") (pin "C") (pinfunction "C_C") (pintype "passive"))
      (node (ref "LED31") (pin "C") (pinfunction "C_C") (pintype "passive"))
      (node (ref "LED32") (pin "C") (pinfunction "C_C") (pintype "passive"))
      (node (ref "LED33") (pin "C") (pinfunction "C_C") (pintype "passive"))
      (node (ref "LED34") (pin "C") (pinfunction "C_C") (pintype "passive"))
      (node (ref "LED35") (pin "C") (pinfunction "C_C") (pintype "passive"))
      (node (ref "LED36") (pin "C") (pinfunction "C_C") (pintype "passive"))
      (node (ref "LED37") (pin "C") (pinfunction "C_C") (pintype "passive"))
      (node (ref "LED6") (pin "C") (pinfunction "C_C") (pintype "passive"))
      (node (ref "LED9") (pin "C") (pinfunction "C_C") (pintype "passive"))
      (node (ref "T3") (pin "C") (pinfunction "C_C") (pintype "passive"))
    )
    (net (code "57") (name "Net-(LED13-PadA)") (class "Default")
      (node (ref "LED13") (pin "A") (pinfunction "A_A") (pintype "passive"))
      (node (ref "R24") (pin "1") (pinfunction "1_1") (pintype "passive"))
    )
    (net (code "58") (name "Net-(LED14-PadA)") (class "Default")
      (node (ref "LED14") (pin "A") (pinfunction "A_A") (pintype "passive"))
      (node (ref "R25") (pin "1") (pinfunction "1_1") (pintype "passive"))
    )
    (net (code "59") (name "Net-(LED15-PadA)") (class "Default")
      (node (ref "LED15") (pin "A") (pinfunction "A_A") (pintype "passive"))
      (node (ref "R26") (pin "1") (pinfunction "1_1") (pintype "passive"))
    )
    (net (code "60") (name "Net-(LED16-PadA)") (class "Default")
      (node (ref "LED16") (pin "A") (pinfunction "A_A") (pintype "passive"))
      (node (ref "R27") (pin "1") (pinfunction "1_1") (pintype "passive"))
    )
    (net (code "61") (name "Net-(LED17-PadA)") (class "Default")
      (node (ref "LED17") (pin "A") (pinfunction "A_A") (pintype "passive"))
      (node (ref "R28") (pin "1") (pinfunction "1_1") (pintype "passive"))
    )
    (net (code "62") (name "Net-(LED18-PadA)") (class "Default")
      (node (ref "LED18") (pin "A") (pinfunction "A_A") (pintype "passive"))
      (node (ref "R29") (pin "1") (pinfunction "1_1") (pintype "passive"))
    )
    (net (code "63") (name "Net-(LED19-PadA)") (class "Default")
      (node (ref "LED19") (pin "A") (pinfunction "A_A") (pintype "passive"))
      (node (ref "R30") (pin "1") (pinfunction "1_1") (pintype "passive"))
    )
    (net (code "64") (name "Net-(LED20-PadA)") (class "Default")
      (node (ref "LED20") (pin "A") (pinfunction "A_A") (pintype "passive"))
      (node (ref "R31") (pin "1") (pinfunction "1_1") (pintype "passive"))
    )
    (net (code "65") (name "Net-(LED21-PadA)") (class "Default")
      (node (ref "LED21") (pin "A") (pinfunction "A_A") (pintype "passive"))
      (node (ref "R32") (pin "1") (pinfunction "1_1") (pintype "passive"))
    )
    (net (code "66") (name "Net-(LED22-PadA)") (class "Default")
      (node (ref "LED22") (pin "A") (pinfunction "A_A") (pintype "passive"))
      (node (ref "R33") (pin "1") (pinfunction "1_1") (pintype "passive"))
    )
    (net (code "67") (name "Net-(LED23-PadA)") (class "Default")
      (node (ref "LED23") (pin "A") (pinfunction "A_A") (pintype "passive"))
      (node (ref "R34") (pin "1") (pinfunction "1_1") (pintype "passive"))
    )
    (net (code "68") (name "Net-(LED24-PadA)") (class "Default")
      (node (ref "LED24") (pin "A") (pinfunction "A_A") (pintype "passive"))
      (node (ref "R35") (pin "1") (pinfunction "1_1") (pintype "passive"))
    )
    (net (code "69") (name "Net-(LED25-PadA)") (class "Default")
      (node (ref "LED25") (pin "A") (pinfunction "A_A") (pintype "passive"))
      (node (ref "R36") (pin "1") (pinfunction "1_1") (pintype "passive"))
    )
    (net (code "70") (name "Net-(LED26-PadA)") (class "Default")
      (node (ref "LED26") (pin "A") (pinfunction "A_A") (pintype "passive"))
      (node (ref "R37") (pin "1") (pinfunction "1_1") (pintype "passive"))
    )
    (net (code "71") (name "Net-(LED27-PadA)") (class "Default")
      (node (ref "LED27") (pin "A") (pinfunction "A_A") (pintype "passive"))
      (node (ref "R38") (pin "1") (pinfunction "1_1") (pintype "passive"))
    )
    (net (code "72") (name "Net-(LED28-PadA)") (class "Default")
      (node (ref "LED28") (pin "A") (pinfunction "A_A") (pintype "passive"))
      (node (ref "R39") (pin "1") (pinfunction "1_1") (pintype "passive"))
    )
    (net (code "73") (name "Net-(LED29-PadA)") (class "Default")
      (node (ref "LED29") (pin "A") (pinfunction "A_A") (pintype "passive"))
      (node (ref "R40") (pin "1") (pinfunction "1_1") (pintype "passive"))
    )
    (net (code "74") (name "Net-(LED30-PadA)") (class "Default")
      (node (ref "LED30") (pin "A") (pinfunction "A_A") (pintype "passive"))
      (node (ref "R41") (pin "1") (pinfunction "1_1") (pintype "passive"))
    )
    (net (code "75") (name "Net-(LED31-PadA)") (class "Default")
      (node (ref "LED31") (pin "A") (pinfunction "A_A") (pintype "passive"))
      (node (ref "R42") (pin "1") (pinfunction "1_1") (pintype "passive"))
    )
    (net (code "76") (name "Net-(LED32-PadA)") (class "Default")
      (node (ref "LED32") (pin "A") (pinfunction "A_A") (pintype "passive"))
      (node (ref "R43") (pin "1") (pinfunction "1_1") (pintype "passive"))
    )
    (net (code "77") (name "Net-(LED33-PadA)") (class "Default")
      (node (ref "LED33") (pin "A") (pinfunction "A_A") (pintype "passive"))
      (node (ref "R44") (pin "1") (pinfunction "1_1") (pintype "passive"))
    )
    (net (code "78") (name "Net-(LED34-PadA)") (class "Default")
      (node (ref "LED34") (pin "A") (pinfunction "A_A") (pintype "passive"))
      (node (ref "R45") (pin "1") (pinfunction "1_1") (pintype "passive"))
    )
    (net (code "79") (name "Net-(LED35-PadA)") (class "Default")
      (node (ref "LED35") (pin "A") (pinfunction "A_A") (pintype "passive"))
      (node (ref "R46") (pin "1") (pinfunction "1_1") (pintype "passive"))
    )
    (net (code "80") (name "Net-(LED36-PadA)") (class "Default")
      (node (ref "LED36") (pin "A") (pinfunction "A_A") (pintype "passive"))
      (node (ref "R47") (pin "1") (pinfunction "1_1") (pintype "passive"))
    )
    (net (code "81") (name "Net-(LED37-PadA)") (class "Default")
      (node (ref "LED37") (pin "A") (pinfunction "A_A") (pintype "passive"))
      (node (ref "R48") (pin "1") (pinfunction "1_1") (pintype "passive"))
    )
    (net (code "82") (name "Net-(PD1-DOUT)") (class "Default")
      (node (ref "PD1") (pin "2") (pinfunction "DOUT_2") (pintype "output"))
      (node (ref "PD2") (pin "4") (pinfunction "DIN_4") (pintype "input"))
    )
    (net (code "83") (name "Net-(PD2-DOUT)") (class "Default")
      (node (ref "PD2") (pin "2") (pinfunction "DOUT_2") (pintype "output"))
      (node (ref "PD3") (pin "4") (pinfunction "DIN_4") (pintype "input"))
    )
    (net (code "84") (name "Net-(PD3-DOUT)") (class "Default")
      (node (ref "PD3") (pin "2") (pinfunction "DOUT_2") (pintype "output"))
      (node (ref "PD4") (pin "4") (pinfunction "DIN_4") (pintype "input"))
    )
    (net (code "85") (name "Net-(PD4-DOUT)") (class "Default")
      (node (ref "PD4") (pin "2") (pinfunction "DOUT_2") (pintype "output"))
      (node (ref "PD5") (pin "4") (pinfunction "DIN_4") (pintype "input"))
    )
    (net (code "86") (name "Net-(PD5-DOUT)") (class "Default")
      (node (ref "PD5") (pin "2") (pinfunction "DOUT_2") (pintype "output"))
      (node (ref "PD6") (pin "4") (pinfunction "DIN_4") (pintype "input"))
    )
    (net (code "87") (name "Net-(PD6-DOUT)") (class "Default")
      (node (ref "PD6") (pin "2") (pinfunction "DOUT_2") (pintype "output"))
      (node (ref "PD7") (pin "4") (pinfunction "DIN_4") (pintype "input"))
    )
    (net (code "88") (name "Net-(PD7-DOUT)") (class "Default")
      (node (ref "PD7") (pin "2") (pinfunction "DOUT_2") (pintype "output"))
      (node (ref "PD8") (pin "4") (pinfunction "DIN_4") (pintype "input"))
    )
    (net (code "89") (name "Net-(PD8-DOUT)") (class "Default")
      (node (ref "PD8") (pin "2") (pinfunction "DOUT_2") (pintype "output"))
      (node (ref "PD9") (pin "4") (pinfunction "DIN_4") (pintype "input"))
    )
    (net (code "90") (name "Net-(PD10-DIN)") (class "Default")
      (node (ref "PD10") (pin "4") (pinfunction "DIN_4") (pintype "input"))
      (node (ref "PD9") (pin "2") (pinfunction "DOUT_2") (pintype "output"))
    )
    (net (code "91") (name "Net-(PD10-DOUT)") (class "Default")
      (node (ref "PD10") (pin "2") (pinfunction "DOUT_2") (pintype "output"))
      (node (ref "PD11") (pin "4") (pinfunction "DIN_4") (pintype "input"))
    )
    (net (code "92") (name "Net-(PD11-DOUT)") (class "Default")
      (node (ref "PD11") (pin "2") (pinfunction "DOUT_2") (pintype "output"))
      (node (ref "PD12") (pin "4") (pinfunction "DIN_4") (pintype "input"))
    )
    (net (code "93") (name "Net-(PD12-DOUT)") (class "Default")
      (node (ref "PD12") (pin "2") (pinfunction "DOUT_2") (pintype "output"))
      (node (ref "PD13") (pin "4") (pinfunction "DIN_4") (pintype "input"))
    )
    (net (code "94") (name "Net-(PD13-DOUT)") (class "Default")
      (node (ref "PD13") (pin "2") (pinfunction "DOUT_2") (pintype "output"))
      (node (ref "PD14") (pin "4") (pinfunction "DIN_4") (pintype "input"))
    )
    (net (code "95") (name "Net-(PD14-DOUT)") (class "Default")
      (node (ref "PD14") (pin "2") (pinfunction "DOUT_2") (pintype "output"))
      (node (ref "PD15") (pin "4") (pinfunction "DIN_4") (pintype "input"))
    )
    (net (code "96") (name "Net-(PD15-DOUT)") (class "Default")
      (node (ref "PD15") (pin "2") (pinfunction "DOUT_2") (pintype "output"))
      (node (ref "PD16") (pin "4") (pinfunction "DIN_4") (pintype "input"))
    )
    (net (code "97") (name "Net-(PD17-DOUT)") (class "Default")
      (node (ref "PD17") (pin "1") (pinfunction "DOUT_1") (pintype "output"))
      (node (ref "PD18") (pin "3") (pinfunction "DIN_3") (pintype "input"))
    )
    (net (code "98") (name "Net-(PD18-DOUT)") (class "Default")
      (node (ref "PD18") (pin "1") (pinfunction "DOUT_1") (pintype "output"))
      (node (ref "PD19") (pin "3") (pinfunction "DIN_3") (pintype "input"))
    )
    (net (code "99") (name "Net-(PD19-DOUT)") (class "Default")
      (node (ref "PD19") (pin "1") (pinfunction "DOUT_1") (pintype "output"))
      (node (ref "PD20") (pin "3") (pinfunction "DIN_3") (pintype "input"))
    )
    (net (code "100") (name "Net-(PD20-DOUT)") (class "Default")
      (node (ref "PD20") (pin "1") (pinfunction "DOUT_1") (pintype "output"))
      (node (ref "PD21") (pin "3") (pinfunction "DIN_3") (pintype "input"))
    )
    (net (code "101") (name "Net-(PD21-DOUT)") (class "Default")
      (node (ref "PD21") (pin "1") (pinfunction "DOUT_1") (pintype "output"))
      (node (ref "PD22") (pin "3") (pinfunction "DIN_3") (pintype "input"))
    )
    (net (code "102") (name "Net-(PD22-DOUT)") (class "Default")
      (node (ref "PD22") (pin "1") (pinfunction "DOUT_1") (pintype "output"))
      (node (ref "PD23") (pin "3") (pinfunction "DIN_3") (pintype "input"))
    )
    (net (code "103") (name "Net-(PD23-DOUT)") (class "Default")
      (node (ref "PD23") (pin "1") (pinfunction "DOUT_1") (pintype "output"))
      (node (ref "PD24") (pin "3") (pinfunction "DIN_3") (pintype "input"))
    )
    (net (code "104") (name "Net-(PD24-DOUT)") (class "Default")
      (node (ref "PD24") (pin "1") (pinfunction "DOUT_1") (pintype "output"))
      (node (ref "PD25") (pin "3") (pinfunction "DIN_3") (pintype "input"))
    )
    (net (code "105") (name "Net-(PD25-DOUT)") (class "Default")
      (node (ref "PD25") (pin "1") (pinfunction "DOUT_1") (pintype "output"))
      (node (ref "PD26") (pin "3") (pinfunction "DIN_3") (pintype "input"))
    )
    (net (code "106") (name "Net-(PD26-DOUT)") (class "Default")
      (node (ref "PD26") (pin "1") (pinfunction "DOUT_1") (pintype "output"))
      (node (ref "PD27") (pin "3") (pinfunction "DIN_3") (pintype "input"))
    )
    (net (code "107") (name "Net-(PD27-DOUT)") (class "Default")
      (node (ref "PD27") (pin "1") (pinfunction "DOUT_1") (pintype "output"))
      (node (ref "PD28") (pin "3") (pinfunction "DIN_3") (pintype "input"))
    )
    (net (code "108") (name "Net-(PD28-DOUT)") (class "Default")
      (node (ref "PD28") (pin "1") (pinfunction "DOUT_1") (pintype "output"))
      (node (ref "PD29") (pin "3") (pinfunction "DIN_3") (pintype "input"))
    )
    (net (code "109") (name "Net-(PD29-DOUT)") (class "Default")
      (node (ref "PD29") (pin "1") (pinfunction "DOUT_1") (pintype "output"))
      (node (ref "PD30") (pin "3") (pinfunction "DIN_3") (pintype "input"))
    )
    (net (code "110") (name "Net-(PD30-DOUT)") (class "Default")
      (node (ref "PD30") (pin "1") (pinfunction "DOUT_1") (pintype "output"))
      (node (ref "PD31") (pin "3") (pinfunction "DIN_3") (pintype "input"))
    )
    (net (code "111") (name "Net-(PD31-DOUT)") (class "Default")
      (node (ref "PD31") (pin "1") (pinfunction "DOUT_1") (pintype "output"))
      (node (ref "PD32") (pin "3") (pinfunction "DIN_3") (pintype "input"))
    )
    (net (code "112") (name "Net-(PD32-DOUT)") (class "Default")
      (node (ref "PD32") (pin "1") (pinfunction "DOUT_1") (pintype "output"))
      (node (ref "PD33") (pin "3") (pinfunction "DIN_3") (pintype "input"))
    )
    (net (code "113") (name "Net-(PD33-DOUT)") (class "Default")
      (node (ref "PD33") (pin "1") (pinfunction "DOUT_1") (pintype "output"))
      (node (ref "PD34") (pin "3") (pinfunction "DIN_3") (pintype "input"))
    )
    (net (code "114") (name "Net-(PD34-DOUT)") (class "Default")
      (node (ref "PD34") (pin "1") (pinfunction "DOUT_1") (pintype "output"))
      (node (ref "PD35") (pin "3") (pinfunction "DIN_3") (pintype "input"))
    )
    (net (code "115") (name "Net-(PD35-DOUT)") (class "Default")
      (node (ref "PD35") (pin "1") (pinfunction "DOUT_1") (pintype "output"))
      (node (ref "PD36") (pin "3") (pinfunction "DIN_3") (pintype "input"))
    )
    (net (code "116") (name "Net-(PD36-DOUT)") (class "Default")
      (node (ref "PD36") (pin "1") (pinfunction "DOUT_1") (pintype "output"))
      (node (ref "PD37") (pin "3") (pinfunction "DIN_3") (pintype "input"))
    )
    (net (code "117") (name "Net-(PD37-DOUT)") (class "Default")
      (node (ref "PD37") (pin "1") (pinfunction "DOUT_1") (pintype "output"))
      (node (ref "PD38") (pin "3") (pinfunction "DIN_3") (pintype "input"))
    )
    (net (code "118") (name "Net-(PD38-DOUT)") (class "Default")
      (node (ref "PD38") (pin "1") (pinfunction "DOUT_1") (pintype "output"))
      (node (ref "PD39") (pin "3") (pinfunction "DIN_3") (pintype "input"))
    )
    (net (code "119") (name "Net-(PD39-DOUT)") (class "Default")
      (node (ref "PD39") (pin "1") (pinfunction "DOUT_1") (pintype "output"))
      (node (ref "PD40") (pin "3") (pinfunction "DIN_3") (pintype "input"))
    )
    (net (code "120") (name "Net-(PD40-DOUT)") (class "Default")
      (node (ref "PD40") (pin "1") (pinfunction "DOUT_1") (pintype "output"))
      (node (ref "PD41") (pin "3") (pinfunction "DIN_3") (pintype "input"))
    )
    (net (code "121") (name "Net-(PD41-DOUT)") (class "Default")
      (node (ref "PD41") (pin "1") (pinfunction "DOUT_1") (pintype "output"))
      (node (ref "PD42") (pin "3") (pinfunction "DIN_3") (pintype "input"))
    )
    (net (code "122") (name "Net-(PD42-DOUT)") (class "Default")
      (node (ref "PD42") (pin "1") (pinfunction "DOUT_1") (pintype "output"))
      (node (ref "PD43") (pin "3") (pinfunction "DIN_3") (pintype "input"))
    )
    (net (code "123") (name "Net-(PD43-DOUT)") (class "Default")
      (node (ref "PD43") (pin "1") (pinfunction "DOUT_1") (pintype "output"))
      (node (ref "PD44") (pin "3") (pinfunction "DIN_3") (pintype "input"))
    )
    (net (code "124") (name "Net-(PD44-DOUT)") (class "Default")
      (node (ref "PD44") (pin "1") (pinfunction "DOUT_1") (pintype "output"))
      (node (ref "PD45") (pin "3") (pinfunction "DIN_3") (pintype "input"))
    )
    (net (code "125") (name "Net-(PD45-DOUT)") (class "Default")
      (node (ref "PD45") (pin "1") (pinfunction "DOUT_1") (pintype "output"))
      (node (ref "PD46") (pin "3") (pinfunction "DIN_3") (pintype "input"))
    )
    (net (code "126") (name "Net-(PD46-DOUT)") (class "Default")
      (node (ref "PD46") (pin "1") (pinfunction "DOUT_1") (pintype "output"))
      (node (ref "PD47") (pin "3") (pinfunction "DIN_3") (pintype "input"))
    )
    (net (code "127") (name "Net-(PD47-DOUT)") (class "Default")
      (node (ref "PD47") (pin "1") (pinfunction "DOUT_1") (pintype "output"))
      (node (ref "PD48") (pin "3") (pinfunction "DIN_3") (pintype "input"))
    )
    (net (code "128") (name "Net-(PD48-DOUT)") (class "Default")
      (node (ref "PD48") (pin "1") (pinfunction "DOUT_1") (pintype "output"))
      (node (ref "PD49") (pin "3") (pinfunction "DIN_3") (pintype "input"))
    )
    (net (code "129") (name "Net-(PD49-DOUT)") (class "Default")
      (node (ref "PD49") (pin "1") (pinfunction "DOUT_1") (pintype "output"))
      (node (ref "PD50") (pin "3") (pinfunction "DIN_3") (pintype "input"))
    )
    (net (code "130") (name "Net-(PD50-DOUT)") (class "Default")
      (node (ref "PD50") (pin "1") (pinfunction "DOUT_1") (pintype "output"))
      (node (ref "PD51") (pin "3") (pinfunction "DIN_3") (pintype "input"))
    )
    (net (code "131") (name "Net-(PD51-DOUT)") (class "Default")
      (node (ref "PD51") (pin "1") (pinfunction "DOUT_1") (pintype "output"))
      (node (ref "PD52") (pin "3") (pinfunction "DIN_3") (pintype "input"))
    )
    (net (code "132") (name "Net-(PD52-DOUT)") (class "Default")
      (node (ref "PD52") (pin "1") (pinfunction "DOUT_1") (pintype "output"))
      (node (ref "PD53") (pin "3") (pinfunction "DIN_3") (pintype "input"))
    )
    (net (code "133") (name "Net-(PD53-DOUT)") (class "Default")
      (node (ref "PD53") (pin "1") (pinfunction "DOUT_1") (pintype "output"))
      (node (ref "PD54") (pin "3") (pinfunction "DIN_3") (pintype "input"))
    )
    (net (code "134") (name "Net-(PD54-DOUT)") (class "Default")
      (node (ref "PD54") (pin "1") (pinfunction "DOUT_1") (pintype "output"))
      (node (ref "PD55") (pin "3") (pinfunction "DIN_3") (pintype "input"))
    )
    (net (code "135") (name "Net-(PD55-DOUT)") (class "Default")
      (node (ref "PD55") (pin "1") (pinfunction "DOUT_1") (pintype "output"))
      (node (ref "PD56") (pin "3") (pinfunction "DIN_3") (pintype "input"))
    )
    (net (code "136") (name "Net-(PD56-DOUT)") (class "Default")
      (node (ref "PD56") (pin "1") (pinfunction "DOUT_1") (pintype "output"))
      (node (ref "PD57") (pin "3") (pinfunction "DIN_3") (pintype "input"))
    )
    (net (code "137") (name "Net-(PD57-DOUT)") (class "Default")
      (node (ref "PD57") (pin "1") (pinfunction "DOUT_1") (pintype "output"))
      (node (ref "PD58") (pin "3") (pinfunction "DIN_3") (pintype "input"))
    )
    (net (code "138") (name "Net-(PD58-DOUT)") (class "Default")
      (node (ref "PD58") (pin "1") (pinfunction "DOUT_1") (pintype "output"))
      (node (ref "PD59") (pin "3") (pinfunction "DIN_3") (pintype "input"))
    )
    (net (code "139") (name "Net-(PD59-DOUT)") (class "Default")
      (node (ref "PD59") (pin "1") (pinfunction "DOUT_1") (pintype "output"))
      (node (ref "PD60") (pin "3") (pinfunction "DIN_3") (pintype "input"))
    )
    (net (code "140") (name "Net-(PD60-DOUT)") (class "Default")
      (node (ref "PD60") (pin "1") (pinfunction "DOUT_1") (pintype "output"))
      (node (ref "PD61") (pin "3") (pinfunction "DIN_3") (pintype "input"))
    )
    (net (code "141") (name "Net-(PD61-DOUT)") (class "Default")
      (node (ref "PD61") (pin "1") (pinfunction "DOUT_1") (pintype "output"))
      (node (ref "PD62") (pin "3") (pinfunction "DIN_3") (pintype "input"))
    )
    (net (code "142") (name "Net-(PD62-DOUT)") (class "Default")
      (node (ref "PD62") (pin "1") (pinfunction "DOUT_1") (pintype "output"))
      (node (ref "PD63") (pin "3") (pinfunction "DIN_3") (pintype "input"))
    )
    (net (code "143") (name "Net-(PD63-DOUT)") (class "Default")
      (node (ref "PD63") (pin "1") (pinfunction "DOUT_1") (pintype "output"))
      (node (ref "PD64") (pin "3") (pinfunction "DIN_3") (pintype "input"))
    )
    (net (code "144") (name "Net-(PD64-DOUT)") (class "Default")
      (node (ref "PD64") (pin "1") (pinfunction "DOUT_1") (pintype "output"))
      (node (ref "PD65") (pin "3") (pinfunction "DIN_3") (pintype "input"))
    )
    (net (code "145") (name "Net-(PD65-DOUT)") (class "Default")
      (node (ref "PD65") (pin "1") (pinfunction "DOUT_1") (pintype "output"))
      (node (ref "PD66") (pin "3") (pinfunction "DIN_3") (pintype "input"))
    )
    (net (code "146") (name "Net-(PD66-DOUT)") (class "Default")
      (node (ref "PD66") (pin "1") (pinfunction "DOUT_1") (pintype "output"))
      (node (ref "PD67") (pin "3") (pinfunction "DIN_3") (pintype "input"))
    )
    (net (code "147") (name "Net-(PD67-DOUT)") (class "Default")
      (node (ref "PD67") (pin "1") (pinfunction "DOUT_1") (pintype "output"))
      (node (ref "PD68") (pin "3") (pinfunction "DIN_3") (pintype "input"))
    )
    (net (code "148") (name "Net-(PD68-DOUT)") (class "Default")
      (node (ref "PD68") (pin "1") (pinfunction "DOUT_1") (pintype "output"))
      (node (ref "PD69") (pin "3") (pinfunction "DIN_3") (pintype "input"))
    )
    (net (code "149") (name "Net-(PD69-DOUT)") (class "Default")
      (node (ref "PD69") (pin "1") (pinfunction "DOUT_1") (pintype "output"))
      (node (ref "PD70") (pin "3") (pinfunction "DIN_3") (pintype "input"))
    )
    (net (code "150") (name "Net-(PD70-DOUT)") (class "Default")
      (node (ref "PD70") (pin "1") (pinfunction "DOUT_1") (pintype "output"))
      (node (ref "PD71") (pin "3") (pinfunction "DIN_3") (pintype "input"))
    )
    (net (code "151") (name "Net-(PD71-DOUT)") (class "Default")
      (node (ref "PD71") (pin "1") (pinfunction "DOUT_1") (pintype "output"))
      (node (ref "PD72") (pin "3") (pinfunction "DIN_3") (pintype "input"))
    )
    (net (code "152") (name "Net-(PD72-DOUT)") (class "Default")
      (node (ref "PD72") (pin "1") (pinfunction "DOUT_1") (pintype "output"))
      (node (ref "PD73") (pin "3") (pinfunction "DIN_3") (pintype "input"))
    )
    (net (code "153") (name "Net-(PD73-DOUT)") (class "Default")
      (node (ref "PD73") (pin "1") (pinfunction "DOUT_1") (pintype "output"))
      (node (ref "PD74") (pin "3") (pinfunction "DIN_3") (pintype "input"))
    )
    (net (code "154") (name "Net-(PD74-DOUT)") (class "Default")
      (node (ref "PD74") (pin "1") (pinfunction "DOUT_1") (pintype "output"))
      (node (ref "PD75") (pin "3") (pinfunction "DIN_3") (pintype "input"))
    )
    (net (code "155") (name "Net-(PD75-DOUT)") (class "Default")
      (node (ref "PD75") (pin "1") (pinfunction "DOUT_1") (pintype "output"))
      (node (ref "PD76") (pin "3") (pinfunction "DIN_3") (pintype "input"))
    )
    (net (code "156") (name "Net-(PD76-DOUT)") (class "Default")
      (node (ref "PD76") (pin "1") (pinfunction "DOUT_1") (pintype "output"))
      (node (ref "PD77") (pin "3") (pinfunction "DIN_3") (pintype "input"))
    )
    (net (code "157") (name "Net-(PD77-DOUT)") (class "Default")
      (node (ref "PD77") (pin "1") (pinfunction "DOUT_1") (pintype "output"))
      (node (ref "PD78") (pin "3") (pinfunction "DIN_3") (pintype "input"))
    )
    (net (code "158") (name "Net-(PD78-DOUT)") (class "Default")
      (node (ref "PD78") (pin "1") (pinfunction "DOUT_1") (pintype "output"))
      (node (ref "PD79") (pin "3") (pinfunction "DIN_3") (pintype "input"))
    )
    (net (code "159") (name "Net-(PD79-DOUT)") (class "Default")
      (node (ref "PD79") (pin "1") (pinfunction "DOUT_1") (pintype "output"))
      (node (ref "PD80") (pin "3") (pinfunction "DIN_3") (pintype "input"))
    )
    (net (code "160") (name "Net-(PD80-DOUT)") (class "Default")
      (node (ref "PD80") (pin "1") (pinfunction "DOUT_1") (pintype "output"))
      (node (ref "PD81") (pin "3") (pinfunction "DIN_3") (pintype "input"))
    )
    (net (code "161") (name "Net-(PD81-DOUT)") (class "Default")
      (node (ref "PD81") (pin "1") (pinfunction "DOUT_1") (pintype "output"))
      (node (ref "PD82") (pin "3") (pinfunction "DIN_3") (pintype "input"))
    )
    (net (code "162") (name "Net-(PD82-DOUT)") (class "Default")
      (node (ref "PD82") (pin "1") (pinfunction "DOUT_1") (pintype "output"))
      (node (ref "PD83") (pin "3") (pinfunction "DIN_3") (pintype "input"))
    )
    (net (code "163") (name "Net-(PD83-DOUT)") (class "Default")
      (node (ref "PD83") (pin "1") (pinfunction "DOUT_1") (pintype "output"))
      (node (ref "PD84") (pin "3") (pinfunction "DIN_3") (pintype "input"))
    )
    (net (code "164") (name "Net-(PD84-DOUT)") (class "Default")
      (node (ref "PD84") (pin "1") (pinfunction "DOUT_1") (pintype "output"))
      (node (ref "PD85") (pin "3") (pinfunction "DIN_3") (pintype "input"))
    )
    (net (code "165") (name "Net-(PD85-DOUT)") (class "Default")
      (node (ref "PD85") (pin "1") (pinfunction "DOUT_1") (pintype "output"))
      (node (ref "PD86") (pin "3") (pinfunction "DIN_3") (pintype "input"))
    )
    (net (code "166") (name "Net-(PD86-DOUT)") (class "Default")
      (node (ref "PD86") (pin "1") (pinfunction "DOUT_1") (pintype "output"))
      (node (ref "PD87") (pin "3") (pinfunction "DIN_3") (pintype "input"))
    )
    (net (code "167") (name "Net-(PD87-DOUT)") (class "Default")
      (node (ref "PD87") (pin "1") (pinfunction "DOUT_1") (pintype "output"))
      (node (ref "PD88") (pin "3") (pinfunction "DIN_3") (pintype "input"))
    )
    (net (code "168") (name "Net-(PD88-DOUT)") (class "Default")
      (node (ref "PD88") (pin "1") (pinfunction "DOUT_1") (pintype "output"))
      (node (ref "PD89") (pin "3") (pinfunction "DIN_3") (pintype "input"))
    )
    (net (code "169") (name "Net-(PD89-DOUT)") (class "Default")
      (node (ref "PD89") (pin "1") (pinfunction "DOUT_1") (pintype "output"))
      (node (ref "PD90") (pin "3") (pinfunction "DIN_3") (pintype "input"))
    )
    (net (code "170") (name "Net-(PD90-DOUT)") (class "Default")
      (node (ref "PD90") (pin "1") (pinfunction "DOUT_1") (pintype "output"))
      (node (ref "PD91") (pin "3") (pinfunction "DIN_3") (pintype "input"))
    )
    (net (code "171") (name "Net-(PD91-DOUT)") (class "Default")
      (node (ref "PD91") (pin "1") (pinfunction "DOUT_1") (pintype "output"))
      (node (ref "PD92") (pin "3") (pinfunction "DIN_3") (pintype "input"))
    )
    (net (code "172") (name "Net-(PD92-DOUT)") (class "Default")
      (node (ref "PD92") (pin "1") (pinfunction "DOUT_1") (pintype "output"))
      (node (ref "PD93") (pin "3") (pinfunction "DIN_3") (pintype "input"))
    )
    (net (code "173") (name "Net-(PD93-DOUT)") (class "Default")
      (node (ref "PD93") (pin "1") (pinfunction "DOUT_1") (pintype "output"))
      (node (ref "PD94") (pin "3") (pinfunction "DIN_3") (pintype "input"))
    )
    (net (code "174") (name "Net-(PD94-DOUT)") (class "Default")
      (node (ref "PD94") (pin "1") (pinfunction "DOUT_1") (pintype "output"))
      (node (ref "PD95") (pin "3") (pinfunction "DIN_3") (pintype "input"))
    )
    (net (code "175") (name "Net-(PD95-DOUT)") (class "Default")
      (node (ref "PD95") (pin "1") (pinfunction "DOUT_1") (pintype "output"))
      (node (ref "PD96") (pin "3") (pinfunction "DIN_3") (pintype "input"))
    )
    (net (code "176") (name "Net-(PD96-DOUT)") (class "Default")
      (node (ref "PD96") (pin "1") (pinfunction "DOUT_1") (pintype "output"))
      (node (ref "PD97") (pin "3") (pinfunction "DIN_3") (pintype "input"))
    )
    (net (code "177") (name "Net-(PD97-DOUT)") (class "Default")
      (node (ref "PD97") (pin "1") (pinfunction "DOUT_1") (pintype "output"))
      (node (ref "PD98") (pin "3") (pinfunction "DIN_3") (pintype "input"))
    )
    (net (code "178") (name "Net-(PD98-DOUT)") (class "Default")
      (node (ref "PD98") (pin "1") (pinfunction "DOUT_1") (pintype "output"))
      (node (ref "PD99") (pin "3") (pinfunction "DIN_3") (pintype "input"))
    )
    (net (code "179") (name "Net-(PD100-DIN)") (class "Default")
      (node (ref "PD100") (pin "3") (pinfunction "DIN_3") (pintype "input"))
      (node (ref "PD99") (pin "1") (pinfunction "DOUT_1") (pintype "output"))
    )
    (net (code "180") (name "Net-(PD100-DOUT)") (class "Default")
      (node (ref "PD100") (pin "1") (pinfunction "DOUT_1") (pintype "output"))
      (node (ref "PD101") (pin "3") (pinfunction "DIN_3") (pintype "input"))
    )
    (net (code "181") (name "Net-(PD101-DOUT)") (class "Default")
      (node (ref "PD101") (pin "1") (pinfunction "DOUT_1") (pintype "output"))
      (node (ref "PD102") (pin "3") (pinfunction "DIN_3") (pintype "input"))
    )
    (net (code "182") (name "Net-(PD102-DOUT)") (class "Default")
      (node (ref "PD102") (pin "1") (pinfunction "DOUT_1") (pintype "output"))
      (node (ref "PD103") (pin "3") (pinfunction "DIN_3") (pintype "input"))
    )
    (net (code "183") (name "Net-(PD103-DOUT)") (class "Default")
      (node (ref "PD103") (pin "1") (pinfunction "DOUT_1") (pintype "output"))
      (node (ref "PD104") (pin "3") (pinfunction "DIN_3") (pintype "input"))
    )
    (net (code "184") (name "Net-(PD104-DOUT)") (class "Default")
      (node (ref "PD104") (pin "1") (pinfunction "DOUT_1") (pintype "output"))
      (node (ref "PD105") (pin "3") (pinfunction "DIN_3") (pintype "input"))
    )
    (net (code "185") (name "Net-(PD105-DOUT)") (class "Default")
      (node (ref "PD105") (pin "1") (pinfunction "DOUT_1") (pintype "output"))
      (node (ref "PD106") (pin "3") (pinfunction "DIN_3") (pintype "input"))
    )
    (net (code "186") (name "Net-(PD106-DOUT)") (class "Default")
      (node (ref "PD106") (pin "1") (pinfunction "DOUT_1") (pintype "output"))
      (node (ref "PD107") (pin "3") (pinfunction "DIN_3") (pintype "input"))
    )
    (net (code "187") (name "Net-(PD107-DOUT)") (class "Default")
      (node (ref "PD107") (pin "1") (pinfunction "DOUT_1") (pintype "output"))
      (node (ref "PD108") (pin "3") (pinfunction "DIN_3") (pintype "input"))
    )
    (net (code "188") (name "Net-(PD108-DOUT)") (class "Default")
      (node (ref "PD108") (pin "1") (pinfunction "DOUT_1") (pintype "output"))
      (node (ref "PD109") (pin "3") (pinfunction "DIN_3") (pintype "input"))
    )
    (net (code "189") (name "Net-(PD109-DOUT)") (class "Default")
      (node (ref "PD109") (pin "1") (pinfunction "DOUT_1") (pintype "output"))
      (node (ref "PD110") (pin "3") (pinfunction "DIN_3") (pintype "input"))
    )
    (net (code "190") (name "Net-(Q2-2)") (class "Default")
      (node (ref "C13") (pin "2") (pinfunction "2_2") (pintype "passive"))
      (node (ref "Q2") (pin "4") (pinfunction "2_4") (pintype "passive"))
      (node (ref "U3") (pin "3") (pinfunction "PC14-OSC32_IN_3") (pintype "input"))
    )
    (net (code "191") (name "Net-(R1-Pad2)") (class "Default")
      (node (ref "R1") (pin "2") (pinfunction "2_2") (pintype "passive"))
      (node (ref "U2") (pin "RX") (pinfunction "RX_RX") (pintype "bidirectional"))
    )
    (net (code "192") (name "Net-(R9-Pad2)") (class "Default")
      (node (ref "R9") (pin "2") (pinfunction "2_2") (pintype "passive"))
      (node (ref "T1") (pin "B") (pinfunction "B_B") (pintype "passive"))
    )
    (net (code "193") (name "Net-(R10-Pad2)") (class "Default")
      (node (ref "R10") (pin "2") (pinfunction "2_2") (pintype "passive"))
      (node (ref "T2") (pin "B") (pinfunction "B_B") (pintype "passive"))
    )
    (net (code "194") (name "Net-(R11-Pad2)") (class "Default")
      (node (ref "R11") (pin "2") (pinfunction "2_2") (pintype "passive"))
      (node (ref "T3") (pin "B") (pinfunction "B_B") (pintype "passive"))
    )
    (net (code "195") (name "Net-(R68-Pad1)") (class "Default")
      (node (ref "R68") (pin "1") (pinfunction "1_1") (pintype "passive"))
      (node (ref "R69") (pin "2") (pinfunction "2_2") (pintype "passive"))
    )
    (net (code "196") (name "Net-(R70-Pad1)") (class "Default")
      (node (ref "R70") (pin "1") (pinfunction "1_1") (pintype "passive"))
      (node (ref "R71") (pin "2") (pinfunction "2_2") (pintype "passive"))
    )
    (net (code "197") (name "Net-(U1-STB)") (class "Default")
      (node (ref "R2") (pin "2") (pinfunction "2_2") (pintype "passive"))
      (node (ref "U1") (pin "8") (pinfunction "STB_8") (pintype "bidirectional"))
    )
    (net (code "198") (name "Net-(U1-VCC)") (class "Default")
      (node (ref "C1") (pin "+") (pinfunction "+_+") (pintype "passive"))
      (node (ref "C2") (pin "2") (pinfunction "2_2") (pintype "passive"))
      (node (ref "L1") (pin "1") (pinfunction "1_1") (pintype "passive"))
      (node (ref "U1") (pin "3") (pinfunction "VCC_3") (pintype "bidirectional"))
    )
    (net (code "199") (name "Net-(U2-SPK_1)") (class "Default")
      (node (ref "P1") (pin "2") (pinfunction "2_2") (pintype "passive"))
      (node (ref "U2") (pin "SPK1") (pinfunction "SPK_1_SPK1") (pintype "bidirectional"))
    )
    (net (code "200") (name "Net-(U2-SPK_2)") (class "Default")
      (node (ref "P1") (pin "1") (pinfunction "1_1") (pintype "passive"))
      (node (ref "U2") (pin "SPK2") (pinfunction "SPK_2_SPK2") (pintype "bidirectional"))
    )
    (net (code "201") (name "Net-(U3-PC15-OSC32_OUT)") (class "Default")
      (node (ref "C14") (pin "2") (pinfunction "2_2") (pintype "passive"))
      (node (ref "Q2") (pin "1") (pinfunction "1_1") (pintype "passive"))
      (node (ref "U3") (pin "4") (pinfunction "PC15-OSC32_OUT_4") (pintype "output"))
    )
    (net (code "202") (name "Net-(U3-PD0_OSC_IN)") (class "Default")
      (node (ref "C11") (pin "2") (pinfunction "2_2") (pintype "passive"))
      (node (ref "Q1") (pin "1") (pinfunction "1_1") (pintype "passive"))
      (node (ref "U3") (pin "5") (pinfunction "PD0_OSC_IN_5") (pintype "input"))
    )
    (net (code "203") (name "Net-(U3-PD1_OSC_OUT)") (class "Default")
      (node (ref "R5") (pin "2") (pinfunction "2_2") (pintype "passive"))
      (node (ref "U3") (pin "6") (pinfunction "PD1_OSC_OUT_6") (pintype "output"))
    )
    (net (code "204") (name "Net-(U3-VBAT)") (class "Default")
      (node (ref "C7") (pin "+") (pinfunction "+_+") (pintype "passive"))
      (node (ref "C8") (pin "1") (pinfunction "1_1") (pintype "passive"))
      (node (ref "C9") (pin "1") (pinfunction "1_1") (pintype "passive"))
      (node (ref "L3") (pin "1") (pinfunction "1_1") (pintype "passive"))
      (node (ref "U3") (pin "1") (pinfunction "VBAT_1") (pintype "input"))
      (node (ref "U3") (pin "13") (pinfunction "VDDA_13") (pintype "power_in"))
      (node (ref "U3") (pin "19") (pinfunction "VDD_4_19") (pintype "power_in"))
      (node (ref "U3") (pin "32") (pinfunction "VDD_1_32") (pintype "power_in"))
      (node (ref "U3") (pin "48") (pinfunction "VDD_2_48") (pintype "power_in"))
      (node (ref "U3") (pin "64") (pinfunction "VDD_3_64") (pintype "power_in"))
    )
    (net (code "205") (name "Net-(U4-VIN)") (class "Default")
      (node (ref "C27") (pin "+") (pinfunction "+_+") (pintype "passive"))
      (node (ref "C28") (pin "1") (pinfunction "1_1") (pintype "passive"))
      (node (ref "C29") (pin "2") (pinfunction "2_2") (pintype "passive"))
      (node (ref "C30") (pin "2") (pinfunction "2_2") (pintype "passive"))
      (node (ref "C31") (pin "2") (pinfunction "2_2") (pintype "passive"))
      (node (ref "L4") (pin "2") (pinfunction "2_2") (pintype "passive"))
      (node (ref "U4") (pin "1") (pinfunction "VIN_1") (pintype "input"))
      (node (ref "U5") (pin "1") (pinfunction "VIN_1") (pintype "input"))
    )
    (net (code "206") (name "Net-(U6-NRST)") (class "Default")
      (node (ref "C39") (pin "2") (pinfunction "2_2") (pintype "passive"))
      (node (ref "JP3") (pin "5") (pinfunction "5_5") (pintype "passive"))
      (node (ref "R53") (pin "1") (pinfunction "1_1") (pintype "passive"))
      (node (ref "U6") (pin "4") (pinfunction "NRST_4") (pintype "bidirectional"))
    )
    (net (code "207") (name "Net-(U6-PA5)") (class "Default")
      (node (ref "U6") (pin "11") (pinfunction "PA5_11") (pintype "bidirectional"))
      (node (ref "U6") (pin "12") (pinfunction "PA6_12") (pintype "bidirectional"))
    )
    (net (code "208") (name "Net-(U6-PA7)") (class "Default")
      (node (ref "U6") (pin "13") (pinfunction "PA7_13") (pintype "bidirectional"))
      (node (ref "U6") (pin "2") (pinfunction "PF0/OSC_IN_2") (pintype "bidirectional"))
    )
    (net (code "209") (name "Net-(U6-PA9)") (class "Default")
      (node (ref "R54") (pin "2") (pinfunction "2_2") (pintype "passive"))
      (node (ref "U6") (pin "17") (pinfunction "PA9_17") (pintype "bidirectional"))
      (node (ref "U8") (pin "6") (pinfunction "SCL_6") (pintype "input"))
    )
    (net (code "210") (name "Net-(U6-PA10)") (class "Default")
      (node (ref "R58") (pin "1") (pinfunction "1_1") (pintype "passive"))
      (node (ref "U6") (pin "18") (pinfunction "PA10_18") (pintype "bidirectional"))
      (node (ref "U8") (pin "5") (pinfunction "SDA_5") (pintype "bidirectional"))
    )
    (net (code "211") (name "Net-(U6-PA13)") (class "Default")
      (node (ref "JP3") (pin "4") (pinfunction "4_4") (pintype "passive"))
      (node (ref "U6") (pin "19") (pinfunction "PA13_19") (pintype "bidirectional"))
    )
    (net (code "212") (name "Net-(U6-PA14)") (class "Default")
      (node (ref "JP3") (pin "2") (pinfunction "2_2") (pintype "passive"))
      (node (ref "U6") (pin "20") (pinfunction "PA14_20") (pintype "bidirectional"))
    )
    (net (code "213") (name "Net-(U6-VDD)") (class "Default")
      (node (ref "C37") (pin "2") (pinfunction "2_2") (pintype "passive"))
      (node (ref "C38") (pin "+") (pinfunction "+_+") (pintype "passive"))
      (node (ref "L5") (pin "2") (pinfunction "2_2") (pintype "passive"))
      (node (ref "U6") (pin "16") (pinfunction "VDD_16") (pintype "bidirectional"))
      (node (ref "U6") (pin "5") (pinfunction "VDDA_5") (pintype "bidirectional"))
    )
    (net (code "214") (name "Net-(U7-DIR)") (class "Default")
      (node (ref "R55") (pin "2") (pinfunction "2_2") (pintype "passive"))
      (node (ref "U7") (pin "5") (pinfunction "DIR_5") (pintype "input"))
    )
    (net (code "215") (name "Net-(U7-VCCA)") (class "Default")
      (node (ref "L7") (pin "2") (pinfunction "2_2") (pintype "passive"))
      (node (ref "R55") (pin "1") (pinfunction "1_1") (pintype "passive"))
      (node (ref "U7") (pin "1") (pinfunction "VCCA_1") (pintype "power_in"))
    )
    (net (code "216") (name "Net-(U7-VCCB)") (class "Default")
      (node (ref "L6") (pin "2") (pinfunction "2_2") (pintype "passive"))
      (node (ref "U7") (pin "6") (pinfunction "VCCB_6") (pintype "power_in"))
    )
    (net (code "217") (name "Net-(V1-+VOUT)") (class "Default")
      (node (ref "D4") (pin "A") (pinfunction "A_A") (pintype "passive"))
      (node (ref "V1") (pin "4") (pinfunction "+VOUT_4") (pintype "passive"))
    )
    (net (code "218") (name "Net-(X1-3)") (class "Default")
      (node (ref "X1") (pin "P$3") (pinfunction "3_P$3") (pintype "passive"))
      (node (ref "X2") (pin "P$3") (pinfunction "3_P$3") (pintype "passive"))
    )
    (net (code "219") (name "Net-(X3-3)") (class "Default")
      (node (ref "X3") (pin "P$3") (pinfunction "3_P$3") (pintype "passive"))
      (node (ref "X4") (pin "P$3") (pinfunction "3_P$3") (pintype "passive"))
    )
    (net (code "220") (name "Net-(X3-4)") (class "Default")
      (node (ref "X3") (pin "P$4") (pinfunction "4_P$4") (pintype "passive"))
      (node (ref "X4") (pin "P$4") (pinfunction "4_P$4") (pintype "passive"))
    )
    (net (code "221") (name "Net-(X5V-S)") (class "Default")
      (node (ref "L10") (pin "2") (pinfunction "2_2") (pintype "passive"))
      (node (ref "X5") (pin "29") (pinfunction "S_29") (pintype "passive"))
    )
    (net (code "222") (name "OLED_16X2_CLK") (class "Default")
      (node (ref "DISPLAY1") (pin "18") (pinfunction "D0_18") (pintype "bidirectional"))
      (node (ref "U3") (pin "34") (pinfunction "PB13_34") (pintype "bidirectional"))
    )
    (net (code "223") (name "OLED_16X2_DC") (class "Default")
      (node (ref "DISPLAY1") (pin "15") (pinfunction "D/C#_15") (pintype "bidirectional"))
      (node (ref "U3") (pin "35") (pinfunction "PB14_35") (pintype "bidirectional"))
    )
    (net (code "224") (name "OLED_16X2_MOSI") (class "Default")
      (node (ref "DISPLAY1") (pin "19") (pinfunction "D1_19") (pintype "bidirectional"))
      (node (ref "U3") (pin "36") (pinfunction "PB15_36") (pintype "bidirectional"))
    )
    (net (code "225") (name "OLED_16X2_RST") (class "Default")
      (node (ref "DISPLAY1") (pin "14") (pinfunction "RES#_14") (pintype "bidirectional"))
      (node (ref "U3") (pin "33") (pinfunction "PB12_33") (pintype "bidirectional"))
    )
    (net (code "226") (name "OLED_BIG_CLK") (class "Default")
      (node (ref "U3") (pin "55") (pinfunction "PB3_55") (pintype "bidirectional"))
      (node (ref "X5") (pin "19") (pinfunction "S_19") (pintype "passive"))
    )
    (net (code "227") (name "OLED_BIG_DC") (class "Default")
      (node (ref "U3") (pin "54") (pinfunction "PD2_54") (pintype "bidirectional"))
      (node (ref "X5") (pin "16") (pinfunction "S_16") (pintype "passive"))
    )
    (net (code "228") (name "OLED_BIG_MOSI") (class "Default")
      (node (ref "U3") (pin "57") (pinfunction "PB5_57") (pintype "bidirectional"))
      (node (ref "X5") (pin "20") (pinfunction "S_20") (pintype "passive"))
    )
    (net (code "229") (name "OLED_BIG_RES") (class "Default")
      (node (ref "U3") (pin "53") (pinfunction "PC12_53") (pintype "bidirectional"))
      (node (ref "X5") (pin "15") (pinfunction "S_15") (pintype "passive"))
    )
    (net (code "230") (name "PLAYER_RX") (class "Default")
      (node (ref "R1") (pin "1") (pinfunction "1_1") (pintype "passive"))
      (node (ref "U3") (pin "16") (pinfunction "PA2_16") (pintype "bidirectional"))
    )
    (net (code "231") (name "PLAYER_TX") (class "Default")
      (node (ref "U2") (pin "TX") (pinfunction "TX_TX") (pintype "bidirectional"))
      (node (ref "U3") (pin "17") (pinfunction "PA3_17") (pintype "bidirectional"))
    )
    (net (code "232") (name "SCL_OLED1") (class "Default")
      (node (ref "IC1") (pin "5") (pinfunction "SC0_5") (pintype "bidirectional"))
      (node (ref "P4") (pin "3") (pinfunction "3_3") (pintype "passive"))
      (node (ref "R60") (pin "1") (pinfunction "1_1") (pintype "passive"))
      (node (ref "U11") (pin "3") (pinfunction "SCL_3") (pintype "bidirectional"))
    )
    (net (code "233") (name "SCL_OLED2") (class "Default")
      (node (ref "IC1") (pin "7") (pinfunction "SC1_7") (pintype "bidirectional"))
      (node (ref "P3") (pin "3") (pinfunction "3_3") (pintype "passive"))
      (node (ref "R62") (pin "1") (pinfunction "1_1") (pintype "passive"))
      (node (ref "U10") (pin "3") (pinfunction "SCL_3") (pintype "bidirectional"))
    )
    (net (code "234") (name "SCL_OLED3") (class "Default")
      (node (ref "IC1") (pin "9") (pinfunction "SC2_9") (pintype "bidirectional"))
      (node (ref "P2") (pin "3") (pinfunction "3_3") (pintype "passive"))
      (node (ref "R64") (pin "1") (pinfunction "1_1") (pintype "passive"))
      (node (ref "U9") (pin "3") (pinfunction "SCL_3") (pintype "bidirectional"))
    )
    (net (code "235") (name "SDA_OLED1") (class "Default")
      (node (ref "IC1") (pin "4") (pinfunction "SD0_4") (pintype "bidirectional"))
      (node (ref "P4") (pin "4") (pinfunction "4_4") (pintype "passive"))
      (node (ref "R59") (pin "1") (pinfunction "1_1") (pintype "passive"))
      (node (ref "U11") (pin "4") (pinfunction "SDA_4") (pintype "bidirectional"))
    )
    (net (code "236") (name "SDA_OLED2") (class "Default")
      (node (ref "IC1") (pin "6") (pinfunction "SD1_6") (pintype "bidirectional"))
      (node (ref "P3") (pin "4") (pinfunction "4_4") (pintype "passive"))
      (node (ref "R61") (pin "1") (pinfunction "1_1") (pintype "passive"))
      (node (ref "U10") (pin "4") (pinfunction "SDA_4") (pintype "bidirectional"))
    )
    (net (code "237") (name "SDA_OLED3") (class "Default")
      (node (ref "IC1") (pin "8") (pinfunction "SD2_8") (pintype "bidirectional"))
      (node (ref "P2") (pin "4") (pinfunction "4_4") (pintype "passive"))
      (node (ref "R63") (pin "1") (pinfunction "1_1") (pintype "passive"))
      (node (ref "U9") (pin "4") (pinfunction "SDA_4") (pintype "bidirectional"))
    )
    (net (code "238") (name "SWCLK") (class "Default")
      (node (ref "JP1") (pin "2") (pinfunction "2_2") (pintype "passive"))
      (node (ref "U3") (pin "49") (pinfunction "PA14_49") (pintype "bidirectional"))
    )
    (net (code "239") (name "SWDIO") (class "Default")
      (node (ref "JP1") (pin "4") (pinfunction "4_4") (pintype "passive"))
      (node (ref "U3") (pin "46") (pinfunction "PA13_46") (pintype "bidirectional"))
    )
    (net (code "240") (name "UART_EXT_RX") (class "Default")
      (node (ref "JP2") (pin "3") (pinfunction "3_3") (pintype "passive"))
      (node (ref "U3") (pin "52") (pinfunction "PC11_52") (pintype "bidirectional"))
    )
    (net (code "241") (name "UART_EXT_TX") (class "Default")
      (node (ref "JP2") (pin "2") (pinfunction "2_2") (pintype "passive"))
      (node (ref "U3") (pin "51") (pinfunction "PC10_51") (pintype "bidirectional"))
    )
    (net (code "242") (name "VCOMH") (class "Default")
      (node (ref "C45") (pin "2") (pinfunction "2_2") (pintype "passive"))
      (node (ref "X5") (pin "28") (pinfunction "S_28") (pintype "passive"))
    )
    (net (code "243") (name "VDD") (class "Default")
      (node (ref "V2") (pin "C") (pinfunction "C_C") (pintype "passive"))
      (node (ref "X5") (pin "10") (pinfunction "S_10") (pintype "passive"))
    )
    (net (code "244") (name "unconnected-(DISPLAY1-GPIO-Pad12)") (class "Default")
      (node (ref "DISPLAY1") (pin "12") (pinfunction "GPIO_12") (pintype "bidirectional"))
    )
    (net (code "245") (name "unconnected-(DISPLAY1-NC1-Pad1)") (class "Default")
      (node (ref "DISPLAY1") (pin "1") (pinfunction "NC1_1") (pintype "bidirectional"))
    )
    (net (code "246") (name "unconnected-(DISPLAY1-NC2-Pad33)") (class "Default")
      (node (ref "DISPLAY1") (pin "33") (pinfunction "NC2_33") (pintype "bidirectional"))
    )
    (net (code "247") (name "unconnected-(DISPLAY1-VSL-Pad2)") (class "Default")
      (node (ref "DISPLAY1") (pin "2") (pinfunction "VSL_2") (pintype "bidirectional"))
    )
    (net (code "248") (name "unconnected-(IC1-SC3-Pad11)") (class "Default")
      (node (ref "IC1") (pin "11") (pinfunction "SC3_11") (pintype "bidirectional"))
    )
    (net (code "249") (name "unconnected-(IC1-SC4-Pad14)") (class "Default")
      (node (ref "IC1") (pin "14") (pinfunction "SC4_14") (pintype "bidirectional"))
    )
    (net (code "250") (name "unconnected-(IC1-SC5-Pad16)") (class "Default")
      (node (ref "IC1") (pin "16") (pinfunction "SC5_16") (pintype "bidirectional"))
    )
    (net (code "251") (name "unconnected-(IC1-SC6-Pad18)") (class "Default")
      (node (ref "IC1") (pin "18") (pinfunction "SC6_18") (pintype "bidirectional"))
    )
    (net (code "252") (name "unconnected-(IC1-SC7-Pad20)") (class "Default")
      (node (ref "IC1") (pin "20") (pinfunction "SC7_20") (pintype "bidirectional"))
    )
    (net (code "253") (name "unconnected-(IC1-SD3-Pad10)") (class "Default")
      (node (ref "IC1") (pin "10") (pinfunction "SD3_10") (pintype "bidirectional"))
    )
    (net (code "254") (name "unconnected-(IC1-SD4-Pad13)") (class "Default")
      (node (ref "IC1") (pin "13") (pinfunction "SD4_13") (pintype "bidirectional"))
    )
    (net (code "255") (name "unconnected-(IC1-SD5-Pad15)") (class "Default")
      (node (ref "IC1") (pin "15") (pinfunction "SD5_15") (pintype "bidirectional"))
    )
    (net (code "256") (name "unconnected-(IC1-SD6-Pad17)") (class "Default")
      (node (ref "IC1") (pin "17") (pinfunction "SD6_17") (pintype "bidirectional"))
    )
    (net (code "257") (name "unconnected-(IC1-SD7-Pad19)") (class "Default")
      (node (ref "IC1") (pin "19") (pinfunction "SD7_19") (pintype "bidirectional"))
    )
    (net (code "258") (name "unconnected-(JP1-Pad6)") (class "Default")
      (node (ref "JP1") (pin "6") (pinfunction "6_6") (pintype "passive"))
    )
    (net (code "259") (name "unconnected-(JP3-Pad6)") (class "Default")
      (node (ref "JP3") (pin "6") (pinfunction "6_6") (pintype "passive"))
    )
    (net (code "260") (name "unconnected-(PD110-DOUT-Pad1)") (class "Default")
      (node (ref "PD110") (pin "1") (pinfunction "DOUT_1") (pintype "output"))
    )
    (net (code "261") (name "unconnected-(U2-ADKEY_1-PadADKEY1)") (class "Default")
      (node (ref "U2") (pin "ADKEY1") (pinfunction "ADKEY_1_ADKEY1") (pintype "bidirectional"))
    )
    (net (code "262") (name "unconnected-(U2-ADKEY_2-PadADKEY2)") (class "Default")
      (node (ref "U2") (pin "ADKEY2") (pinfunction "ADKEY_2_ADKEY2") (pintype "bidirectional"))
    )
    (net (code "263") (name "unconnected-(U2-IO_1-PadIO1)") (class "Default")
      (node (ref "U2") (pin "IO1") (pinfunction "IO_1_IO1") (pintype "bidirectional"))
    )
    (net (code "264") (name "unconnected-(U2-IO_2-PadIO2)") (class "Default")
      (node (ref "U2") (pin "IO2") (pinfunction "IO_2_IO2") (pintype "bidirectional"))
    )
    (net (code "265") (name "unconnected-(U2-PadBUSY)") (class "Default")
      (node (ref "U2") (pin "BUSY") (pinfunction "BUSY_BUSY") (pintype "bidirectional"))
    )
    (net (code "266") (name "unconnected-(U2-PadDAC_L)") (class "Default")
      (node (ref "U2") (pin "DAC_L") (pinfunction "DAC_L_DAC_L") (pintype "bidirectional"))
    )
    (net (code "267") (name "unconnected-(U2-PadDAC_R)") (class "Default")
      (node (ref "U2") (pin "DAC_R") (pinfunction "DAC_R_DAC_R") (pintype "bidirectional"))
    )
    (net (code "268") (name "unconnected-(U2-PadUSB+)") (class "Default")
      (node (ref "U2") (pin "USB+") (pinfunction "USB+_USB+") (pintype "bidirectional"))
    )
    (net (code "269") (name "unconnected-(U2-PadUSB-)") (class "Default")
      (node (ref "U2") (pin "USB-") (pinfunction "USB-_USB-") (pintype "bidirectional"))
    )
    (net (code "270") (name "unconnected-(U3-PA0-WKUP-Pad14)") (class "Default")
      (node (ref "U3") (pin "14") (pinfunction "PA0-WKUP_14") (pintype "bidirectional"))
    )
    (net (code "271") (name "unconnected-(U3-PA1-Pad15)") (class "Default")
      (node (ref "U3") (pin "15") (pinfunction "PA1_15") (pintype "bidirectional"))
    )
    (net (code "272") (name "unconnected-(U3-PA4-Pad20)") (class "Default")
      (node (ref "U3") (pin "20") (pinfunction "PA4_20") (pintype "bidirectional"))
    )
    (net (code "273") (name "unconnected-(U3-PA5-Pad21)") (class "Default")
      (node (ref "U3") (pin "21") (pinfunction "PA5_21") (pintype "bidirectional"))
    )
    (net (code "274") (name "unconnected-(U3-PA8-Pad41)") (class "Default")
      (node (ref "U3") (pin "41") (pinfunction "PA8_41") (pintype "bidirectional"))
    )
    (net (code "275") (name "unconnected-(U3-PB1-Pad27)") (class "Default")
      (node (ref "U3") (pin "27") (pinfunction "PB1_27") (pintype "bidirectional"))
    )
    (net (code "276") (name "unconnected-(U3-PB1_2-Pad28)") (class "Default")
      (node (ref "U3") (pin "28") (pinfunction "PB1_2_28") (pintype "bidirectional"))
    )
    (net (code "277") (name "unconnected-(U3-PB4-Pad56)") (class "Default")
      (node (ref "U3") (pin "56") (pinfunction "PB4_56") (pintype "bidirectional"))
    )
    (net (code "278") (name "unconnected-(U3-PC0-Pad8)") (class "Default")
      (node (ref "U3") (pin "8") (pinfunction "PC0_8") (pintype "bidirectional"))
    )
    (net (code "279") (name "unconnected-(U3-PC1-Pad9)") (class "Default")
      (node (ref "U3") (pin "9") (pinfunction "PC1_9") (pintype "bidirectional"))
    )
    (net (code "280") (name "unconnected-(U3-PC2-Pad10)") (class "Default")
      (node (ref "U3") (pin "10") (pinfunction "PC2_10") (pintype "bidirectional"))
    )
    (net (code "281") (name "unconnected-(U3-PC3-Pad11)") (class "Default")
      (node (ref "U3") (pin "11") (pinfunction "PC3_11") (pintype "bidirectional"))
    )
    (net (code "282") (name "unconnected-(U3-PC4-Pad24)") (class "Default")
      (node (ref "U3") (pin "24") (pinfunction "PC4_24") (pintype "passive"))
    )
    (net (code "283") (name "unconnected-(U3-PC5-Pad25)") (class "Default")
      (node (ref "U3") (pin "25") (pinfunction "PC5_25") (pintype "bidirectional"))
    )
    (net (code "284") (name "unconnected-(U3-PC6-Pad37)") (class "Default")
      (node (ref "U3") (pin "37") (pinfunction "PC6_37") (pintype "bidirectional"))
    )
    (net (code "285") (name "unconnected-(U3-PC7-Pad38)") (class "Default")
      (node (ref "U3") (pin "38") (pinfunction "PC7_38") (pintype "bidirectional"))
    )
    (net (code "286") (name "unconnected-(U3-PC8-Pad39)") (class "Default")
      (node (ref "U3") (pin "39") (pinfunction "PC8_39") (pintype "bidirectional"))
    )
    (net (code "287") (name "unconnected-(U3-PC9-Pad40)") (class "Default")
      (node (ref "U3") (pin "40") (pinfunction "PC9_40") (pintype "bidirectional"))
    )
    (net (code "288") (name "unconnected-(U3-PC13-TAMPER-RTC-Pad2)") (class "Default")
      (node (ref "U3") (pin "2") (pinfunction "PC13-TAMPER-RTC_2") (pintype "input"))
    )
    (net (code "289") (name "unconnected-(U6-PA0-Pad6)") (class "Default")
      (node (ref "U6") (pin "6") (pinfunction "PA0_6") (pintype "bidirectional"))
    )
    (net (code "290") (name "unconnected-(U6-PA1-Pad7)") (class "Default")
      (node (ref "U6") (pin "7") (pinfunction "PA1_7") (pintype "bidirectional"))
    )
    (net (code "291") (name "unconnected-(U6-PA4-Pad10)") (class "Default")
      (node (ref "U6") (pin "10") (pinfunction "PA4_10") (pintype "bidirectional"))
    )
    (net (code "292") (name "unconnected-(U6-PF1{slash}OSC_OUT-Pad3)") (class "Default")
      (node (ref "U6") (pin "3") (pinfunction "PF1/OSC_OUT_3") (pintype "bidirectional"))
    )
    (net (code "293") (name "unconnected-(X5A-S-Pad1)") (class "Default")
      (node (ref "X5") (pin "1") (pinfunction "S_1") (pintype "passive"))
    )
    (net (code "294") (name "unconnected-(X5AA-S-Pad6)") (class "Default")
      (node (ref "X5") (pin "6") (pinfunction "S_6") (pintype "passive"))
    )
    (net (code "295") (name "unconnected-(X5AB-S-Pad7)") (class "Default")
      (node (ref "X5") (pin "7") (pinfunction "S_7") (pintype "passive"))
    )
    (net (code "296") (name "unconnected-(X5AC-S-Pad8)") (class "Default")
      (node (ref "X5") (pin "8") (pinfunction "S_8") (pintype "passive"))
    )
    (net (code "297") (name "unconnected-(X5AD-S-Pad9)") (class "Default")
      (node (ref "X5") (pin "9") (pinfunction "S_9") (pintype "passive"))
    )
    (net (code "298") (name "unconnected-(X5E-S-Pad13)") (class "Default")
      (node (ref "X5") (pin "13") (pinfunction "S_13") (pintype "passive"))
    )
    (net (code "299") (name "unconnected-(X5N-S-Pad21)") (class "Default")
      (node (ref "X5") (pin "21") (pinfunction "S_21") (pintype "passive"))
    )
    (net (code "300") (name "unconnected-(X5O-S-Pad22)") (class "Default")
      (node (ref "X5") (pin "22") (pinfunction "S_22") (pintype "passive"))
    )
    (net (code "301") (name "unconnected-(X5P-S-Pad23)") (class "Default")
      (node (ref "X5") (pin "23") (pinfunction "S_23") (pintype "passive"))
    )
    (net (code "302") (name "unconnected-(X5Q-S-Pad24)") (class "Default")
      (node (ref "X5") (pin "24") (pinfunction "S_24") (pintype "passive"))
    )
    (net (code "303") (name "unconnected-(X5R-S-Pad25)") (class "Default")
      (node (ref "X5") (pin "25") (pinfunction "S_25") (pintype "passive"))
    )
    (net (code "304") (name "unconnected-(X5S-S-Pad26)") (class "Default")
      (node (ref "X5") (pin "26") (pinfunction "S_26") (pintype "passive"))
    )
    (net (code "305") (name "unconnected-(X5W-S-Pad3)") (class "Default")
      (node (ref "X5") (pin "3") (pinfunction "S_3") (pintype "passive"))
    )
    (net (code "306") (name "unconnected-(X5X-S-Pad30)") (class "Default")
      (node (ref "X5") (pin "30") (pinfunction "S_30") (pintype "passive"))
    )
    (net (code "307") (name "unconnected-(X5Y-S-Pad4)") (class "Default")
      (node (ref "X5") (pin "4") (pinfunction "S_4") (pintype "passive"))
    )
    (net (code "308") (name "unconnected-(X5Z-S-Pad5)") (class "Default")
      (node (ref "X5") (pin "5") (pinfunction "S_5") (pintype "passive"))
    )
  )
)
